# 7SEG_STATUS_1.net
KiCad netlist of a schematic drawn in EAGLE
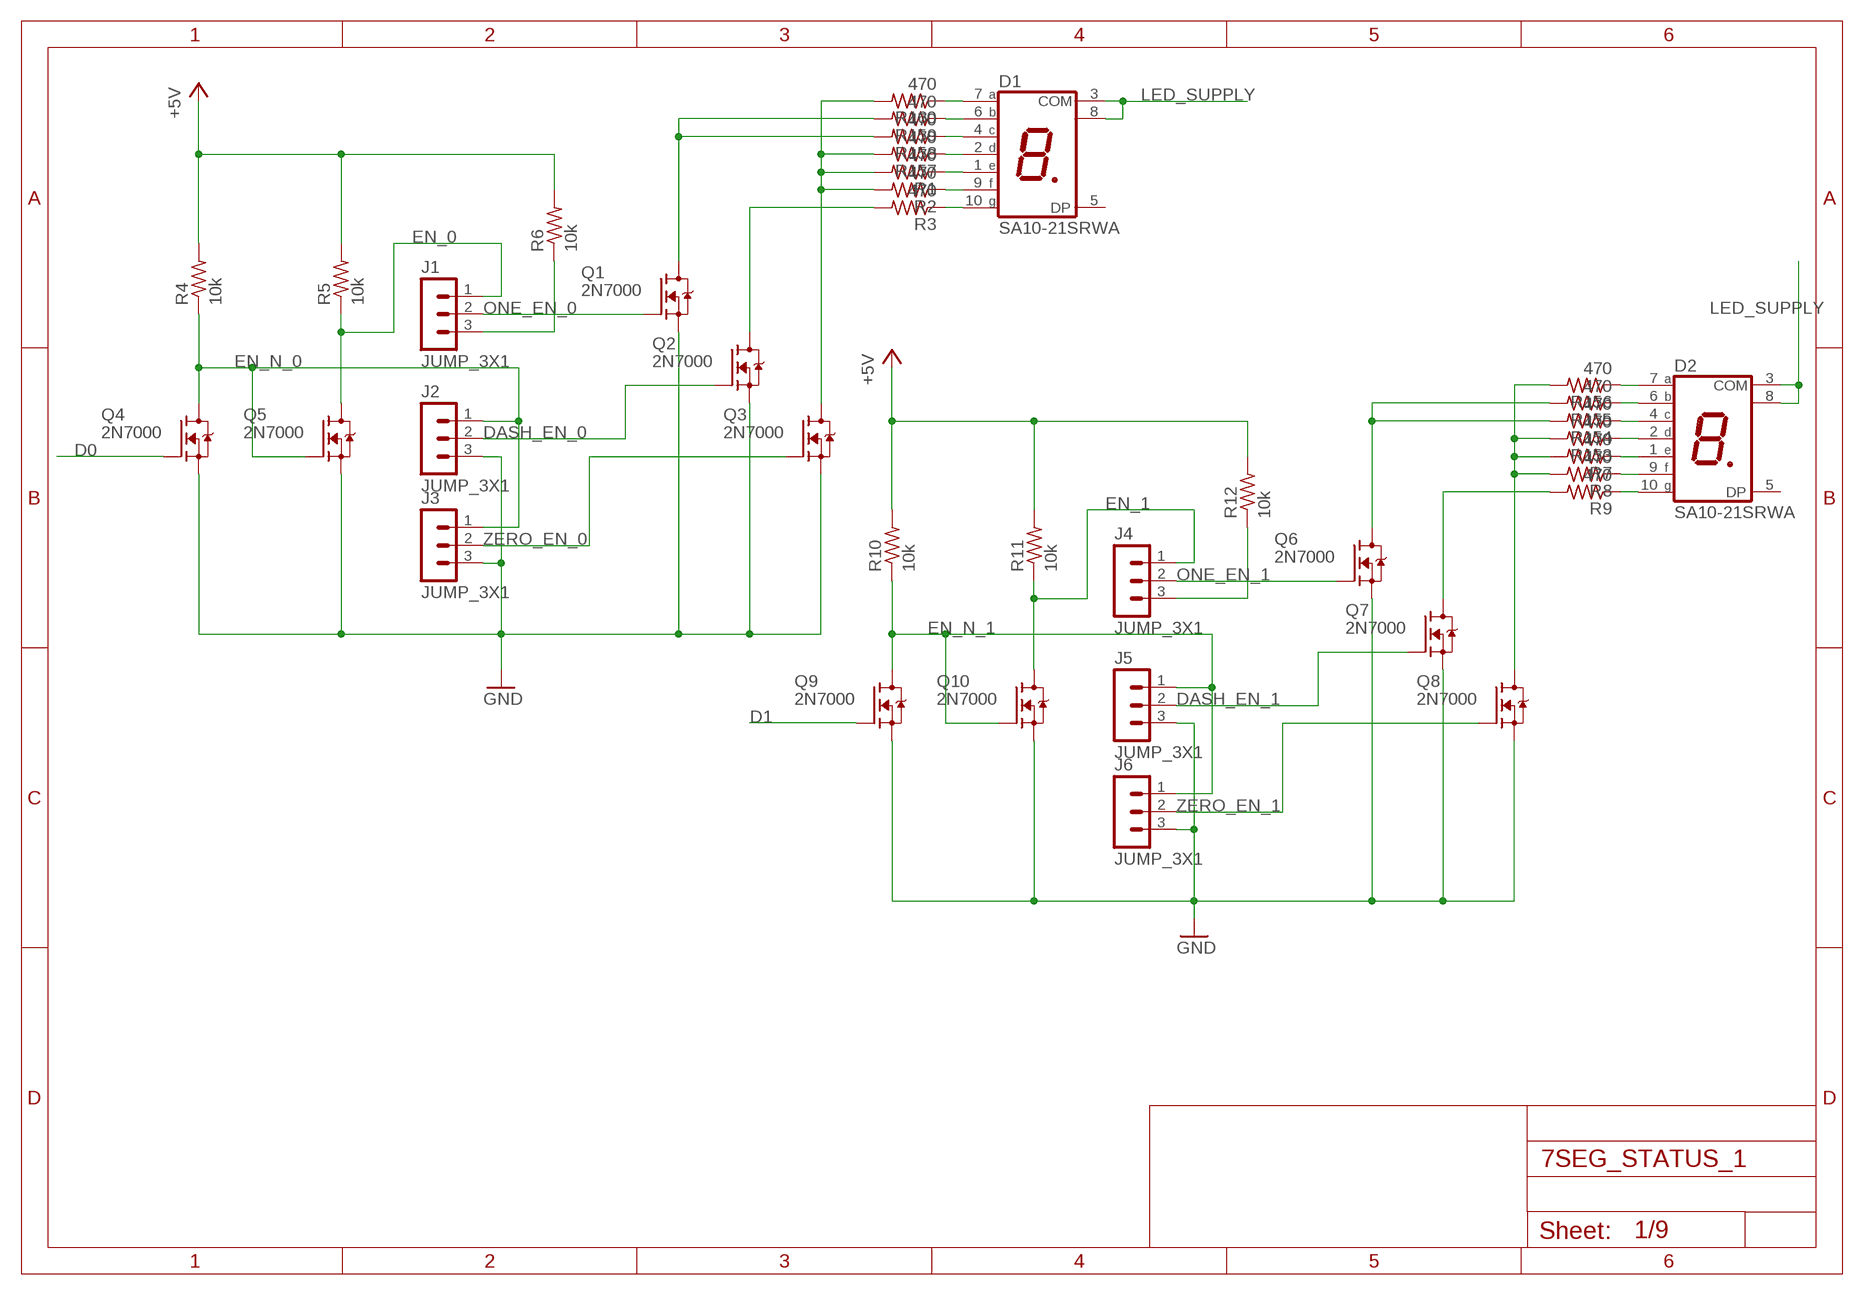
[diagram p0: schematic, sheet 1]
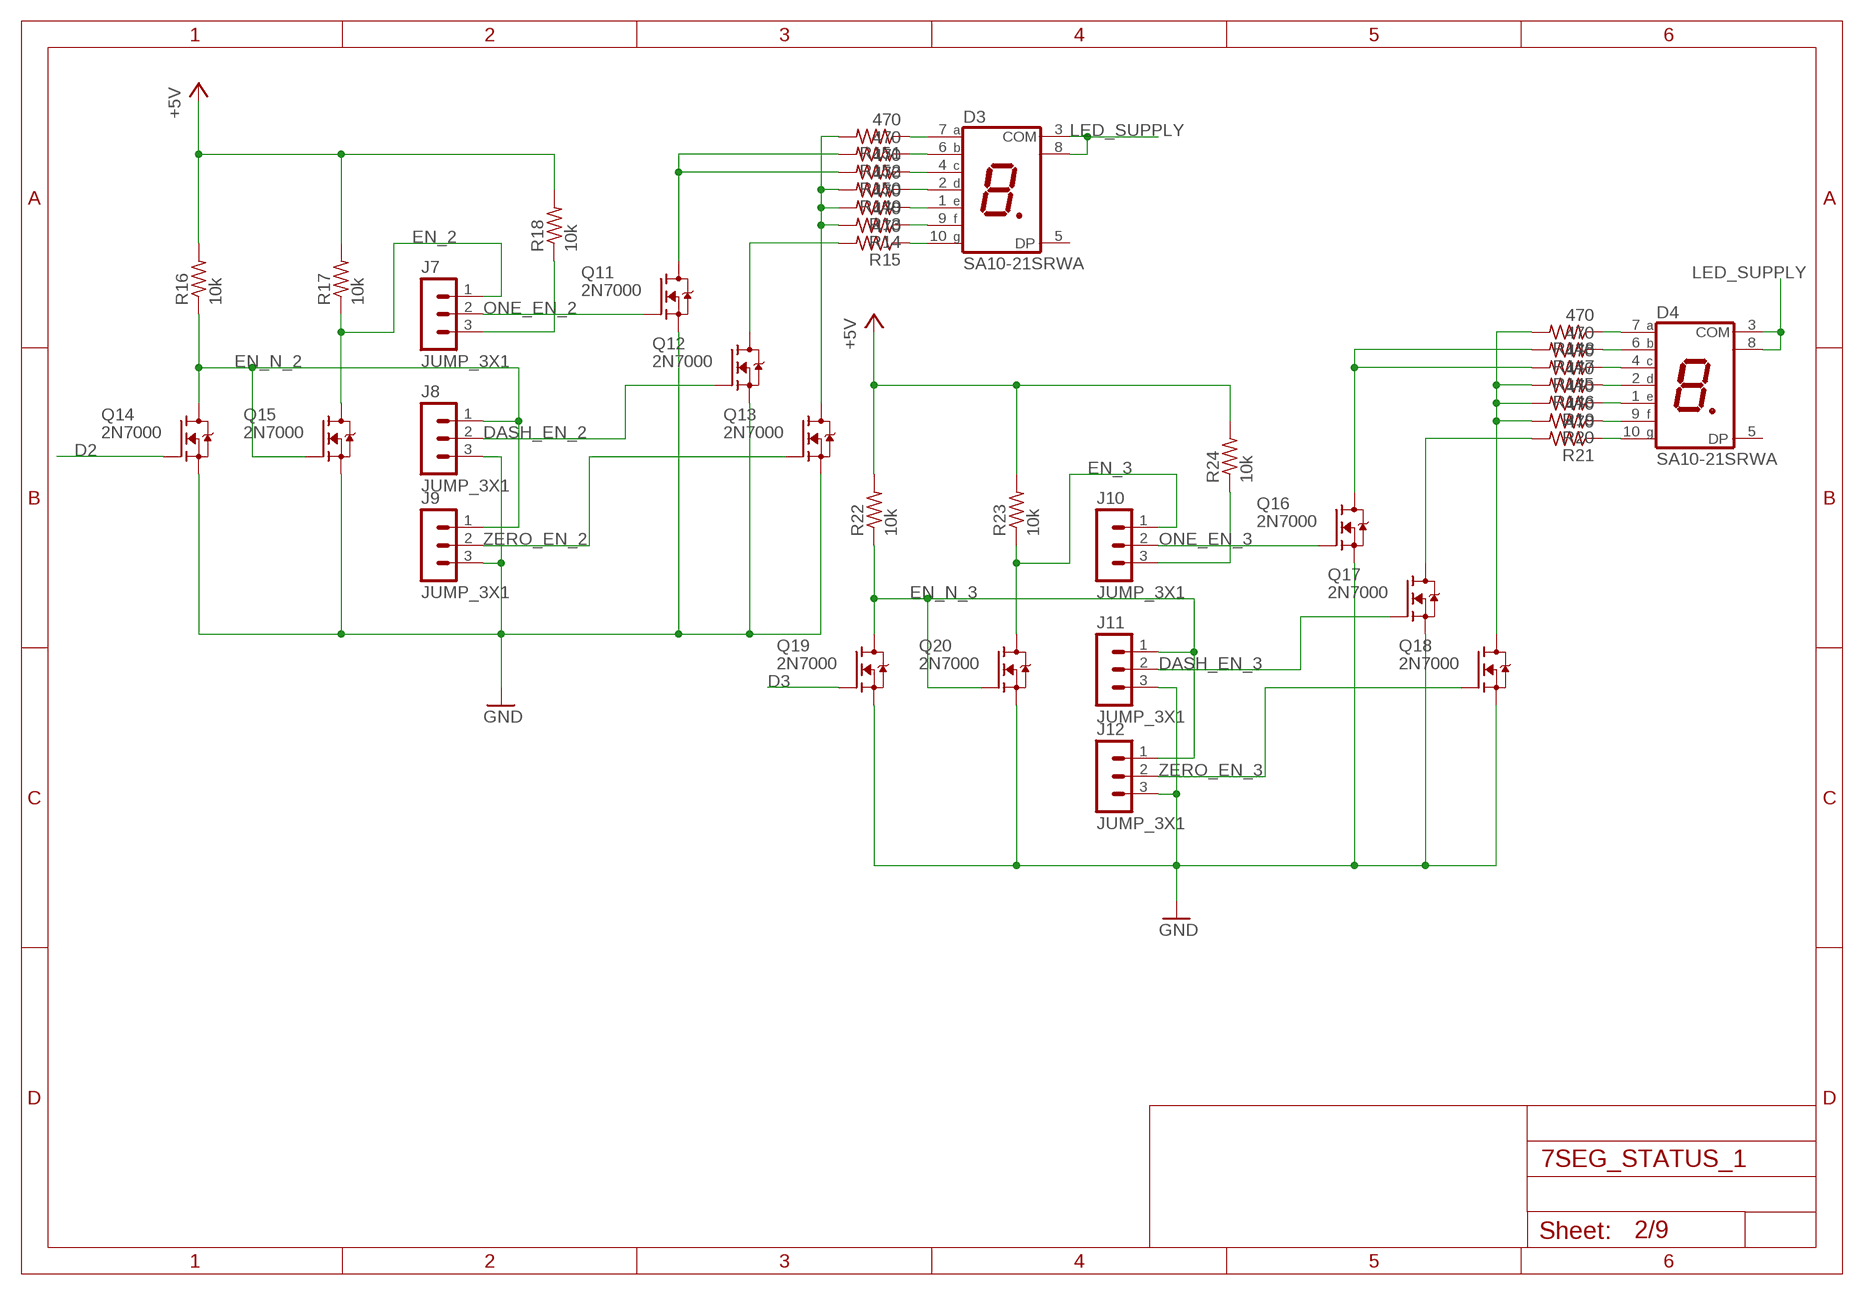
[diagram p1: schematic, sheet 2]
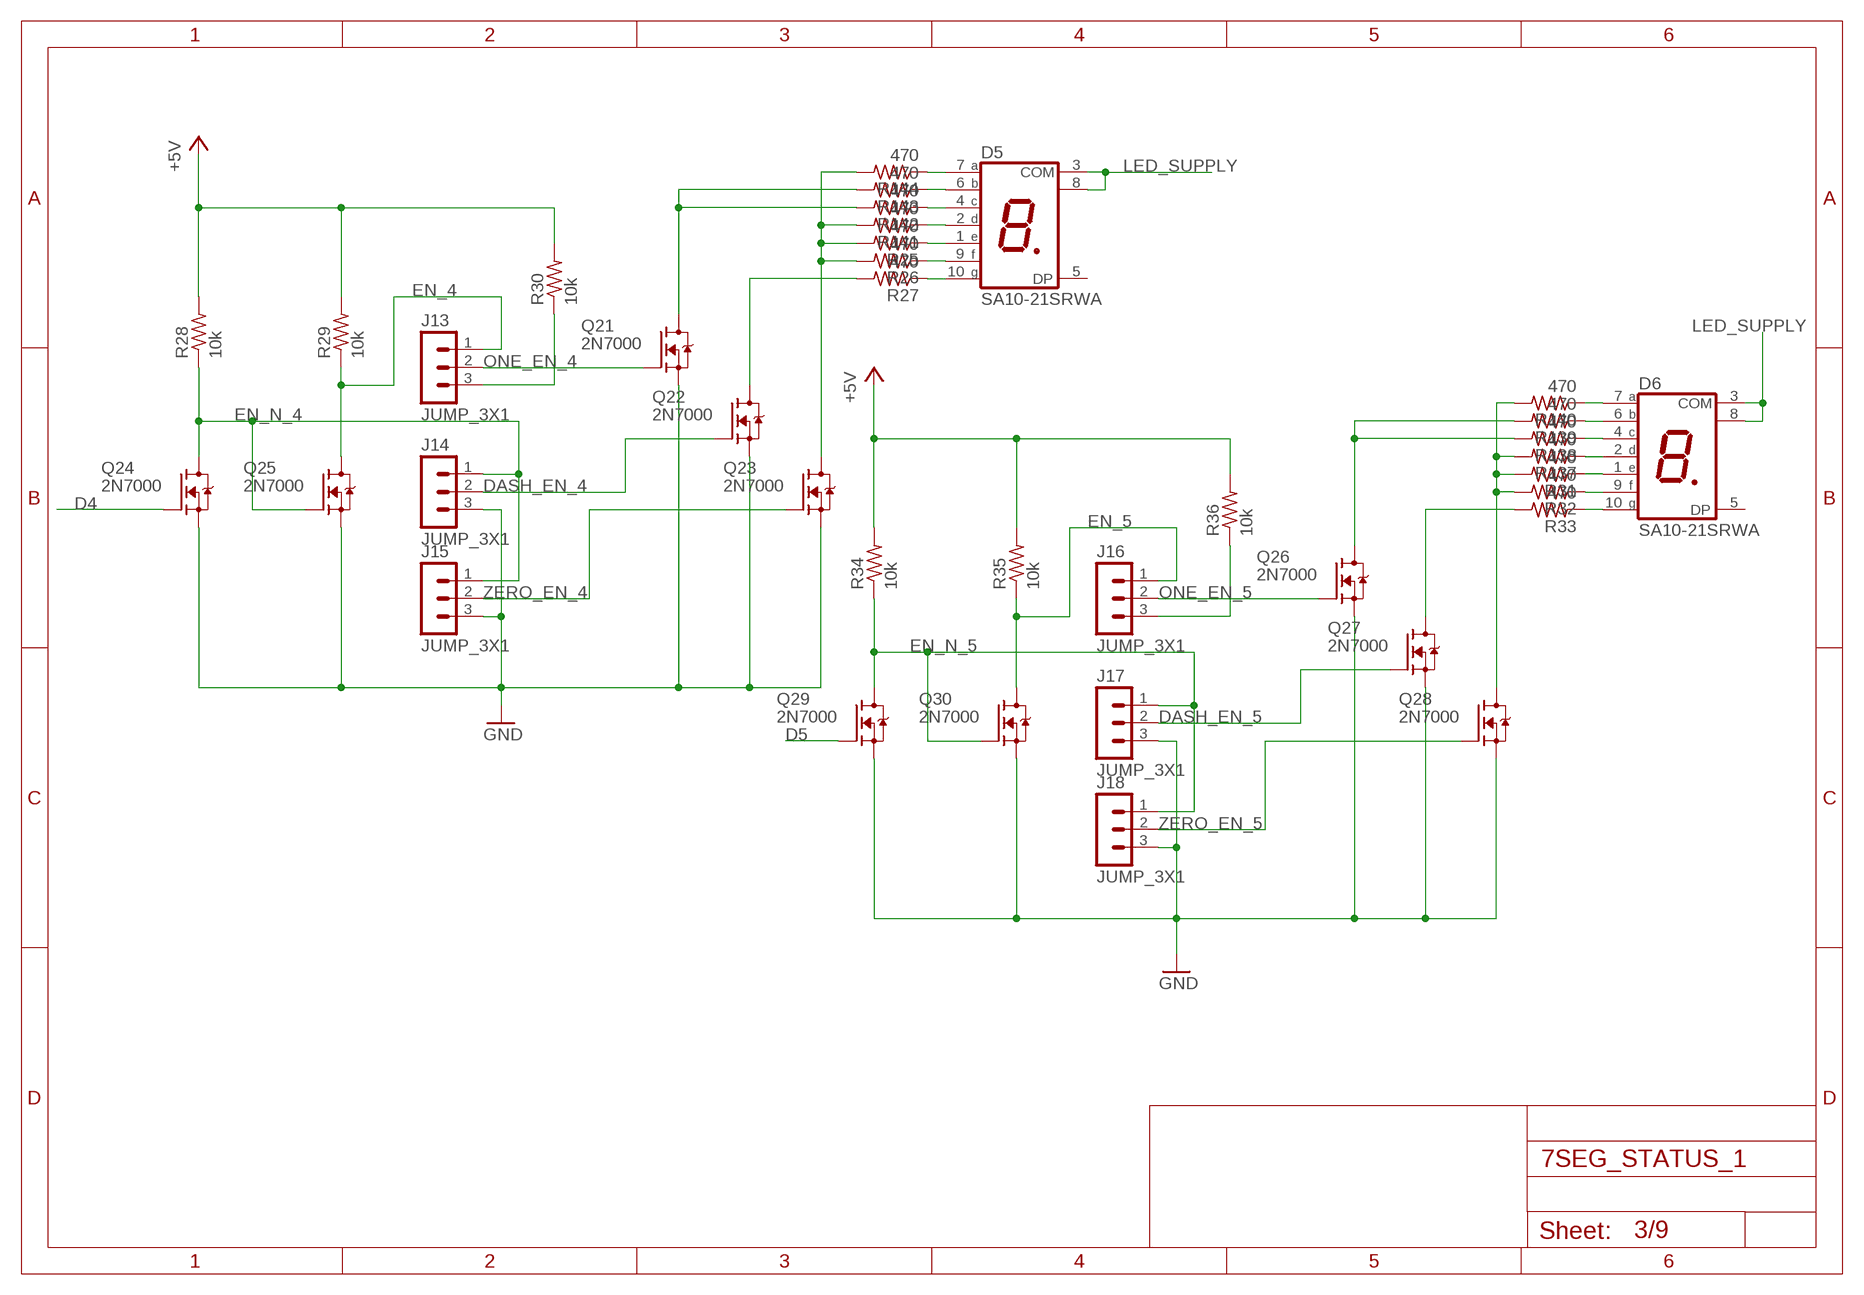
[diagram p2: schematic, sheet 3]
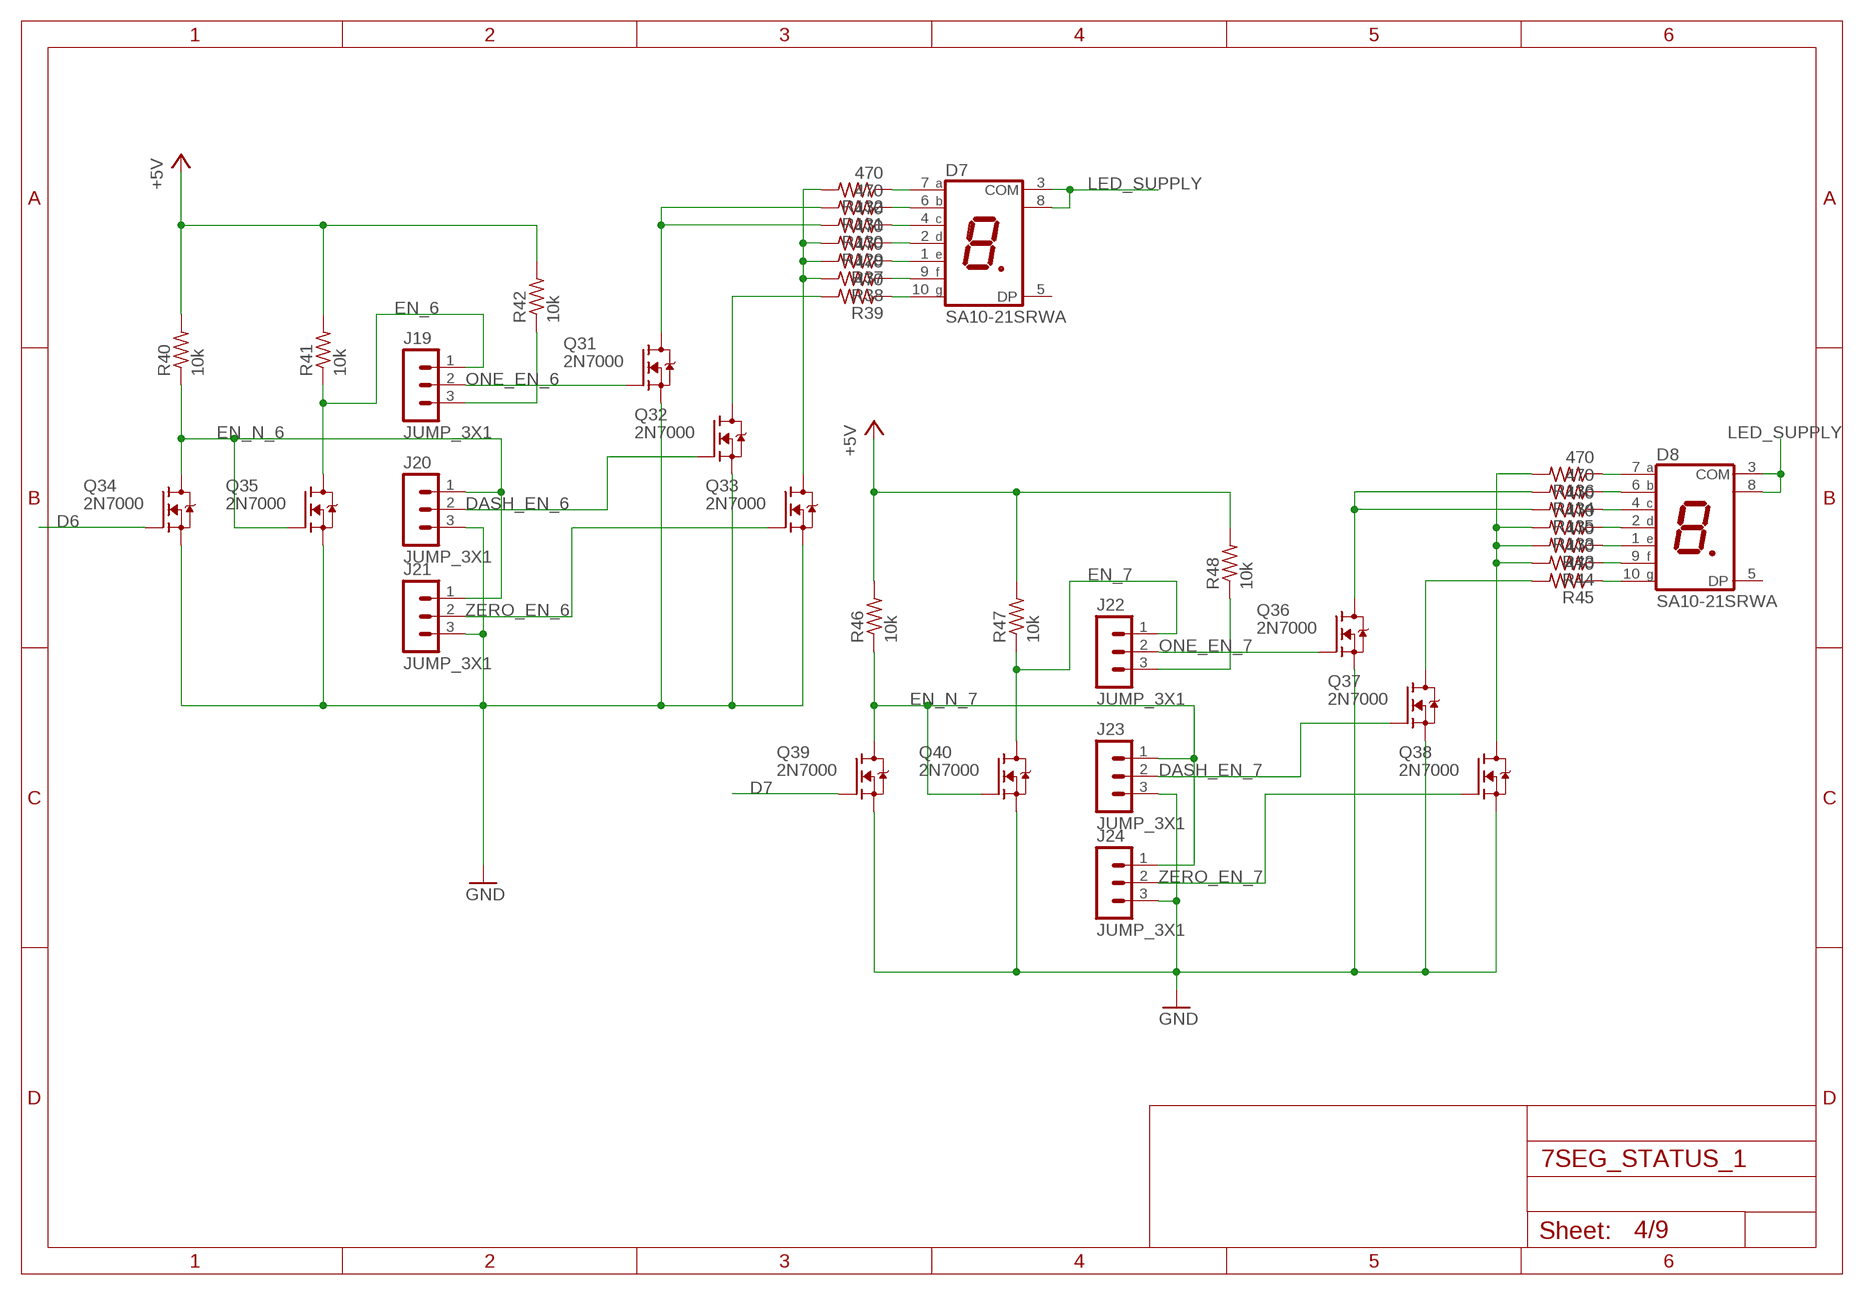
[diagram p3: schematic, sheet 4]
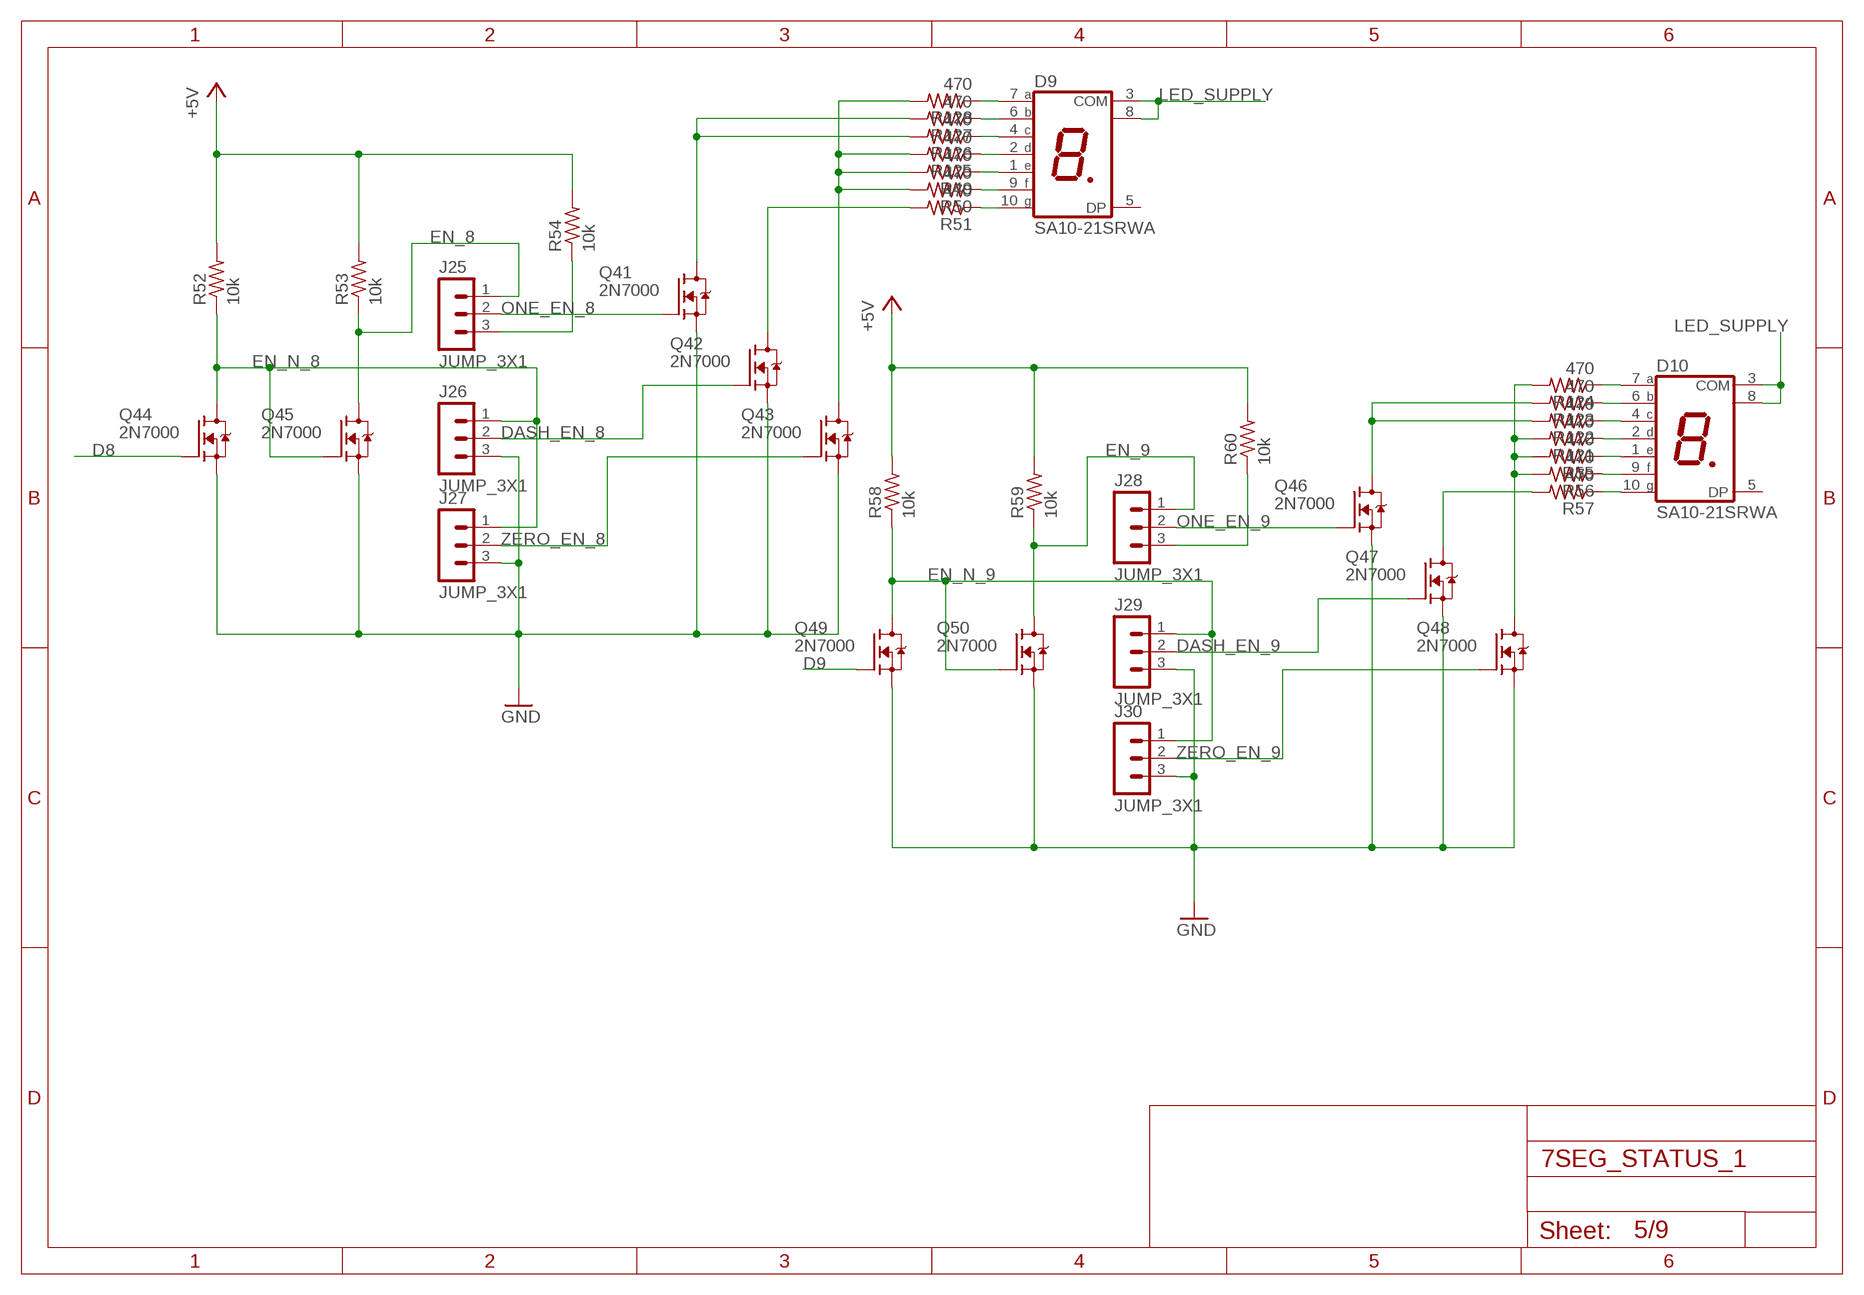
[diagram p4: schematic, sheet 5]
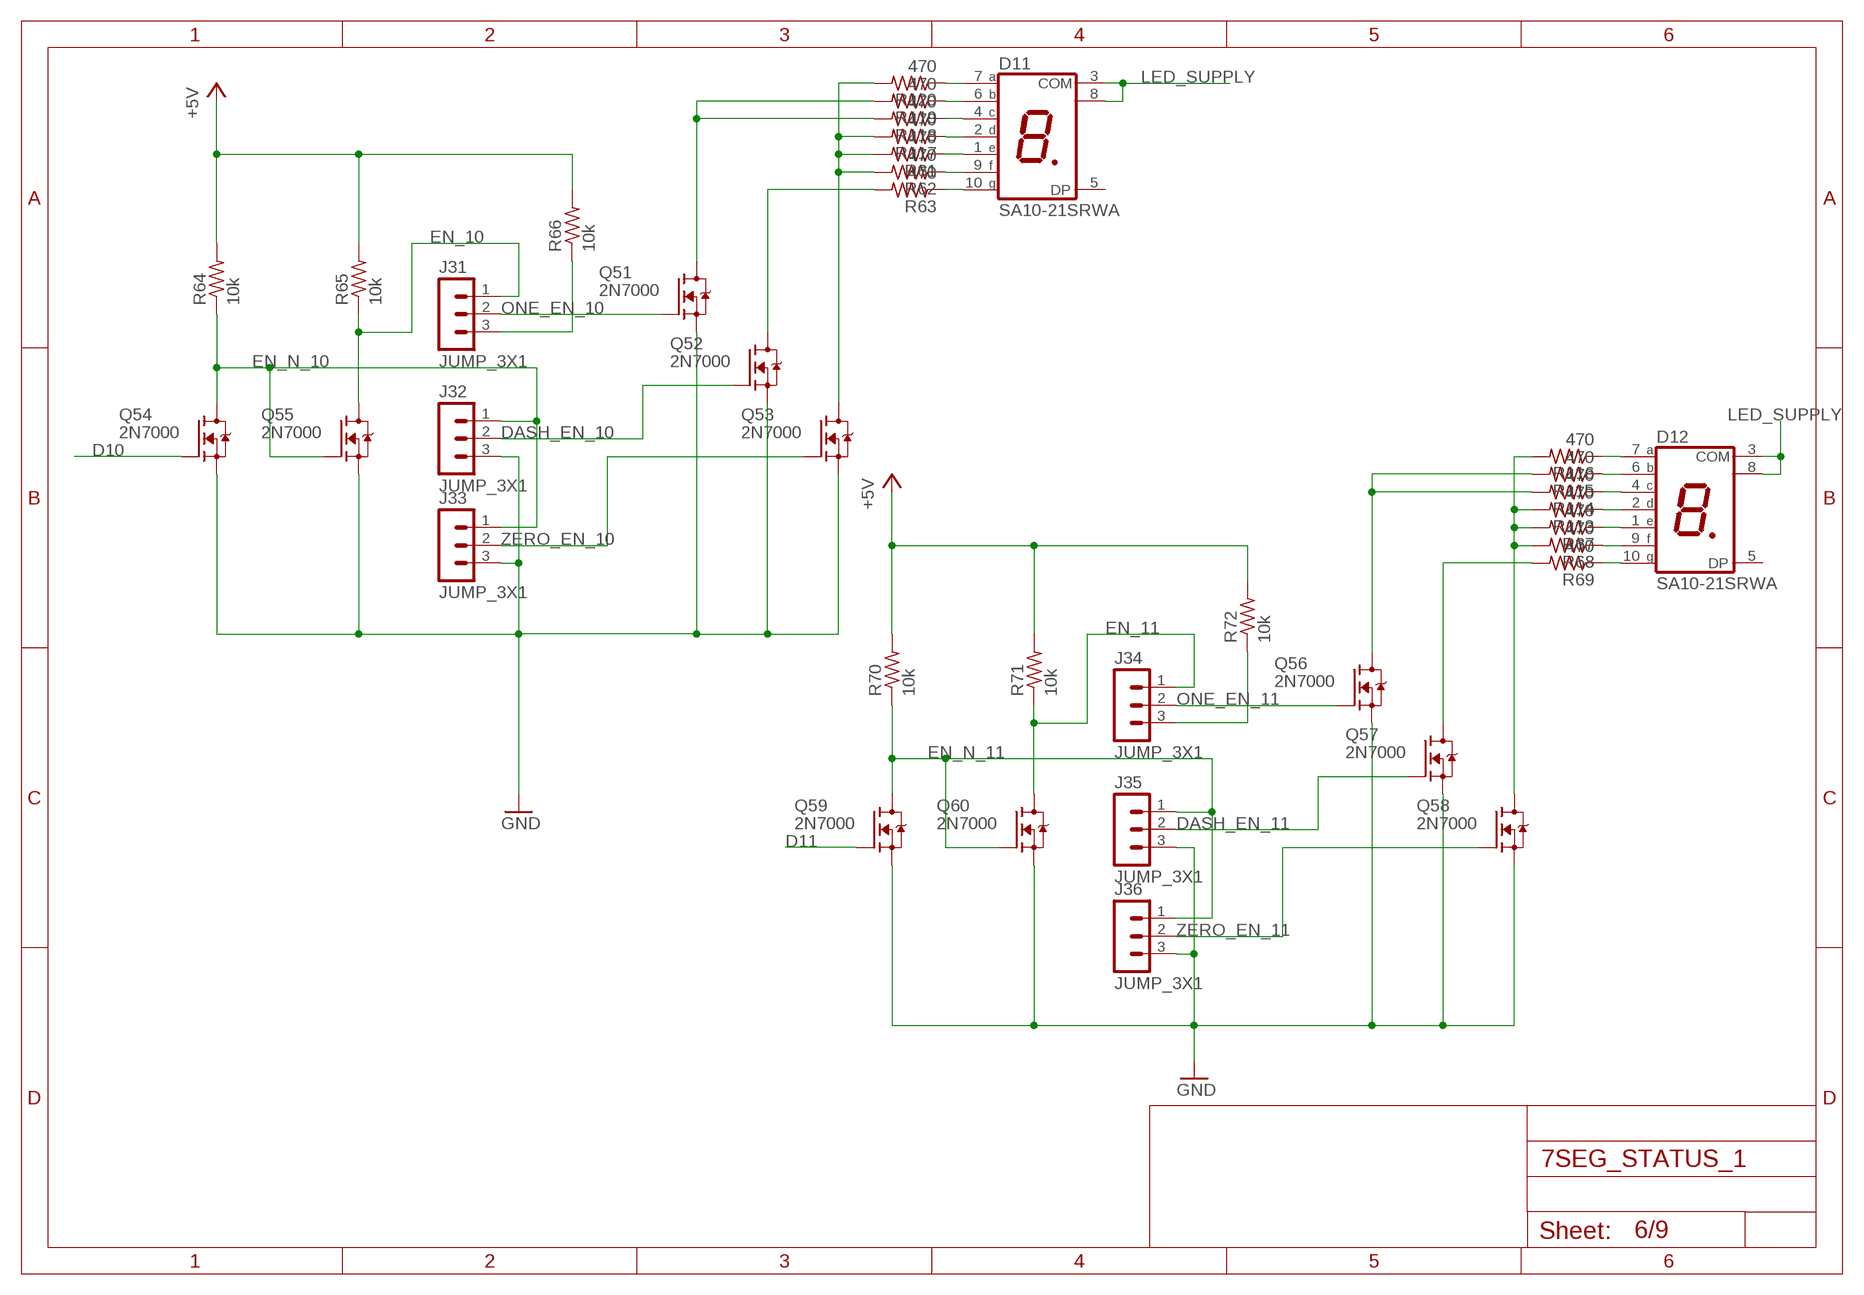
[diagram p5: schematic, sheet 6]
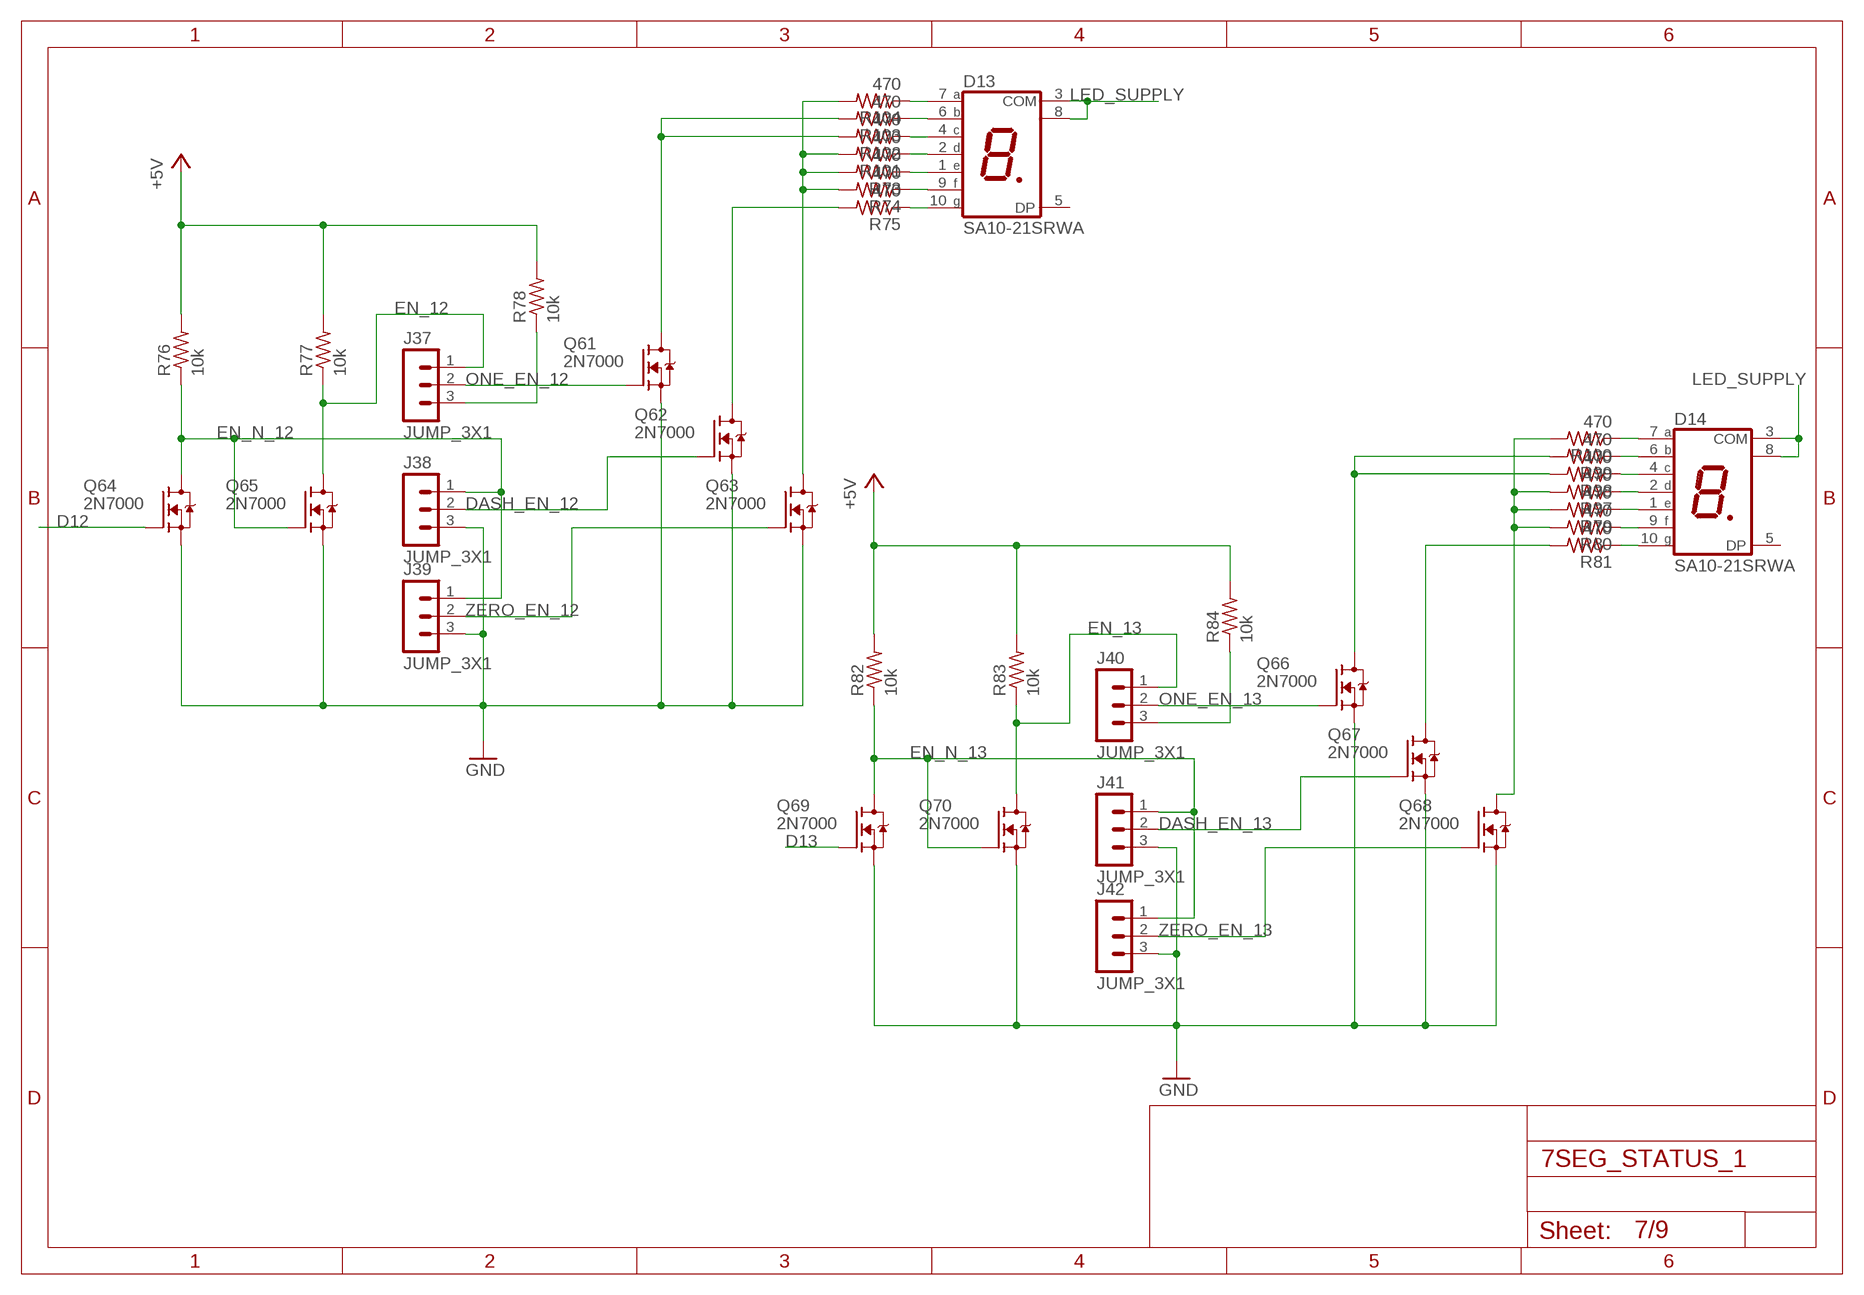
[diagram p6: schematic, sheet 7]
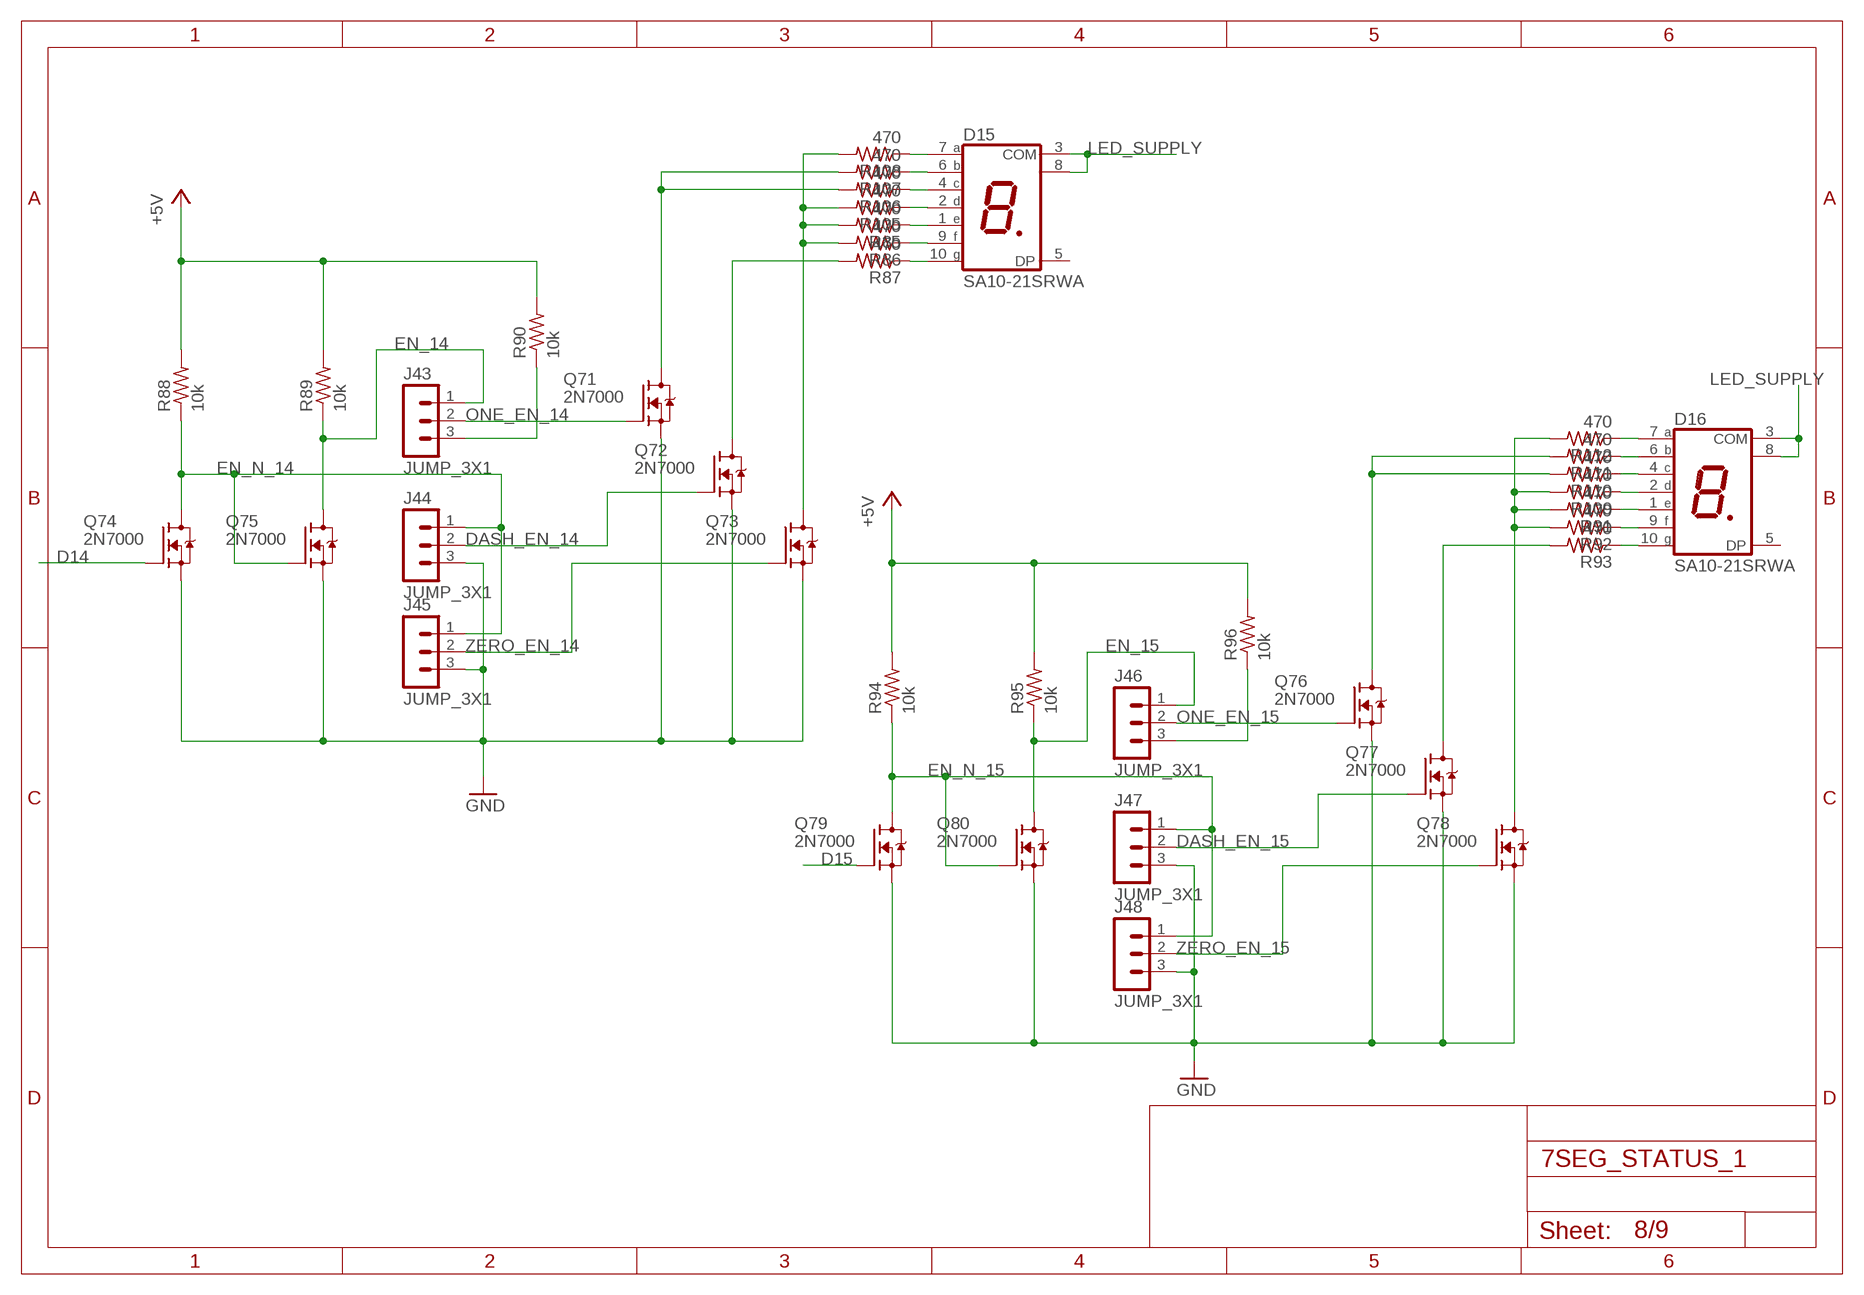
[diagram p7: schematic, sheet 8]
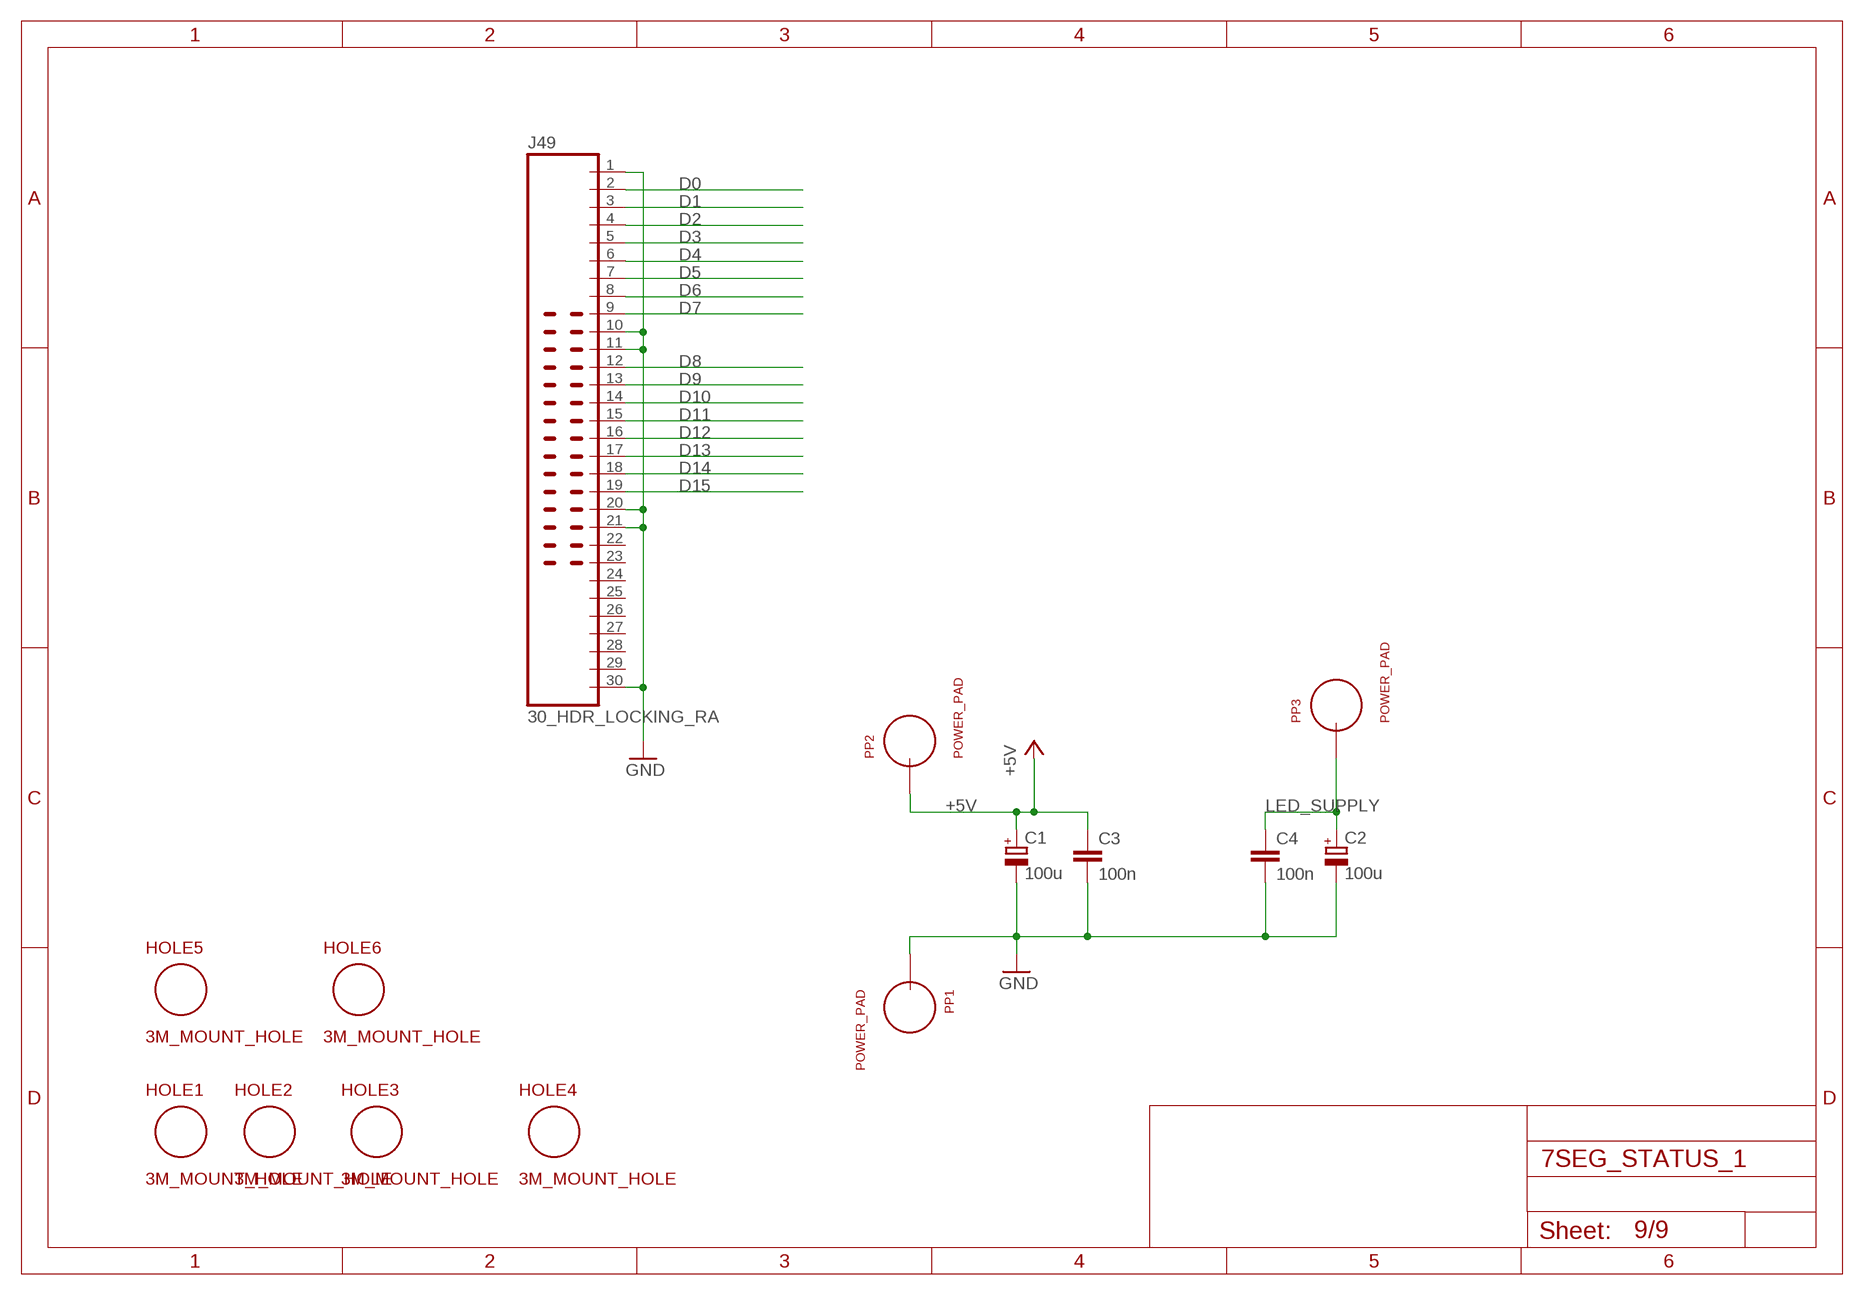
[diagram p8: schematic, sheet 9]

(export (version "E")
  (design (tool "Eeschema 10.0.6"))
  (components
    (comp (ref "D3")
      (value "SA10-21SRWA")
      (footprint "eagle-import:SA10")
      (libsource (lib "eagle-import") (part "SA10-21SRWA"))
    )
    (comp (ref "D4")
      (value "SA10-21SRWA")
      (footprint "eagle-import:SA10")
      (libsource (lib "eagle-import") (part "SA10-21SRWA"))
    )
    (comp (ref "J7")
      (value "JUMP_3X1")
      (footprint "eagle-import:JUMP_3X1")
      (libsource (lib "eagle-import") (part "JUMP_3X1"))
    )
    (comp (ref "J8")
      (value "JUMP_3X1")
      (footprint "eagle-import:JUMP_3X1")
      (libsource (lib "eagle-import") (part "JUMP_3X1"))
    )
    (comp (ref "J9")
      (value "JUMP_3X1")
      (footprint "eagle-import:JUMP_3X1")
      (libsource (lib "eagle-import") (part "JUMP_3X1"))
    )
    (comp (ref "J10")
      (value "JUMP_3X1")
      (footprint "eagle-import:JUMP_3X1")
      (libsource (lib "eagle-import") (part "JUMP_3X1"))
    )
    (comp (ref "J11")
      (value "JUMP_3X1")
      (footprint "eagle-import:JUMP_3X1")
      (libsource (lib "eagle-import") (part "JUMP_3X1"))
    )
    (comp (ref "J12")
      (value "JUMP_3X1")
      (footprint "eagle-import:JUMP_3X1")
      (libsource (lib "eagle-import") (part "JUMP_3X1"))
    )
    (comp (ref "Q11")
      (value "2N7000")
      (footprint "eagle-import:TO92-DGS")
      (libsource (lib "eagle-import") (part "2N7000"))
    )
    (comp (ref "Q12")
      (value "2N7000")
      (footprint "eagle-import:TO92-DGS")
      (libsource (lib "eagle-import") (part "2N7000"))
    )
    (comp (ref "Q13")
      (value "2N7000")
      (footprint "eagle-import:TO92-DGS")
      (libsource (lib "eagle-import") (part "2N7000"))
    )
    (comp (ref "Q14")
      (value "2N7000")
      (footprint "eagle-import:TO92-DGS")
      (libsource (lib "eagle-import") (part "2N7000"))
    )
    (comp (ref "Q15")
      (value "2N7000")
      (footprint "eagle-import:TO92-DGS")
      (libsource (lib "eagle-import") (part "2N7000"))
    )
    (comp (ref "Q16")
      (value "2N7000")
      (footprint "eagle-import:TO92-DGS")
      (libsource (lib "eagle-import") (part "2N7000"))
    )
    (comp (ref "Q17")
      (value "2N7000")
      (footprint "eagle-import:TO92-DGS")
      (libsource (lib "eagle-import") (part "2N7000"))
    )
    (comp (ref "Q18")
      (value "2N7000")
      (footprint "eagle-import:TO92-DGS")
      (libsource (lib "eagle-import") (part "2N7000"))
    )
    (comp (ref "Q19")
      (value "2N7000")
      (footprint "eagle-import:TO92-DGS")
      (libsource (lib "eagle-import") (part "2N7000"))
    )
    (comp (ref "Q20")
      (value "2N7000")
      (footprint "eagle-import:TO92-DGS")
      (libsource (lib "eagle-import") (part "2N7000"))
    )
    (comp (ref "R13")
      (value "470")
      (footprint "eagle-import:R_P2INCH")
      (libsource (lib "eagle-import") (part "R_P2INCH"))
    )
    (comp (ref "R14")
      (value "470")
      (footprint "eagle-import:R_P2INCH")
      (libsource (lib "eagle-import") (part "R_P2INCH"))
    )
    (comp (ref "R15")
      (value "470")
      (footprint "eagle-import:R_P2INCH")
      (libsource (lib "eagle-import") (part "R_P2INCH"))
    )
    (comp (ref "R16")
      (value "10k")
      (footprint "eagle-import:R_P2INCH")
      (libsource (lib "eagle-import") (part "R_P2INCH"))
    )
    (comp (ref "R17")
      (value "10k")
      (footprint "eagle-import:R_P2INCH")
      (libsource (lib "eagle-import") (part "R_P2INCH"))
    )
    (comp (ref "R18")
      (value "10k")
      (footprint "eagle-import:R_P2INCH")
      (libsource (lib "eagle-import") (part "R_P2INCH"))
    )
    (comp (ref "R19")
      (value "470")
      (footprint "eagle-import:R_P2INCH")
      (libsource (lib "eagle-import") (part "R_P2INCH"))
    )
    (comp (ref "R20")
      (value "470")
      (footprint "eagle-import:R_P2INCH")
      (libsource (lib "eagle-import") (part "R_P2INCH"))
    )
    (comp (ref "R21")
      (value "470")
      (footprint "eagle-import:R_P2INCH")
      (libsource (lib "eagle-import") (part "R_P2INCH"))
    )
    (comp (ref "R22")
      (value "10k")
      (footprint "eagle-import:R_P2INCH")
      (libsource (lib "eagle-import") (part "R_P2INCH"))
    )
    (comp (ref "R23")
      (value "10k")
      (footprint "eagle-import:R_P2INCH")
      (libsource (lib "eagle-import") (part "R_P2INCH"))
    )
    (comp (ref "R24")
      (value "10k")
      (footprint "eagle-import:R_P2INCH")
      (libsource (lib "eagle-import") (part "R_P2INCH"))
    )
    (comp (ref "R145")
      (value "470")
      (footprint "eagle-import:R_P2INCH")
      (libsource (lib "eagle-import") (part "R_P2INCH"))
    )
    (comp (ref "R146")
      (value "470")
      (footprint "eagle-import:R_P2INCH")
      (libsource (lib "eagle-import") (part "R_P2INCH"))
    )
    (comp (ref "R147")
      (value "470")
      (footprint "eagle-import:R_P2INCH")
      (libsource (lib "eagle-import") (part "R_P2INCH"))
    )
    (comp (ref "R148")
      (value "470")
      (footprint "eagle-import:R_P2INCH")
      (libsource (lib "eagle-import") (part "R_P2INCH"))
    )
    (comp (ref "R149")
      (value "470")
      (footprint "eagle-import:R_P2INCH")
      (libsource (lib "eagle-import") (part "R_P2INCH"))
    )
    (comp (ref "R150")
      (value "470")
      (footprint "eagle-import:R_P2INCH")
      (libsource (lib "eagle-import") (part "R_P2INCH"))
    )
    (comp (ref "R151")
      (value "470")
      (footprint "eagle-import:R_P2INCH")
      (libsource (lib "eagle-import") (part "R_P2INCH"))
    )
    (comp (ref "R152")
      (value "470")
      (footprint "eagle-import:R_P2INCH")
      (libsource (lib "eagle-import") (part "R_P2INCH"))
    )
    (comp (ref "D13")
      (value "SA10-21SRWA")
      (footprint "eagle-import:SA10")
      (libsource (lib "eagle-import") (part "SA10-21SRWA"))
    )
    (comp (ref "D14")
      (value "SA10-21SRWA")
      (footprint "eagle-import:SA10")
      (libsource (lib "eagle-import") (part "SA10-21SRWA"))
    )
    (comp (ref "J37")
      (value "JUMP_3X1")
      (footprint "eagle-import:JUMP_3X1")
      (libsource (lib "eagle-import") (part "JUMP_3X1"))
    )
    (comp (ref "J38")
      (value "JUMP_3X1")
      (footprint "eagle-import:JUMP_3X1")
      (libsource (lib "eagle-import") (part "JUMP_3X1"))
    )
    (comp (ref "J39")
      (value "JUMP_3X1")
      (footprint "eagle-import:JUMP_3X1")
      (libsource (lib "eagle-import") (part "JUMP_3X1"))
    )
    (comp (ref "J40")
      (value "JUMP_3X1")
      (footprint "eagle-import:JUMP_3X1")
      (libsource (lib "eagle-import") (part "JUMP_3X1"))
    )
    (comp (ref "J41")
      (value "JUMP_3X1")
      (footprint "eagle-import:JUMP_3X1")
      (libsource (lib "eagle-import") (part "JUMP_3X1"))
    )
    (comp (ref "J42")
      (value "JUMP_3X1")
      (footprint "eagle-import:JUMP_3X1")
      (libsource (lib "eagle-import") (part "JUMP_3X1"))
    )
    (comp (ref "Q61")
      (value "2N7000")
      (footprint "eagle-import:TO92-DGS")
      (libsource (lib "eagle-import") (part "2N7000"))
    )
    (comp (ref "Q62")
      (value "2N7000")
      (footprint "eagle-import:TO92-DGS")
      (libsource (lib "eagle-import") (part "2N7000"))
    )
    (comp (ref "Q63")
      (value "2N7000")
      (footprint "eagle-import:TO92-DGS")
      (libsource (lib "eagle-import") (part "2N7000"))
    )
    (comp (ref "Q64")
      (value "2N7000")
      (footprint "eagle-import:TO92-DGS")
      (libsource (lib "eagle-import") (part "2N7000"))
    )
    (comp (ref "Q65")
      (value "2N7000")
      (footprint "eagle-import:TO92-DGS")
      (libsource (lib "eagle-import") (part "2N7000"))
    )
    (comp (ref "Q66")
      (value "2N7000")
      (footprint "eagle-import:TO92-DGS")
      (libsource (lib "eagle-import") (part "2N7000"))
    )
    (comp (ref "Q67")
      (value "2N7000")
      (footprint "eagle-import:TO92-DGS")
      (libsource (lib "eagle-import") (part "2N7000"))
    )
    (comp (ref "Q68")
      (value "2N7000")
      (footprint "eagle-import:TO92-DGS")
      (libsource (lib "eagle-import") (part "2N7000"))
    )
    (comp (ref "Q69")
      (value "2N7000")
      (footprint "eagle-import:TO92-DGS")
      (libsource (lib "eagle-import") (part "2N7000"))
    )
    (comp (ref "Q70")
      (value "2N7000")
      (footprint "eagle-import:TO92-DGS")
      (libsource (lib "eagle-import") (part "2N7000"))
    )
    (comp (ref "R73")
      (value "470")
      (footprint "eagle-import:R_P2INCH")
      (libsource (lib "eagle-import") (part "R_P2INCH"))
    )
    (comp (ref "R74")
      (value "470")
      (footprint "eagle-import:R_P2INCH")
      (libsource (lib "eagle-import") (part "R_P2INCH"))
    )
    (comp (ref "R75")
      (value "470")
      (footprint "eagle-import:R_P2INCH")
      (libsource (lib "eagle-import") (part "R_P2INCH"))
    )
    (comp (ref "R76")
      (value "10k")
      (footprint "eagle-import:R_P2INCH")
      (libsource (lib "eagle-import") (part "R_P2INCH"))
    )
    (comp (ref "R77")
      (value "10k")
      (footprint "eagle-import:R_P2INCH")
      (libsource (lib "eagle-import") (part "R_P2INCH"))
    )
    (comp (ref "R78")
      (value "10k")
      (footprint "eagle-import:R_P2INCH")
      (libsource (lib "eagle-import") (part "R_P2INCH"))
    )
    (comp (ref "R79")
      (value "470")
      (footprint "eagle-import:R_P2INCH")
      (libsource (lib "eagle-import") (part "R_P2INCH"))
    )
    (comp (ref "R80")
      (value "470")
      (footprint "eagle-import:R_P2INCH")
      (libsource (lib "eagle-import") (part "R_P2INCH"))
    )
    (comp (ref "R81")
      (value "470")
      (footprint "eagle-import:R_P2INCH")
      (libsource (lib "eagle-import") (part "R_P2INCH"))
    )
    (comp (ref "R82")
      (value "10k")
      (footprint "eagle-import:R_P2INCH")
      (libsource (lib "eagle-import") (part "R_P2INCH"))
    )
    (comp (ref "R83")
      (value "10k")
      (footprint "eagle-import:R_P2INCH")
      (libsource (lib "eagle-import") (part "R_P2INCH"))
    )
    (comp (ref "R84")
      (value "10k")
      (footprint "eagle-import:R_P2INCH")
      (libsource (lib "eagle-import") (part "R_P2INCH"))
    )
    (comp (ref "R97")
      (value "470")
      (footprint "eagle-import:R_P2INCH")
      (libsource (lib "eagle-import") (part "R_P2INCH"))
    )
    (comp (ref "R98")
      (value "470")
      (footprint "eagle-import:R_P2INCH")
      (libsource (lib "eagle-import") (part "R_P2INCH"))
    )
    (comp (ref "R99")
      (value "470")
      (footprint "eagle-import:R_P2INCH")
      (libsource (lib "eagle-import") (part "R_P2INCH"))
    )
    (comp (ref "R100")
      (value "470")
      (footprint "eagle-import:R_P2INCH")
      (libsource (lib "eagle-import") (part "R_P2INCH"))
    )
    (comp (ref "R101")
      (value "470")
      (footprint "eagle-import:R_P2INCH")
      (libsource (lib "eagle-import") (part "R_P2INCH"))
    )
    (comp (ref "R102")
      (value "470")
      (footprint "eagle-import:R_P2INCH")
      (libsource (lib "eagle-import") (part "R_P2INCH"))
    )
    (comp (ref "R103")
      (value "470")
      (footprint "eagle-import:R_P2INCH")
      (libsource (lib "eagle-import") (part "R_P2INCH"))
    )
    (comp (ref "R104")
      (value "470")
      (footprint "eagle-import:R_P2INCH")
      (libsource (lib "eagle-import") (part "R_P2INCH"))
    )
    (comp (ref "C1")
      (value "100u")
      (footprint "eagle-import:POLARISED_CAP_2P5_6P3MM")
      (libsource (lib "eagle-import") (part "POLARISED_CAP_2P5_6P3MM"))
    )
    (comp (ref "C2")
      (value "100u")
      (footprint "eagle-import:POLARISED_CAP_2P5_6P3MM")
      (libsource (lib "eagle-import") (part "POLARISED_CAP_2P5_6P3MM"))
    )
    (comp (ref "C3")
      (value "100n")
      (footprint "eagle-import:CAP_P2INCH")
      (libsource (lib "eagle-import") (part "C_P2INCH"))
    )
    (comp (ref "C4")
      (value "100n")
      (footprint "eagle-import:CAP_P2INCH")
      (libsource (lib "eagle-import") (part "C_P2INCH"))
    )
    (comp (ref "HOLE1")
      (value "3M_MOUNT_HOLE")
      (footprint "eagle-import:3M_HOLE")
      (libsource (lib "eagle-import") (part "3M_MOUNT_HOLE"))
    )
    (comp (ref "HOLE2")
      (value "3M_MOUNT_HOLE")
      (footprint "eagle-import:3M_HOLE")
      (libsource (lib "eagle-import") (part "3M_MOUNT_HOLE"))
    )
    (comp (ref "HOLE3")
      (value "3M_MOUNT_HOLE")
      (footprint "eagle-import:3M_HOLE")
      (libsource (lib "eagle-import") (part "3M_MOUNT_HOLE"))
    )
    (comp (ref "HOLE4")
      (value "3M_MOUNT_HOLE")
      (footprint "eagle-import:3M_HOLE")
      (libsource (lib "eagle-import") (part "3M_MOUNT_HOLE"))
    )
    (comp (ref "HOLE5")
      (value "3M_MOUNT_HOLE")
      (footprint "eagle-import:3M_HOLE")
      (libsource (lib "eagle-import") (part "3M_MOUNT_HOLE"))
    )
    (comp (ref "HOLE6")
      (value "3M_MOUNT_HOLE")
      (footprint "eagle-import:3M_HOLE")
      (libsource (lib "eagle-import") (part "3M_MOUNT_HOLE"))
    )
    (comp (ref "J49")
      (value "30_HDR_LOCKING_RA")
      (footprint "eagle-import:30_HDR_LOCKING_RA")
      (libsource (lib "eagle-import") (part "30_HDR_LOCKING_RA"))
    )
    (comp (ref "PP1")
      (value "POWER_PAD")
      (footprint "eagle-import:POWER_PAD")
      (libsource (lib "eagle-import") (part "POWER_PAD"))
    )
    (comp (ref "PP2")
      (value "POWER_PAD")
      (footprint "eagle-import:POWER_PAD")
      (libsource (lib "eagle-import") (part "POWER_PAD"))
    )
    (comp (ref "PP3")
      (value "POWER_PAD")
      (footprint "eagle-import:POWER_PAD")
      (libsource (lib "eagle-import") (part "POWER_PAD"))
    )
    (comp (ref "D1")
      (value "SA10-21SRWA")
      (footprint "eagle-import:SA10")
      (libsource (lib "eagle-import") (part "SA10-21SRWA"))
    )
    (comp (ref "D2")
      (value "SA10-21SRWA")
      (footprint "eagle-import:SA10")
      (libsource (lib "eagle-import") (part "SA10-21SRWA"))
    )
    (comp (ref "J1")
      (value "JUMP_3X1")
      (footprint "eagle-import:JUMP_3X1")
      (libsource (lib "eagle-import") (part "JUMP_3X1"))
    )
    (comp (ref "J2")
      (value "JUMP_3X1")
      (footprint "eagle-import:JUMP_3X1")
      (libsource (lib "eagle-import") (part "JUMP_3X1"))
    )
    (comp (ref "J3")
      (value "JUMP_3X1")
      (footprint "eagle-import:JUMP_3X1")
      (libsource (lib "eagle-import") (part "JUMP_3X1"))
    )
    (comp (ref "J4")
      (value "JUMP_3X1")
      (footprint "eagle-import:JUMP_3X1")
      (libsource (lib "eagle-import") (part "JUMP_3X1"))
    )
    (comp (ref "J5")
      (value "JUMP_3X1")
      (footprint "eagle-import:JUMP_3X1")
      (libsource (lib "eagle-import") (part "JUMP_3X1"))
    )
    (comp (ref "J6")
      (value "JUMP_3X1")
      (footprint "eagle-import:JUMP_3X1")
      (libsource (lib "eagle-import") (part "JUMP_3X1"))
    )
    (comp (ref "Q1")
      (value "2N7000")
      (footprint "eagle-import:TO92-DGS")
      (libsource (lib "eagle-import") (part "2N7000"))
    )
    (comp (ref "Q2")
      (value "2N7000")
      (footprint "eagle-import:TO92-DGS")
      (libsource (lib "eagle-import") (part "2N7000"))
    )
    (comp (ref "Q3")
      (value "2N7000")
      (footprint "eagle-import:TO92-DGS")
      (libsource (lib "eagle-import") (part "2N7000"))
    )
    (comp (ref "Q4")
      (value "2N7000")
      (footprint "eagle-import:TO92-DGS")
      (libsource (lib "eagle-import") (part "2N7000"))
    )
    (comp (ref "Q5")
      (value "2N7000")
      (footprint "eagle-import:TO92-DGS")
      (libsource (lib "eagle-import") (part "2N7000"))
    )
    (comp (ref "Q6")
      (value "2N7000")
      (footprint "eagle-import:TO92-DGS")
      (libsource (lib "eagle-import") (part "2N7000"))
    )
    (comp (ref "Q7")
      (value "2N7000")
      (footprint "eagle-import:TO92-DGS")
      (libsource (lib "eagle-import") (part "2N7000"))
    )
    (comp (ref "Q8")
      (value "2N7000")
      (footprint "eagle-import:TO92-DGS")
      (libsource (lib "eagle-import") (part "2N7000"))
    )
    (comp (ref "Q9")
      (value "2N7000")
      (footprint "eagle-import:TO92-DGS")
      (libsource (lib "eagle-import") (part "2N7000"))
    )
    (comp (ref "Q10")
      (value "2N7000")
      (footprint "eagle-import:TO92-DGS")
      (libsource (lib "eagle-import") (part "2N7000"))
    )
    (comp (ref "R1")
      (value "470")
      (footprint "eagle-import:R_P2INCH")
      (libsource (lib "eagle-import") (part "R_P2INCH"))
    )
    (comp (ref "R2")
      (value "470")
      (footprint "eagle-import:R_P2INCH")
      (libsource (lib "eagle-import") (part "R_P2INCH"))
    )
    (comp (ref "R3")
      (value "470")
      (footprint "eagle-import:R_P2INCH")
      (libsource (lib "eagle-import") (part "R_P2INCH"))
    )
    (comp (ref "R4")
      (value "10k")
      (footprint "eagle-import:R_P2INCH")
      (libsource (lib "eagle-import") (part "R_P2INCH"))
    )
    (comp (ref "R5")
      (value "10k")
      (footprint "eagle-import:R_P2INCH")
      (libsource (lib "eagle-import") (part "R_P2INCH"))
    )
    (comp (ref "R6")
      (value "10k")
      (footprint "eagle-import:R_P2INCH")
      (libsource (lib "eagle-import") (part "R_P2INCH"))
    )
    (comp (ref "R7")
      (value "470")
      (footprint "eagle-import:R_P2INCH")
      (libsource (lib "eagle-import") (part "R_P2INCH"))
    )
    (comp (ref "R8")
      (value "470")
      (footprint "eagle-import:R_P2INCH")
      (libsource (lib "eagle-import") (part "R_P2INCH"))
    )
    (comp (ref "R9")
      (value "470")
      (footprint "eagle-import:R_P2INCH")
      (libsource (lib "eagle-import") (part "R_P2INCH"))
    )
    (comp (ref "R10")
      (value "10k")
      (footprint "eagle-import:R_P2INCH")
      (libsource (lib "eagle-import") (part "R_P2INCH"))
    )
    (comp (ref "R11")
      (value "10k")
      (footprint "eagle-import:R_P2INCH")
      (libsource (lib "eagle-import") (part "R_P2INCH"))
    )
    (comp (ref "R12")
      (value "10k")
      (footprint "eagle-import:R_P2INCH")
      (libsource (lib "eagle-import") (part "R_P2INCH"))
    )
    (comp (ref "R153")
      (value "470")
      (footprint "eagle-import:R_P2INCH")
      (libsource (lib "eagle-import") (part "R_P2INCH"))
    )
    (comp (ref "R154")
      (value "470")
      (footprint "eagle-import:R_P2INCH")
      (libsource (lib "eagle-import") (part "R_P2INCH"))
    )
    (comp (ref "R155")
      (value "470")
      (footprint "eagle-import:R_P2INCH")
      (libsource (lib "eagle-import") (part "R_P2INCH"))
    )
    (comp (ref "R156")
      (value "470")
      (footprint "eagle-import:R_P2INCH")
      (libsource (lib "eagle-import") (part "R_P2INCH"))
    )
    (comp (ref "R157")
      (value "470")
      (footprint "eagle-import:R_P2INCH")
      (libsource (lib "eagle-import") (part "R_P2INCH"))
    )
    (comp (ref "R158")
      (value "470")
      (footprint "eagle-import:R_P2INCH")
      (libsource (lib "eagle-import") (part "R_P2INCH"))
    )
    (comp (ref "R159")
      (value "470")
      (footprint "eagle-import:R_P2INCH")
      (libsource (lib "eagle-import") (part "R_P2INCH"))
    )
    (comp (ref "R160")
      (value "470")
      (footprint "eagle-import:R_P2INCH")
      (libsource (lib "eagle-import") (part "R_P2INCH"))
    )
    (comp (ref "D11")
      (value "SA10-21SRWA")
      (footprint "eagle-import:SA10")
      (libsource (lib "eagle-import") (part "SA10-21SRWA"))
    )
    (comp (ref "D12")
      (value "SA10-21SRWA")
      (footprint "eagle-import:SA10")
      (libsource (lib "eagle-import") (part "SA10-21SRWA"))
    )
    (comp (ref "J31")
      (value "JUMP_3X1")
      (footprint "eagle-import:JUMP_3X1")
      (libsource (lib "eagle-import") (part "JUMP_3X1"))
    )
    (comp (ref "J32")
      (value "JUMP_3X1")
      (footprint "eagle-import:JUMP_3X1")
      (libsource (lib "eagle-import") (part "JUMP_3X1"))
    )
    (comp (ref "J33")
      (value "JUMP_3X1")
      (footprint "eagle-import:JUMP_3X1")
      (libsource (lib "eagle-import") (part "JUMP_3X1"))
    )
    (comp (ref "J34")
      (value "JUMP_3X1")
      (footprint "eagle-import:JUMP_3X1")
      (libsource (lib "eagle-import") (part "JUMP_3X1"))
    )
    (comp (ref "J35")
      (value "JUMP_3X1")
      (footprint "eagle-import:JUMP_3X1")
      (libsource (lib "eagle-import") (part "JUMP_3X1"))
    )
    (comp (ref "J36")
      (value "JUMP_3X1")
      (footprint "eagle-import:JUMP_3X1")
      (libsource (lib "eagle-import") (part "JUMP_3X1"))
    )
    (comp (ref "Q51")
      (value "2N7000")
      (footprint "eagle-import:TO92-DGS")
      (libsource (lib "eagle-import") (part "2N7000"))
    )
    (comp (ref "Q52")
      (value "2N7000")
      (footprint "eagle-import:TO92-DGS")
      (libsource (lib "eagle-import") (part "2N7000"))
    )
    (comp (ref "Q53")
      (value "2N7000")
      (footprint "eagle-import:TO92-DGS")
      (libsource (lib "eagle-import") (part "2N7000"))
    )
    (comp (ref "Q54")
      (value "2N7000")
      (footprint "eagle-import:TO92-DGS")
      (libsource (lib "eagle-import") (part "2N7000"))
    )
    (comp (ref "Q55")
      (value "2N7000")
      (footprint "eagle-import:TO92-DGS")
      (libsource (lib "eagle-import") (part "2N7000"))
    )
    (comp (ref "Q56")
      (value "2N7000")
      (footprint "eagle-import:TO92-DGS")
      (libsource (lib "eagle-import") (part "2N7000"))
    )
    (comp (ref "Q57")
      (value "2N7000")
      (footprint "eagle-import:TO92-DGS")
      (libsource (lib "eagle-import") (part "2N7000"))
    )
    (comp (ref "Q58")
      (value "2N7000")
      (footprint "eagle-import:TO92-DGS")
      (libsource (lib "eagle-import") (part "2N7000"))
    )
    (comp (ref "Q59")
      (value "2N7000")
      (footprint "eagle-import:TO92-DGS")
      (libsource (lib "eagle-import") (part "2N7000"))
    )
    (comp (ref "Q60")
      (value "2N7000")
      (footprint "eagle-import:TO92-DGS")
      (libsource (lib "eagle-import") (part "2N7000"))
    )
    (comp (ref "R61")
      (value "470")
      (footprint "eagle-import:R_P2INCH")
      (libsource (lib "eagle-import") (part "R_P2INCH"))
    )
    (comp (ref "R62")
      (value "470")
      (footprint "eagle-import:R_P2INCH")
      (libsource (lib "eagle-import") (part "R_P2INCH"))
    )
    (comp (ref "R63")
      (value "470")
      (footprint "eagle-import:R_P2INCH")
      (libsource (lib "eagle-import") (part "R_P2INCH"))
    )
    (comp (ref "R64")
      (value "10k")
      (footprint "eagle-import:R_P2INCH")
      (libsource (lib "eagle-import") (part "R_P2INCH"))
    )
    (comp (ref "R65")
      (value "10k")
      (footprint "eagle-import:R_P2INCH")
      (libsource (lib "eagle-import") (part "R_P2INCH"))
    )
    (comp (ref "R66")
      (value "10k")
      (footprint "eagle-import:R_P2INCH")
      (libsource (lib "eagle-import") (part "R_P2INCH"))
    )
    (comp (ref "R67")
      (value "470")
      (footprint "eagle-import:R_P2INCH")
      (libsource (lib "eagle-import") (part "R_P2INCH"))
    )
    (comp (ref "R68")
      (value "470")
      (footprint "eagle-import:R_P2INCH")
      (libsource (lib "eagle-import") (part "R_P2INCH"))
    )
    (comp (ref "R69")
      (value "470")
      (footprint "eagle-import:R_P2INCH")
      (libsource (lib "eagle-import") (part "R_P2INCH"))
    )
    (comp (ref "R70")
      (value "10k")
      (footprint "eagle-import:R_P2INCH")
      (libsource (lib "eagle-import") (part "R_P2INCH"))
    )
    (comp (ref "R71")
      (value "10k")
      (footprint "eagle-import:R_P2INCH")
      (libsource (lib "eagle-import") (part "R_P2INCH"))
    )
    (comp (ref "R72")
      (value "10k")
      (footprint "eagle-import:R_P2INCH")
      (libsource (lib "eagle-import") (part "R_P2INCH"))
    )
    (comp (ref "R113")
      (value "470")
      (footprint "eagle-import:R_P2INCH")
      (libsource (lib "eagle-import") (part "R_P2INCH"))
    )
    (comp (ref "R114")
      (value "470")
      (footprint "eagle-import:R_P2INCH")
      (libsource (lib "eagle-import") (part "R_P2INCH"))
    )
    (comp (ref "R115")
      (value "470")
      (footprint "eagle-import:R_P2INCH")
      (libsource (lib "eagle-import") (part "R_P2INCH"))
    )
    (comp (ref "R116")
      (value "470")
      (footprint "eagle-import:R_P2INCH")
      (libsource (lib "eagle-import") (part "R_P2INCH"))
    )
    (comp (ref "R117")
      (value "470")
      (footprint "eagle-import:R_P2INCH")
      (libsource (lib "eagle-import") (part "R_P2INCH"))
    )
    (comp (ref "R118")
      (value "470")
      (footprint "eagle-import:R_P2INCH")
      (libsource (lib "eagle-import") (part "R_P2INCH"))
    )
    (comp (ref "R119")
      (value "470")
      (footprint "eagle-import:R_P2INCH")
      (libsource (lib "eagle-import") (part "R_P2INCH"))
    )
    (comp (ref "R120")
      (value "470")
      (footprint "eagle-import:R_P2INCH")
      (libsource (lib "eagle-import") (part "R_P2INCH"))
    )
    (comp (ref "D15")
      (value "SA10-21SRWA")
      (footprint "eagle-import:SA10")
      (libsource (lib "eagle-import") (part "SA10-21SRWA"))
    )
    (comp (ref "D16")
      (value "SA10-21SRWA")
      (footprint "eagle-import:SA10")
      (libsource (lib "eagle-import") (part "SA10-21SRWA"))
    )
    (comp (ref "J43")
      (value "JUMP_3X1")
      (footprint "eagle-import:JUMP_3X1")
      (libsource (lib "eagle-import") (part "JUMP_3X1"))
    )
    (comp (ref "J44")
      (value "JUMP_3X1")
      (footprint "eagle-import:JUMP_3X1")
      (libsource (lib "eagle-import") (part "JUMP_3X1"))
    )
    (comp (ref "J45")
      (value "JUMP_3X1")
      (footprint "eagle-import:JUMP_3X1")
      (libsource (lib "eagle-import") (part "JUMP_3X1"))
    )
    (comp (ref "J46")
      (value "JUMP_3X1")
      (footprint "eagle-import:JUMP_3X1")
      (libsource (lib "eagle-import") (part "JUMP_3X1"))
    )
    (comp (ref "J47")
      (value "JUMP_3X1")
      (footprint "eagle-import:JUMP_3X1")
      (libsource (lib "eagle-import") (part "JUMP_3X1"))
    )
    (comp (ref "J48")
      (value "JUMP_3X1")
      (footprint "eagle-import:JUMP_3X1")
      (libsource (lib "eagle-import") (part "JUMP_3X1"))
    )
    (comp (ref "Q71")
      (value "2N7000")
      (footprint "eagle-import:TO92-DGS")
      (libsource (lib "eagle-import") (part "2N7000"))
    )
    (comp (ref "Q72")
      (value "2N7000")
      (footprint "eagle-import:TO92-DGS")
      (libsource (lib "eagle-import") (part "2N7000"))
    )
    (comp (ref "Q73")
      (value "2N7000")
      (footprint "eagle-import:TO92-DGS")
      (libsource (lib "eagle-import") (part "2N7000"))
    )
    (comp (ref "Q74")
      (value "2N7000")
      (footprint "eagle-import:TO92-DGS")
      (libsource (lib "eagle-import") (part "2N7000"))
    )
    (comp (ref "Q75")
      (value "2N7000")
      (footprint "eagle-import:TO92-DGS")
      (libsource (lib "eagle-import") (part "2N7000"))
    )
    (comp (ref "Q76")
      (value "2N7000")
      (footprint "eagle-import:TO92-DGS")
      (libsource (lib "eagle-import") (part "2N7000"))
    )
    (comp (ref "Q77")
      (value "2N7000")
      (footprint "eagle-import:TO92-DGS")
      (libsource (lib "eagle-import") (part "2N7000"))
    )
    (comp (ref "Q78")
      (value "2N7000")
      (footprint "eagle-import:TO92-DGS")
      (libsource (lib "eagle-import") (part "2N7000"))
    )
    (comp (ref "Q79")
      (value "2N7000")
      (footprint "eagle-import:TO92-DGS")
      (libsource (lib "eagle-import") (part "2N7000"))
    )
    (comp (ref "Q80")
      (value "2N7000")
      (footprint "eagle-import:TO92-DGS")
      (libsource (lib "eagle-import") (part "2N7000"))
    )
    (comp (ref "R85")
      (value "470")
      (footprint "eagle-import:R_P2INCH")
      (libsource (lib "eagle-import") (part "R_P2INCH"))
    )
    (comp (ref "R86")
      (value "470")
      (footprint "eagle-import:R_P2INCH")
      (libsource (lib "eagle-import") (part "R_P2INCH"))
    )
    (comp (ref "R87")
      (value "470")
      (footprint "eagle-import:R_P2INCH")
      (libsource (lib "eagle-import") (part "R_P2INCH"))
    )
    (comp (ref "R88")
      (value "10k")
      (footprint "eagle-import:R_P2INCH")
      (libsource (lib "eagle-import") (part "R_P2INCH"))
    )
    (comp (ref "R89")
      (value "10k")
      (footprint "eagle-import:R_P2INCH")
      (libsource (lib "eagle-import") (part "R_P2INCH"))
    )
    (comp (ref "R90")
      (value "10k")
      (footprint "eagle-import:R_P2INCH")
      (libsource (lib "eagle-import") (part "R_P2INCH"))
    )
    (comp (ref "R91")
      (value "470")
      (footprint "eagle-import:R_P2INCH")
      (libsource (lib "eagle-import") (part "R_P2INCH"))
    )
    (comp (ref "R92")
      (value "470")
      (footprint "eagle-import:R_P2INCH")
      (libsource (lib "eagle-import") (part "R_P2INCH"))
    )
    (comp (ref "R93")
      (value "470")
      (footprint "eagle-import:R_P2INCH")
      (libsource (lib "eagle-import") (part "R_P2INCH"))
    )
    (comp (ref "R94")
      (value "10k")
      (footprint "eagle-import:R_P2INCH")
      (libsource (lib "eagle-import") (part "R_P2INCH"))
    )
    (comp (ref "R95")
      (value "10k")
      (footprint "eagle-import:R_P2INCH")
      (libsource (lib "eagle-import") (part "R_P2INCH"))
    )
    (comp (ref "R96")
      (value "10k")
      (footprint "eagle-import:R_P2INCH")
      (libsource (lib "eagle-import") (part "R_P2INCH"))
    )
    (comp (ref "R105")
      (value "470")
      (footprint "eagle-import:R_P2INCH")
      (libsource (lib "eagle-import") (part "R_P2INCH"))
    )
    (comp (ref "R106")
      (value "470")
      (footprint "eagle-import:R_P2INCH")
      (libsource (lib "eagle-import") (part "R_P2INCH"))
    )
    (comp (ref "R107")
      (value "470")
      (footprint "eagle-import:R_P2INCH")
      (libsource (lib "eagle-import") (part "R_P2INCH"))
    )
    (comp (ref "R108")
      (value "470")
      (footprint "eagle-import:R_P2INCH")
      (libsource (lib "eagle-import") (part "R_P2INCH"))
    )
    (comp (ref "R109")
      (value "470")
      (footprint "eagle-import:R_P2INCH")
      (libsource (lib "eagle-import") (part "R_P2INCH"))
    )
    (comp (ref "R110")
      (value "470")
      (footprint "eagle-import:R_P2INCH")
      (libsource (lib "eagle-import") (part "R_P2INCH"))
    )
    (comp (ref "R111")
      (value "470")
      (footprint "eagle-import:R_P2INCH")
      (libsource (lib "eagle-import") (part "R_P2INCH"))
    )
    (comp (ref "R112")
      (value "470")
      (footprint "eagle-import:R_P2INCH")
      (libsource (lib "eagle-import") (part "R_P2INCH"))
    )
    (comp (ref "D7")
      (value "SA10-21SRWA")
      (footprint "eagle-import:SA10")
      (libsource (lib "eagle-import") (part "SA10-21SRWA"))
    )
    (comp (ref "D8")
      (value "SA10-21SRWA")
      (footprint "eagle-import:SA10")
      (libsource (lib "eagle-import") (part "SA10-21SRWA"))
    )
    (comp (ref "J19")
      (value "JUMP_3X1")
      (footprint "eagle-import:JUMP_3X1")
      (libsource (lib "eagle-import") (part "JUMP_3X1"))
    )
    (comp (ref "J20")
      (value "JUMP_3X1")
      (footprint "eagle-import:JUMP_3X1")
      (libsource (lib "eagle-import") (part "JUMP_3X1"))
    )
    (comp (ref "J21")
      (value "JUMP_3X1")
      (footprint "eagle-import:JUMP_3X1")
      (libsource (lib "eagle-import") (part "JUMP_3X1"))
    )
    (comp (ref "J22")
      (value "JUMP_3X1")
      (footprint "eagle-import:JUMP_3X1")
      (libsource (lib "eagle-import") (part "JUMP_3X1"))
    )
    (comp (ref "J23")
      (value "JUMP_3X1")
      (footprint "eagle-import:JUMP_3X1")
      (libsource (lib "eagle-import") (part "JUMP_3X1"))
    )
    (comp (ref "J24")
      (value "JUMP_3X1")
      (footprint "eagle-import:JUMP_3X1")
      (libsource (lib "eagle-import") (part "JUMP_3X1"))
    )
    (comp (ref "Q31")
      (value "2N7000")
      (footprint "eagle-import:TO92-DGS")
      (libsource (lib "eagle-import") (part "2N7000"))
    )
    (comp (ref "Q32")
      (value "2N7000")
      (footprint "eagle-import:TO92-DGS")
      (libsource (lib "eagle-import") (part "2N7000"))
    )
    (comp (ref "Q33")
      (value "2N7000")
      (footprint "eagle-import:TO92-DGS")
      (libsource (lib "eagle-import") (part "2N7000"))
    )
    (comp (ref "Q34")
      (value "2N7000")
      (footprint "eagle-import:TO92-DGS")
      (libsource (lib "eagle-import") (part "2N7000"))
    )
    (comp (ref "Q35")
      (value "2N7000")
      (footprint "eagle-import:TO92-DGS")
      (libsource (lib "eagle-import") (part "2N7000"))
    )
    (comp (ref "Q36")
      (value "2N7000")
      (footprint "eagle-import:TO92-DGS")
      (libsource (lib "eagle-import") (part "2N7000"))
    )
    (comp (ref "Q37")
      (value "2N7000")
      (footprint "eagle-import:TO92-DGS")
      (libsource (lib "eagle-import") (part "2N7000"))
    )
    (comp (ref "Q38")
      (value "2N7000")
      (footprint "eagle-import:TO92-DGS")
      (libsource (lib "eagle-import") (part "2N7000"))
    )
    (comp (ref "Q39")
      (value "2N7000")
      (footprint "eagle-import:TO92-DGS")
      (libsource (lib "eagle-import") (part "2N7000"))
    )
    (comp (ref "Q40")
      (value "2N7000")
      (footprint "eagle-import:TO92-DGS")
      (libsource (lib "eagle-import") (part "2N7000"))
    )
    (comp (ref "R37")
      (value "470")
      (footprint "eagle-import:R_P2INCH")
      (libsource (lib "eagle-import") (part "R_P2INCH"))
    )
    (comp (ref "R38")
      (value "470")
      (footprint "eagle-import:R_P2INCH")
      (libsource (lib "eagle-import") (part "R_P2INCH"))
    )
    (comp (ref "R39")
      (value "470")
      (footprint "eagle-import:R_P2INCH")
      (libsource (lib "eagle-import") (part "R_P2INCH"))
    )
    (comp (ref "R40")
      (value "10k")
      (footprint "eagle-import:R_P2INCH")
      (libsource (lib "eagle-import") (part "R_P2INCH"))
    )
    (comp (ref "R41")
      (value "10k")
      (footprint "eagle-import:R_P2INCH")
      (libsource (lib "eagle-import") (part "R_P2INCH"))
    )
    (comp (ref "R42")
      (value "10k")
      (footprint "eagle-import:R_P2INCH")
      (libsource (lib "eagle-import") (part "R_P2INCH"))
    )
    (comp (ref "R43")
      (value "470")
      (footprint "eagle-import:R_P2INCH")
      (libsource (lib "eagle-import") (part "R_P2INCH"))
    )
    (comp (ref "R44")
      (value "470")
      (footprint "eagle-import:R_P2INCH")
      (libsource (lib "eagle-import") (part "R_P2INCH"))
    )
    (comp (ref "R45")
      (value "470")
      (footprint "eagle-import:R_P2INCH")
      (libsource (lib "eagle-import") (part "R_P2INCH"))
    )
    (comp (ref "R46")
      (value "10k")
      (footprint "eagle-import:R_P2INCH")
      (libsource (lib "eagle-import") (part "R_P2INCH"))
    )
    (comp (ref "R47")
      (value "10k")
      (footprint "eagle-import:R_P2INCH")
      (libsource (lib "eagle-import") (part "R_P2INCH"))
    )
    (comp (ref "R48")
      (value "10k")
      (footprint "eagle-import:R_P2INCH")
      (libsource (lib "eagle-import") (part "R_P2INCH"))
    )
    (comp (ref "R129")
      (value "470")
      (footprint "eagle-import:R_P2INCH")
      (libsource (lib "eagle-import") (part "R_P2INCH"))
    )
    (comp (ref "R130")
      (value "470")
      (footprint "eagle-import:R_P2INCH")
      (libsource (lib "eagle-import") (part "R_P2INCH"))
    )
    (comp (ref "R131")
      (value "470")
      (footprint "eagle-import:R_P2INCH")
      (libsource (lib "eagle-import") (part "R_P2INCH"))
    )
    (comp (ref "R132")
      (value "470")
      (footprint "eagle-import:R_P2INCH")
      (libsource (lib "eagle-import") (part "R_P2INCH"))
    )
    (comp (ref "R133")
      (value "470")
      (footprint "eagle-import:R_P2INCH")
      (libsource (lib "eagle-import") (part "R_P2INCH"))
    )
    (comp (ref "R134")
      (value "470")
      (footprint "eagle-import:R_P2INCH")
      (libsource (lib "eagle-import") (part "R_P2INCH"))
    )
    (comp (ref "R135")
      (value "470")
      (footprint "eagle-import:R_P2INCH")
      (libsource (lib "eagle-import") (part "R_P2INCH"))
    )
    (comp (ref "R136")
      (value "470")
      (footprint "eagle-import:R_P2INCH")
      (libsource (lib "eagle-import") (part "R_P2INCH"))
    )
    (comp (ref "D9")
      (value "SA10-21SRWA")
      (footprint "eagle-import:SA10")
      (libsource (lib "eagle-import") (part "SA10-21SRWA"))
    )
    (comp (ref "D10")
      (value "SA10-21SRWA")
      (footprint "eagle-import:SA10")
      (libsource (lib "eagle-import") (part "SA10-21SRWA"))
    )
    (comp (ref "J25")
      (value "JUMP_3X1")
      (footprint "eagle-import:JUMP_3X1")
      (libsource (lib "eagle-import") (part "JUMP_3X1"))
    )
    (comp (ref "J26")
      (value "JUMP_3X1")
      (footprint "eagle-import:JUMP_3X1")
      (libsource (lib "eagle-import") (part "JUMP_3X1"))
    )
    (comp (ref "J27")
      (value "JUMP_3X1")
      (footprint "eagle-import:JUMP_3X1")
      (libsource (lib "eagle-import") (part "JUMP_3X1"))
    )
    (comp (ref "J28")
      (value "JUMP_3X1")
      (footprint "eagle-import:JUMP_3X1")
      (libsource (lib "eagle-import") (part "JUMP_3X1"))
    )
    (comp (ref "J29")
      (value "JUMP_3X1")
      (footprint "eagle-import:JUMP_3X1")
      (libsource (lib "eagle-import") (part "JUMP_3X1"))
    )
    (comp (ref "J30")
      (value "JUMP_3X1")
      (footprint "eagle-import:JUMP_3X1")
      (libsource (lib "eagle-import") (part "JUMP_3X1"))
    )
    (comp (ref "Q41")
      (value "2N7000")
      (footprint "eagle-import:TO92-DGS")
      (libsource (lib "eagle-import") (part "2N7000"))
    )
    (comp (ref "Q42")
      (value "2N7000")
      (footprint "eagle-import:TO92-DGS")
      (libsource (lib "eagle-import") (part "2N7000"))
    )
    (comp (ref "Q43")
      (value "2N7000")
      (footprint "eagle-import:TO92-DGS")
      (libsource (lib "eagle-import") (part "2N7000"))
    )
    (comp (ref "Q44")
      (value "2N7000")
      (footprint "eagle-import:TO92-DGS")
      (libsource (lib "eagle-import") (part "2N7000"))
    )
    (comp (ref "Q45")
      (value "2N7000")
      (footprint "eagle-import:TO92-DGS")
      (libsource (lib "eagle-import") (part "2N7000"))
    )
    (comp (ref "Q46")
      (value "2N7000")
      (footprint "eagle-import:TO92-DGS")
      (libsource (lib "eagle-import") (part "2N7000"))
    )
    (comp (ref "Q47")
      (value "2N7000")
      (footprint "eagle-import:TO92-DGS")
      (libsource (lib "eagle-import") (part "2N7000"))
    )
    (comp (ref "Q48")
      (value "2N7000")
      (footprint "eagle-import:TO92-DGS")
      (libsource (lib "eagle-import") (part "2N7000"))
    )
    (comp (ref "Q49")
      (value "2N7000")
      (footprint "eagle-import:TO92-DGS")
      (libsource (lib "eagle-import") (part "2N7000"))
    )
    (comp (ref "Q50")
      (value "2N7000")
      (footprint "eagle-import:TO92-DGS")
      (libsource (lib "eagle-import") (part "2N7000"))
    )
    (comp (ref "R49")
      (value "470")
      (footprint "eagle-import:R_P2INCH")
      (libsource (lib "eagle-import") (part "R_P2INCH"))
    )
    (comp (ref "R50")
      (value "470")
      (footprint "eagle-import:R_P2INCH")
      (libsource (lib "eagle-import") (part "R_P2INCH"))
    )
    (comp (ref "R51")
      (value "470")
      (footprint "eagle-import:R_P2INCH")
      (libsource (lib "eagle-import") (part "R_P2INCH"))
    )
    (comp (ref "R52")
      (value "10k")
      (footprint "eagle-import:R_P2INCH")
      (libsource (lib "eagle-import") (part "R_P2INCH"))
    )
    (comp (ref "R53")
      (value "10k")
      (footprint "eagle-import:R_P2INCH")
      (libsource (lib "eagle-import") (part "R_P2INCH"))
    )
    (comp (ref "R54")
      (value "10k")
      (footprint "eagle-import:R_P2INCH")
      (libsource (lib "eagle-import") (part "R_P2INCH"))
    )
    (comp (ref "R55")
      (value "470")
      (footprint "eagle-import:R_P2INCH")
      (libsource (lib "eagle-import") (part "R_P2INCH"))
    )
    (comp (ref "R56")
      (value "470")
      (footprint "eagle-import:R_P2INCH")
      (libsource (lib "eagle-import") (part "R_P2INCH"))
    )
    (comp (ref "R57")
      (value "470")
      (footprint "eagle-import:R_P2INCH")
      (libsource (lib "eagle-import") (part "R_P2INCH"))
    )
    (comp (ref "R58")
      (value "10k")
      (footprint "eagle-import:R_P2INCH")
      (libsource (lib "eagle-import") (part "R_P2INCH"))
    )
    (comp (ref "R59")
      (value "10k")
      (footprint "eagle-import:R_P2INCH")
      (libsource (lib "eagle-import") (part "R_P2INCH"))
    )
    (comp (ref "R60")
      (value "10k")
      (footprint "eagle-import:R_P2INCH")
      (libsource (lib "eagle-import") (part "R_P2INCH"))
    )
    (comp (ref "R121")
      (value "470")
      (footprint "eagle-import:R_P2INCH")
      (libsource (lib "eagle-import") (part "R_P2INCH"))
    )
    (comp (ref "R122")
      (value "470")
      (footprint "eagle-import:R_P2INCH")
      (libsource (lib "eagle-import") (part "R_P2INCH"))
    )
    (comp (ref "R123")
      (value "470")
      (footprint "eagle-import:R_P2INCH")
      (libsource (lib "eagle-import") (part "R_P2INCH"))
    )
    (comp (ref "R124")
      (value "470")
      (footprint "eagle-import:R_P2INCH")
      (libsource (lib "eagle-import") (part "R_P2INCH"))
    )
    (comp (ref "R125")
      (value "470")
      (footprint "eagle-import:R_P2INCH")
      (libsource (lib "eagle-import") (part "R_P2INCH"))
    )
    (comp (ref "R126")
      (value "470")
      (footprint "eagle-import:R_P2INCH")
      (libsource (lib "eagle-import") (part "R_P2INCH"))
    )
    (comp (ref "R127")
      (value "470")
      (footprint "eagle-import:R_P2INCH")
      (libsource (lib "eagle-import") (part "R_P2INCH"))
    )
    (comp (ref "R128")
      (value "470")
      (footprint "eagle-import:R_P2INCH")
      (libsource (lib "eagle-import") (part "R_P2INCH"))
    )
    (comp (ref "D5")
      (value "SA10-21SRWA")
      (footprint "eagle-import:SA10")
      (libsource (lib "eagle-import") (part "SA10-21SRWA"))
    )
    (comp (ref "D6")
      (value "SA10-21SRWA")
      (footprint "eagle-import:SA10")
      (libsource (lib "eagle-import") (part "SA10-21SRWA"))
    )
    (comp (ref "J13")
      (value "JUMP_3X1")
      (footprint "eagle-import:JUMP_3X1")
      (libsource (lib "eagle-import") (part "JUMP_3X1"))
    )
    (comp (ref "J14")
      (value "JUMP_3X1")
      (footprint "eagle-import:JUMP_3X1")
      (libsource (lib "eagle-import") (part "JUMP_3X1"))
    )
    (comp (ref "J15")
      (value "JUMP_3X1")
      (footprint "eagle-import:JUMP_3X1")
      (libsource (lib "eagle-import") (part "JUMP_3X1"))
    )
    (comp (ref "J16")
      (value "JUMP_3X1")
      (footprint "eagle-import:JUMP_3X1")
      (libsource (lib "eagle-import") (part "JUMP_3X1"))
    )
    (comp (ref "J17")
      (value "JUMP_3X1")
      (footprint "eagle-import:JUMP_3X1")
      (libsource (lib "eagle-import") (part "JUMP_3X1"))
    )
    (comp (ref "J18")
      (value "JUMP_3X1")
      (footprint "eagle-import:JUMP_3X1")
      (libsource (lib "eagle-import") (part "JUMP_3X1"))
    )
    (comp (ref "Q21")
      (value "2N7000")
      (footprint "eagle-import:TO92-DGS")
      (libsource (lib "eagle-import") (part "2N7000"))
    )
    (comp (ref "Q22")
      (value "2N7000")
      (footprint "eagle-import:TO92-DGS")
      (libsource (lib "eagle-import") (part "2N7000"))
    )
    (comp (ref "Q23")
      (value "2N7000")
      (footprint "eagle-import:TO92-DGS")
      (libsource (lib "eagle-import") (part "2N7000"))
    )
    (comp (ref "Q24")
      (value "2N7000")
      (footprint "eagle-import:TO92-DGS")
      (libsource (lib "eagle-import") (part "2N7000"))
    )
    (comp (ref "Q25")
      (value "2N7000")
      (footprint "eagle-import:TO92-DGS")
      (libsource (lib "eagle-import") (part "2N7000"))
    )
    (comp (ref "Q26")
      (value "2N7000")
      (footprint "eagle-import:TO92-DGS")
      (libsource (lib "eagle-import") (part "2N7000"))
    )
    (comp (ref "Q27")
      (value "2N7000")
      (footprint "eagle-import:TO92-DGS")
      (libsource (lib "eagle-import") (part "2N7000"))
    )
    (comp (ref "Q28")
      (value "2N7000")
      (footprint "eagle-import:TO92-DGS")
      (libsource (lib "eagle-import") (part "2N7000"))
    )
    (comp (ref "Q29")
      (value "2N7000")
      (footprint "eagle-import:TO92-DGS")
      (libsource (lib "eagle-import") (part "2N7000"))
    )
    (comp (ref "Q30")
      (value "2N7000")
      (footprint "eagle-import:TO92-DGS")
      (libsource (lib "eagle-import") (part "2N7000"))
    )
    (comp (ref "R25")
      (value "470")
      (footprint "eagle-import:R_P2INCH")
      (libsource (lib "eagle-import") (part "R_P2INCH"))
    )
    (comp (ref "R26")
      (value "470")
      (footprint "eagle-import:R_P2INCH")
      (libsource (lib "eagle-import") (part "R_P2INCH"))
    )
    (comp (ref "R27")
      (value "470")
      (footprint "eagle-import:R_P2INCH")
      (libsource (lib "eagle-import") (part "R_P2INCH"))
    )
    (comp (ref "R28")
      (value "10k")
      (footprint "eagle-import:R_P2INCH")
      (libsource (lib "eagle-import") (part "R_P2INCH"))
    )
    (comp (ref "R29")
      (value "10k")
      (footprint "eagle-import:R_P2INCH")
      (libsource (lib "eagle-import") (part "R_P2INCH"))
    )
    (comp (ref "R30")
      (value "10k")
      (footprint "eagle-import:R_P2INCH")
      (libsource (lib "eagle-import") (part "R_P2INCH"))
    )
    (comp (ref "R31")
      (value "470")
      (footprint "eagle-import:R_P2INCH")
      (libsource (lib "eagle-import") (part "R_P2INCH"))
    )
    (comp (ref "R32")
      (value "470")
      (footprint "eagle-import:R_P2INCH")
      (libsource (lib "eagle-import") (part "R_P2INCH"))
    )
    (comp (ref "R33")
      (value "470")
      (footprint "eagle-import:R_P2INCH")
      (libsource (lib "eagle-import") (part "R_P2INCH"))
    )
    (comp (ref "R34")
      (value "10k")
      (footprint "eagle-import:R_P2INCH")
      (libsource (lib "eagle-import") (part "R_P2INCH"))
    )
    (comp (ref "R35")
      (value "10k")
      (footprint "eagle-import:R_P2INCH")
      (libsource (lib "eagle-import") (part "R_P2INCH"))
    )
    (comp (ref "R36")
      (value "10k")
      (footprint "eagle-import:R_P2INCH")
      (libsource (lib "eagle-import") (part "R_P2INCH"))
    )
    (comp (ref "R137")
      (value "470")
      (footprint "eagle-import:R_P2INCH")
      (libsource (lib "eagle-import") (part "R_P2INCH"))
    )
    (comp (ref "R138")
      (value "470")
      (footprint "eagle-import:R_P2INCH")
      (libsource (lib "eagle-import") (part "R_P2INCH"))
    )
    (comp (ref "R139")
      (value "470")
      (footprint "eagle-import:R_P2INCH")
      (libsource (lib "eagle-import") (part "R_P2INCH"))
    )
    (comp (ref "R140")
      (value "470")
      (footprint "eagle-import:R_P2INCH")
      (libsource (lib "eagle-import") (part "R_P2INCH"))
    )
    (comp (ref "R141")
      (value "470")
      (footprint "eagle-import:R_P2INCH")
      (libsource (lib "eagle-import") (part "R_P2INCH"))
    )
    (comp (ref "R142")
      (value "470")
      (footprint "eagle-import:R_P2INCH")
      (libsource (lib "eagle-import") (part "R_P2INCH"))
    )
    (comp (ref "R143")
      (value "470")
      (footprint "eagle-import:R_P2INCH")
      (libsource (lib "eagle-import") (part "R_P2INCH"))
    )
    (comp (ref "R144")
      (value "470")
      (footprint "eagle-import:R_P2INCH")
      (libsource (lib "eagle-import") (part "R_P2INCH"))
    )
  )
  (nets
    (net (code "1") (name "+5V") (class "Default")
      (node (ref "C1") (pin "A") (pinfunction "A_A") (pintype "passive"))
      (node (ref "C3") (pin "1") (pinfunction "1_1") (pintype "passive"))
      (node (ref "PP2") (pin "1") (pinfunction "P$1_1") (pintype "bidirectional"))
      (node (ref "R10") (pin "2") (pinfunction "2_2") (pintype "passive"))
      (node (ref "R11") (pin "2") (pinfunction "2_2") (pintype "passive"))
      (node (ref "R12") (pin "2") (pinfunction "2_2") (pintype "passive"))
      (node (ref "R16") (pin "2") (pinfunction "2_2") (pintype "passive"))
      (node (ref "R17") (pin "2") (pinfunction "2_2") (pintype "passive"))
      (node (ref "R18") (pin "2") (pinfunction "2_2") (pintype "passive"))
      (node (ref "R22") (pin "2") (pinfunction "2_2") (pintype "passive"))
      (node (ref "R23") (pin "2") (pinfunction "2_2") (pintype "passive"))
      (node (ref "R24") (pin "2") (pinfunction "2_2") (pintype "passive"))
      (node (ref "R28") (pin "2") (pinfunction "2_2") (pintype "passive"))
      (node (ref "R29") (pin "2") (pinfunction "2_2") (pintype "passive"))
      (node (ref "R30") (pin "2") (pinfunction "2_2") (pintype "passive"))
      (node (ref "R34") (pin "2") (pinfunction "2_2") (pintype "passive"))
      (node (ref "R35") (pin "2") (pinfunction "2_2") (pintype "passive"))
      (node (ref "R36") (pin "2") (pinfunction "2_2") (pintype "passive"))
      (node (ref "R4") (pin "2") (pinfunction "2_2") (pintype "passive"))
      (node (ref "R40") (pin "2") (pinfunction "2_2") (pintype "passive"))
      (node (ref "R41") (pin "2") (pinfunction "2_2") (pintype "passive"))
      (node (ref "R42") (pin "2") (pinfunction "2_2") (pintype "passive"))
      (node (ref "R46") (pin "2") (pinfunction "2_2") (pintype "passive"))
      (node (ref "R47") (pin "2") (pinfunction "2_2") (pintype "passive"))
      (node (ref "R48") (pin "2") (pinfunction "2_2") (pintype "passive"))
      (node (ref "R5") (pin "2") (pinfunction "2_2") (pintype "passive"))
      (node (ref "R52") (pin "2") (pinfunction "2_2") (pintype "passive"))
      (node (ref "R53") (pin "2") (pinfunction "2_2") (pintype "passive"))
      (node (ref "R54") (pin "2") (pinfunction "2_2") (pintype "passive"))
      (node (ref "R58") (pin "2") (pinfunction "2_2") (pintype "passive"))
      (node (ref "R59") (pin "2") (pinfunction "2_2") (pintype "passive"))
      (node (ref "R6") (pin "2") (pinfunction "2_2") (pintype "passive"))
      (node (ref "R60") (pin "2") (pinfunction "2_2") (pintype "passive"))
      (node (ref "R64") (pin "2") (pinfunction "2_2") (pintype "passive"))
      (node (ref "R65") (pin "2") (pinfunction "2_2") (pintype "passive"))
      (node (ref "R66") (pin "2") (pinfunction "2_2") (pintype "passive"))
      (node (ref "R70") (pin "2") (pinfunction "2_2") (pintype "passive"))
      (node (ref "R71") (pin "2") (pinfunction "2_2") (pintype "passive"))
      (node (ref "R72") (pin "2") (pinfunction "2_2") (pintype "passive"))
      (node (ref "R76") (pin "2") (pinfunction "2_2") (pintype "passive"))
      (node (ref "R77") (pin "2") (pinfunction "2_2") (pintype "passive"))
      (node (ref "R78") (pin "2") (pinfunction "2_2") (pintype "passive"))
      (node (ref "R82") (pin "2") (pinfunction "2_2") (pintype "passive"))
      (node (ref "R83") (pin "2") (pinfunction "2_2") (pintype "passive"))
      (node (ref "R84") (pin "2") (pinfunction "2_2") (pintype "passive"))
      (node (ref "R88") (pin "2") (pinfunction "2_2") (pintype "passive"))
      (node (ref "R89") (pin "2") (pinfunction "2_2") (pintype "passive"))
      (node (ref "R90") (pin "2") (pinfunction "2_2") (pintype "passive"))
      (node (ref "R94") (pin "2") (pinfunction "2_2") (pintype "passive"))
      (node (ref "R95") (pin "2") (pinfunction "2_2") (pintype "passive"))
      (node (ref "R96") (pin "2") (pinfunction "2_2") (pintype "passive"))
    )
    (net (code "2") (name "D0") (class "Default")
      (node (ref "J49") (pin "2") (pinfunction "2_2") (pintype "bidirectional"))
      (node (ref "Q4") (pin "G") (pinfunction "G_G") (pintype "passive"))
    )
    (net (code "3") (name "D1") (class "Default")
      (node (ref "J49") (pin "3") (pinfunction "3_3") (pintype "bidirectional"))
      (node (ref "Q9") (pin "G") (pinfunction "G_G") (pintype "passive"))
    )
    (net (code "4") (name "D2") (class "Default")
      (node (ref "J49") (pin "4") (pinfunction "4_4") (pintype "bidirectional"))
      (node (ref "Q14") (pin "G") (pinfunction "G_G") (pintype "passive"))
    )
    (net (code "5") (name "D3") (class "Default")
      (node (ref "J49") (pin "5") (pinfunction "5_5") (pintype "bidirectional"))
      (node (ref "Q19") (pin "G") (pinfunction "G_G") (pintype "passive"))
    )
    (net (code "6") (name "D4") (class "Default")
      (node (ref "J49") (pin "6") (pinfunction "6_6") (pintype "bidirectional"))
      (node (ref "Q24") (pin "G") (pinfunction "G_G") (pintype "passive"))
    )
    (net (code "7") (name "D5") (class "Default")
      (node (ref "J49") (pin "7") (pinfunction "7_7") (pintype "bidirectional"))
      (node (ref "Q29") (pin "G") (pinfunction "G_G") (pintype "passive"))
    )
    (net (code "8") (name "D6") (class "Default")
      (node (ref "J49") (pin "8") (pinfunction "8_8") (pintype "bidirectional"))
      (node (ref "Q34") (pin "G") (pinfunction "G_G") (pintype "passive"))
    )
    (net (code "9") (name "D7") (class "Default")
      (node (ref "J49") (pin "9") (pinfunction "9_9") (pintype "bidirectional"))
      (node (ref "Q39") (pin "G") (pinfunction "G_G") (pintype "passive"))
    )
    (net (code "10") (name "D8") (class "Default")
      (node (ref "J49") (pin "12") (pinfunction "12_12") (pintype "bidirectional"))
      (node (ref "Q44") (pin "G") (pinfunction "G_G") (pintype "passive"))
    )
    (net (code "11") (name "D9") (class "Default")
      (node (ref "J49") (pin "13") (pinfunction "13_13") (pintype "bidirectional"))
      (node (ref "Q49") (pin "G") (pinfunction "G_G") (pintype "passive"))
    )
    (net (code "12") (name "D10") (class "Default")
      (node (ref "J49") (pin "14") (pinfunction "14_14") (pintype "bidirectional"))
      (node (ref "Q54") (pin "G") (pinfunction "G_G") (pintype "passive"))
    )
    (net (code "13") (name "D11") (class "Default")
      (node (ref "J49") (pin "15") (pinfunction "15_15") (pintype "bidirectional"))
      (node (ref "Q59") (pin "G") (pinfunction "G_G") (pintype "passive"))
    )
    (net (code "14") (name "D12") (class "Default")
      (node (ref "J49") (pin "16") (pinfunction "16_16") (pintype "bidirectional"))
      (node (ref "Q64") (pin "G") (pinfunction "G_G") (pintype "passive"))
    )
    (net (code "15") (name "D13") (class "Default")
      (node (ref "J49") (pin "17") (pinfunction "17_17") (pintype "bidirectional"))
      (node (ref "Q69") (pin "G") (pinfunction "G_G") (pintype "passive"))
    )
    (net (code "16") (name "D14") (class "Default")
      (node (ref "J49") (pin "18") (pinfunction "18_18") (pintype "bidirectional"))
      (node (ref "Q74") (pin "G") (pinfunction "G_G") (pintype "passive"))
    )
    (net (code "17") (name "D15") (class "Default")
      (node (ref "J49") (pin "19") (pinfunction "19_19") (pintype "bidirectional"))
      (node (ref "Q79") (pin "G") (pinfunction "G_G") (pintype "passive"))
    )
    (net (code "18") (name "DASH_EN_0") (class "Default")
      (node (ref "J2") (pin "2") (pinfunction "2_2") (pintype "passive"))
      (node (ref "Q2") (pin "G") (pinfunction "G_G") (pintype "passive"))
    )
    (net (code "19") (name "DASH_EN_1") (class "Default")
      (node (ref "J5") (pin "2") (pinfunction "2_2") (pintype "passive"))
      (node (ref "Q7") (pin "G") (pinfunction "G_G") (pintype "passive"))
    )
    (net (code "20") (name "DASH_EN_2") (class "Default")
      (node (ref "J8") (pin "2") (pinfunction "2_2") (pintype "passive"))
      (node (ref "Q12") (pin "G") (pinfunction "G_G") (pintype "passive"))
    )
    (net (code "21") (name "DASH_EN_3") (class "Default")
      (node (ref "J11") (pin "2") (pinfunction "2_2") (pintype "passive"))
      (node (ref "Q17") (pin "G") (pinfunction "G_G") (pintype "passive"))
    )
    (net (code "22") (name "DASH_EN_4") (class "Default")
      (node (ref "J14") (pin "2") (pinfunction "2_2") (pintype "passive"))
      (node (ref "Q22") (pin "G") (pinfunction "G_G") (pintype "passive"))
    )
    (net (code "23") (name "DASH_EN_5") (class "Default")
      (node (ref "J17") (pin "2") (pinfunction "2_2") (pintype "passive"))
      (node (ref "Q27") (pin "G") (pinfunction "G_G") (pintype "passive"))
    )
    (net (code "24") (name "DASH_EN_6") (class "Default")
      (node (ref "J20") (pin "2") (pinfunction "2_2") (pintype "passive"))
      (node (ref "Q32") (pin "G") (pinfunction "G_G") (pintype "passive"))
    )
    (net (code "25") (name "DASH_EN_7") (class "Default")
      (node (ref "J23") (pin "2") (pinfunction "2_2") (pintype "passive"))
      (node (ref "Q37") (pin "G") (pinfunction "G_G") (pintype "passive"))
    )
    (net (code "26") (name "DASH_EN_8") (class "Default")
      (node (ref "J26") (pin "2") (pinfunction "2_2") (pintype "passive"))
      (node (ref "Q42") (pin "G") (pinfunction "G_G") (pintype "passive"))
    )
    (net (code "27") (name "DASH_EN_9") (class "Default")
      (node (ref "J29") (pin "2") (pinfunction "2_2") (pintype "passive"))
      (node (ref "Q47") (pin "G") (pinfunction "G_G") (pintype "passive"))
    )
    (net (code "28") (name "DASH_EN_10") (class "Default")
      (node (ref "J32") (pin "2") (pinfunction "2_2") (pintype "passive"))
      (node (ref "Q52") (pin "G") (pinfunction "G_G") (pintype "passive"))
    )
    (net (code "29") (name "DASH_EN_11") (class "Default")
      (node (ref "J35") (pin "2") (pinfunction "2_2") (pintype "passive"))
      (node (ref "Q57") (pin "G") (pinfunction "G_G") (pintype "passive"))
    )
    (net (code "30") (name "DASH_EN_12") (class "Default")
      (node (ref "J38") (pin "2") (pinfunction "2_2") (pintype "passive"))
      (node (ref "Q62") (pin "G") (pinfunction "G_G") (pintype "passive"))
    )
    (net (code "31") (name "DASH_EN_13") (class "Default")
      (node (ref "J41") (pin "2") (pinfunction "2_2") (pintype "passive"))
      (node (ref "Q67") (pin "G") (pinfunction "G_G") (pintype "passive"))
    )
    (net (code "32") (name "DASH_EN_14") (class "Default")
      (node (ref "J44") (pin "2") (pinfunction "2_2") (pintype "passive"))
      (node (ref "Q72") (pin "G") (pinfunction "G_G") (pintype "passive"))
    )
    (net (code "33") (name "DASH_EN_15") (class "Default")
      (node (ref "J47") (pin "2") (pinfunction "2_2") (pintype "passive"))
      (node (ref "Q77") (pin "G") (pinfunction "G_G") (pintype "passive"))
    )
    (net (code "34") (name "EN_0") (class "Default")
      (node (ref "J1") (pin "1") (pinfunction "1_1") (pintype "passive"))
      (node (ref "Q5") (pin "D") (pinfunction "D_D") (pintype "passive"))
      (node (ref "R5") (pin "1") (pinfunction "1_1") (pintype "passive"))
    )
    (net (code "35") (name "EN_1") (class "Default")
      (node (ref "J4") (pin "1") (pinfunction "1_1") (pintype "passive"))
      (node (ref "Q10") (pin "D") (pinfunction "D_D") (pintype "passive"))
      (node (ref "R11") (pin "1") (pinfunction "1_1") (pintype "passive"))
    )
    (net (code "36") (name "EN_2") (class "Default")
      (node (ref "J7") (pin "1") (pinfunction "1_1") (pintype "passive"))
      (node (ref "Q15") (pin "D") (pinfunction "D_D") (pintype "passive"))
      (node (ref "R17") (pin "1") (pinfunction "1_1") (pintype "passive"))
    )
    (net (code "37") (name "EN_3") (class "Default")
      (node (ref "J10") (pin "1") (pinfunction "1_1") (pintype "passive"))
      (node (ref "Q20") (pin "D") (pinfunction "D_D") (pintype "passive"))
      (node (ref "R23") (pin "1") (pinfunction "1_1") (pintype "passive"))
    )
    (net (code "38") (name "EN_4") (class "Default")
      (node (ref "J13") (pin "1") (pinfunction "1_1") (pintype "passive"))
      (node (ref "Q25") (pin "D") (pinfunction "D_D") (pintype "passive"))
      (node (ref "R29") (pin "1") (pinfunction "1_1") (pintype "passive"))
    )
    (net (code "39") (name "EN_5") (class "Default")
      (node (ref "J16") (pin "1") (pinfunction "1_1") (pintype "passive"))
      (node (ref "Q30") (pin "D") (pinfunction "D_D") (pintype "passive"))
      (node (ref "R35") (pin "1") (pinfunction "1_1") (pintype "passive"))
    )
    (net (code "40") (name "EN_6") (class "Default")
      (node (ref "J19") (pin "1") (pinfunction "1_1") (pintype "passive"))
      (node (ref "Q35") (pin "D") (pinfunction "D_D") (pintype "passive"))
      (node (ref "R41") (pin "1") (pinfunction "1_1") (pintype "passive"))
    )
    (net (code "41") (name "EN_7") (class "Default")
      (node (ref "J22") (pin "1") (pinfunction "1_1") (pintype "passive"))
      (node (ref "Q40") (pin "D") (pinfunction "D_D") (pintype "passive"))
      (node (ref "R47") (pin "1") (pinfunction "1_1") (pintype "passive"))
    )
    (net (code "42") (name "EN_8") (class "Default")
      (node (ref "J25") (pin "1") (pinfunction "1_1") (pintype "passive"))
      (node (ref "Q45") (pin "D") (pinfunction "D_D") (pintype "passive"))
      (node (ref "R53") (pin "1") (pinfunction "1_1") (pintype "passive"))
    )
    (net (code "43") (name "EN_9") (class "Default")
      (node (ref "J28") (pin "1") (pinfunction "1_1") (pintype "passive"))
      (node (ref "Q50") (pin "D") (pinfunction "D_D") (pintype "passive"))
      (node (ref "R59") (pin "1") (pinfunction "1_1") (pintype "passive"))
    )
    (net (code "44") (name "EN_10") (class "Default")
      (node (ref "J31") (pin "1") (pinfunction "1_1") (pintype "passive"))
      (node (ref "Q55") (pin "D") (pinfunction "D_D") (pintype "passive"))
      (node (ref "R65") (pin "1") (pinfunction "1_1") (pintype "passive"))
    )
    (net (code "45") (name "EN_11") (class "Default")
      (node (ref "J34") (pin "1") (pinfunction "1_1") (pintype "passive"))
      (node (ref "Q60") (pin "D") (pinfunction "D_D") (pintype "passive"))
      (node (ref "R71") (pin "1") (pinfunction "1_1") (pintype "passive"))
    )
    (net (code "46") (name "EN_12") (class "Default")
      (node (ref "J37") (pin "1") (pinfunction "1_1") (pintype "passive"))
      (node (ref "Q65") (pin "D") (pinfunction "D_D") (pintype "passive"))
      (node (ref "R77") (pin "1") (pinfunction "1_1") (pintype "passive"))
    )
    (net (code "47") (name "EN_13") (class "Default")
      (node (ref "J40") (pin "1") (pinfunction "1_1") (pintype "passive"))
      (node (ref "Q70") (pin "D") (pinfunction "D_D") (pintype "passive"))
      (node (ref "R83") (pin "1") (pinfunction "1_1") (pintype "passive"))
    )
    (net (code "48") (name "EN_14") (class "Default")
      (node (ref "J43") (pin "1") (pinfunction "1_1") (pintype "passive"))
      (node (ref "Q75") (pin "D") (pinfunction "D_D") (pintype "passive"))
      (node (ref "R89") (pin "1") (pinfunction "1_1") (pintype "passive"))
    )
    (net (code "49") (name "EN_15") (class "Default")
      (node (ref "J46") (pin "1") (pinfunction "1_1") (pintype "passive"))
      (node (ref "Q80") (pin "D") (pinfunction "D_D") (pintype "passive"))
      (node (ref "R95") (pin "1") (pinfunction "1_1") (pintype "passive"))
    )
    (net (code "50") (name "EN_N_0") (class "Default")
      (node (ref "J2") (pin "1") (pinfunction "1_1") (pintype "passive"))
      (node (ref "J3") (pin "1") (pinfunction "1_1") (pintype "passive"))
      (node (ref "Q4") (pin "D") (pinfunction "D_D") (pintype "passive"))
      (node (ref "Q5") (pin "G") (pinfunction "G_G") (pintype "passive"))
      (node (ref "R4") (pin "1") (pinfunction "1_1") (pintype "passive"))
    )
    (net (code "51") (name "EN_N_1") (class "Default")
      (node (ref "J5") (pin "1") (pinfunction "1_1") (pintype "passive"))
      (node (ref "J6") (pin "1") (pinfunction "1_1") (pintype "passive"))
      (node (ref "Q10") (pin "G") (pinfunction "G_G") (pintype "passive"))
      (node (ref "Q9") (pin "D") (pinfunction "D_D") (pintype "passive"))
      (node (ref "R10") (pin "1") (pinfunction "1_1") (pintype "passive"))
    )
    (net (code "52") (name "EN_N_2") (class "Default")
      (node (ref "J8") (pin "1") (pinfunction "1_1") (pintype "passive"))
      (node (ref "J9") (pin "1") (pinfunction "1_1") (pintype "passive"))
      (node (ref "Q14") (pin "D") (pinfunction "D_D") (pintype "passive"))
      (node (ref "Q15") (pin "G") (pinfunction "G_G") (pintype "passive"))
      (node (ref "R16") (pin "1") (pinfunction "1_1") (pintype "passive"))
    )
    (net (code "53") (name "EN_N_3") (class "Default")
      (node (ref "J11") (pin "1") (pinfunction "1_1") (pintype "passive"))
      (node (ref "J12") (pin "1") (pinfunction "1_1") (pintype "passive"))
      (node (ref "Q19") (pin "D") (pinfunction "D_D") (pintype "passive"))
      (node (ref "Q20") (pin "G") (pinfunction "G_G") (pintype "passive"))
      (node (ref "R22") (pin "1") (pinfunction "1_1") (pintype "passive"))
    )
    (net (code "54") (name "EN_N_4") (class "Default")
      (node (ref "J14") (pin "1") (pinfunction "1_1") (pintype "passive"))
      (node (ref "J15") (pin "1") (pinfunction "1_1") (pintype "passive"))
      (node (ref "Q24") (pin "D") (pinfunction "D_D") (pintype "passive"))
      (node (ref "Q25") (pin "G") (pinfunction "G_G") (pintype "passive"))
      (node (ref "R28") (pin "1") (pinfunction "1_1") (pintype "passive"))
    )
    (net (code "55") (name "EN_N_5") (class "Default")
      (node (ref "J17") (pin "1") (pinfunction "1_1") (pintype "passive"))
      (node (ref "J18") (pin "1") (pinfunction "1_1") (pintype "passive"))
      (node (ref "Q29") (pin "D") (pinfunction "D_D") (pintype "passive"))
      (node (ref "Q30") (pin "G") (pinfunction "G_G") (pintype "passive"))
      (node (ref "R34") (pin "1") (pinfunction "1_1") (pintype "passive"))
    )
    (net (code "56") (name "EN_N_6") (class "Default")
      (node (ref "J20") (pin "1") (pinfunction "1_1") (pintype "passive"))
      (node (ref "J21") (pin "1") (pinfunction "1_1") (pintype "passive"))
      (node (ref "Q34") (pin "D") (pinfunction "D_D") (pintype "passive"))
      (node (ref "Q35") (pin "G") (pinfunction "G_G") (pintype "passive"))
      (node (ref "R40") (pin "1") (pinfunction "1_1") (pintype "passive"))
    )
    (net (code "57") (name "EN_N_7") (class "Default")
      (node (ref "J23") (pin "1") (pinfunction "1_1") (pintype "passive"))
      (node (ref "J24") (pin "1") (pinfunction "1_1") (pintype "passive"))
      (node (ref "Q39") (pin "D") (pinfunction "D_D") (pintype "passive"))
      (node (ref "Q40") (pin "G") (pinfunction "G_G") (pintype "passive"))
      (node (ref "R46") (pin "1") (pinfunction "1_1") (pintype "passive"))
    )
    (net (code "58") (name "EN_N_8") (class "Default")
      (node (ref "J26") (pin "1") (pinfunction "1_1") (pintype "passive"))
      (node (ref "J27") (pin "1") (pinfunction "1_1") (pintype "passive"))
      (node (ref "Q44") (pin "D") (pinfunction "D_D") (pintype "passive"))
      (node (ref "Q45") (pin "G") (pinfunction "G_G") (pintype "passive"))
      (node (ref "R52") (pin "1") (pinfunction "1_1") (pintype "passive"))
    )
    (net (code "59") (name "EN_N_9") (class "Default")
      (node (ref "J29") (pin "1") (pinfunction "1_1") (pintype "passive"))
      (node (ref "J30") (pin "1") (pinfunction "1_1") (pintype "passive"))
      (node (ref "Q49") (pin "D") (pinfunction "D_D") (pintype "passive"))
      (node (ref "Q50") (pin "G") (pinfunction "G_G") (pintype "passive"))
      (node (ref "R58") (pin "1") (pinfunction "1_1") (pintype "passive"))
    )
    (net (code "60") (name "EN_N_10") (class "Default")
      (node (ref "J32") (pin "1") (pinfunction "1_1") (pintype "passive"))
      (node (ref "J33") (pin "1") (pinfunction "1_1") (pintype "passive"))
      (node (ref "Q54") (pin "D") (pinfunction "D_D") (pintype "passive"))
      (node (ref "Q55") (pin "G") (pinfunction "G_G") (pintype "passive"))
      (node (ref "R64") (pin "1") (pinfunction "1_1") (pintype "passive"))
    )
    (net (code "61") (name "EN_N_11") (class "Default")
      (node (ref "J35") (pin "1") (pinfunction "1_1") (pintype "passive"))
      (node (ref "J36") (pin "1") (pinfunction "1_1") (pintype "passive"))
      (node (ref "Q59") (pin "D") (pinfunction "D_D") (pintype "passive"))
      (node (ref "Q60") (pin "G") (pinfunction "G_G") (pintype "passive"))
      (node (ref "R70") (pin "1") (pinfunction "1_1") (pintype "passive"))
    )
    (net (code "62") (name "EN_N_12") (class "Default")
      (node (ref "J38") (pin "1") (pinfunction "1_1") (pintype "passive"))
      (node (ref "J39") (pin "1") (pinfunction "1_1") (pintype "passive"))
      (node (ref "Q64") (pin "D") (pinfunction "D_D") (pintype "passive"))
      (node (ref "Q65") (pin "G") (pinfunction "G_G") (pintype "passive"))
      (node (ref "R76") (pin "1") (pinfunction "1_1") (pintype "passive"))
    )
    (net (code "63") (name "EN_N_13") (class "Default")
      (node (ref "J41") (pin "1") (pinfunction "1_1") (pintype "passive"))
      (node (ref "J42") (pin "1") (pinfunction "1_1") (pintype "passive"))
      (node (ref "Q69") (pin "D") (pinfunction "D_D") (pintype "passive"))
      (node (ref "Q70") (pin "G") (pinfunction "G_G") (pintype "passive"))
      (node (ref "R82") (pin "1") (pinfunction "1_1") (pintype "passive"))
    )
    (net (code "64") (name "EN_N_14") (class "Default")
      (node (ref "J44") (pin "1") (pinfunction "1_1") (pintype "passive"))
      (node (ref "J45") (pin "1") (pinfunction "1_1") (pintype "passive"))
      (node (ref "Q74") (pin "D") (pinfunction "D_D") (pintype "passive"))
      (node (ref "Q75") (pin "G") (pinfunction "G_G") (pintype "passive"))
      (node (ref "R88") (pin "1") (pinfunction "1_1") (pintype "passive"))
    )
    (net (code "65") (name "EN_N_15") (class "Default")
      (node (ref "J47") (pin "1") (pinfunction "1_1") (pintype "passive"))
      (node (ref "J48") (pin "1") (pinfunction "1_1") (pintype "passive"))
      (node (ref "Q79") (pin "D") (pinfunction "D_D") (pintype "passive"))
      (node (ref "Q80") (pin "G") (pinfunction "G_G") (pintype "passive"))
      (node (ref "R94") (pin "1") (pinfunction "1_1") (pintype "passive"))
    )
    (net (code "66") (name "GND") (class "Default")
      (node (ref "C1") (pin "K") (pinfunction "K_K") (pintype "passive"))
      (node (ref "C2") (pin "K") (pinfunction "K_K") (pintype "passive"))
      (node (ref "C3") (pin "2") (pinfunction "2_2") (pintype "passive"))
      (node (ref "C4") (pin "2") (pinfunction "2_2") (pintype "passive"))
      (node (ref "J11") (pin "3") (pinfunction "3_3") (pintype "passive"))
      (node (ref "J12") (pin "3") (pinfunction "3_3") (pintype "passive"))
      (node (ref "J14") (pin "3") (pinfunction "3_3") (pintype "passive"))
      (node (ref "J15") (pin "3") (pinfunction "3_3") (pintype "passive"))
      (node (ref "J17") (pin "3") (pinfunction "3_3") (pintype "passive"))
      (node (ref "J18") (pin "3") (pinfunction "3_3") (pintype "passive"))
      (node (ref "J2") (pin "3") (pinfunction "3_3") (pintype "passive"))
      (node (ref "J20") (pin "3") (pinfunction "3_3") (pintype "passive"))
      (node (ref "J21") (pin "3") (pinfunction "3_3") (pintype "passive"))
      (node (ref "J23") (pin "3") (pinfunction "3_3") (pintype "passive"))
      (node (ref "J24") (pin "3") (pinfunction "3_3") (pintype "passive"))
      (node (ref "J26") (pin "3") (pinfunction "3_3") (pintype "passive"))
      (node (ref "J27") (pin "3") (pinfunction "3_3") (pintype "passive"))
      (node (ref "J29") (pin "3") (pinfunction "3_3") (pintype "passive"))
      (node (ref "J3") (pin "3") (pinfunction "3_3") (pintype "passive"))
      (node (ref "J30") (pin "3") (pinfunction "3_3") (pintype "passive"))
      (node (ref "J32") (pin "3") (pinfunction "3_3") (pintype "passive"))
      (node (ref "J33") (pin "3") (pinfunction "3_3") (pintype "passive"))
      (node (ref "J35") (pin "3") (pinfunction "3_3") (pintype "passive"))
      (node (ref "J36") (pin "3") (pinfunction "3_3") (pintype "passive"))
      (node (ref "J38") (pin "3") (pinfunction "3_3") (pintype "passive"))
      (node (ref "J39") (pin "3") (pinfunction "3_3") (pintype "passive"))
      (node (ref "J41") (pin "3") (pinfunction "3_3") (pintype "passive"))
      (node (ref "J42") (pin "3") (pinfunction "3_3") (pintype "passive"))
      (node (ref "J44") (pin "3") (pinfunction "3_3") (pintype "passive"))
      (node (ref "J45") (pin "3") (pinfunction "3_3") (pintype "passive"))
      (node (ref "J47") (pin "3") (pinfunction "3_3") (pintype "passive"))
      (node (ref "J48") (pin "3") (pinfunction "3_3") (pintype "passive"))
      (node (ref "J49") (pin "1") (pinfunction "1_1") (pintype "bidirectional"))
      (node (ref "J49") (pin "10") (pinfunction "10_10") (pintype "bidirectional"))
      (node (ref "J49") (pin "11") (pinfunction "11_11") (pintype "bidirectional"))
      (node (ref "J49") (pin "20") (pinfunction "20_20") (pintype "bidirectional"))
      (node (ref "J49") (pin "21") (pinfunction "21_21") (pintype "bidirectional"))
      (node (ref "J49") (pin "30") (pinfunction "30_30") (pintype "bidirectional"))
      (node (ref "J5") (pin "3") (pinfunction "3_3") (pintype "passive"))
      (node (ref "J6") (pin "3") (pinfunction "3_3") (pintype "passive"))
      (node (ref "J8") (pin "3") (pinfunction "3_3") (pintype "passive"))
      (node (ref "J9") (pin "3") (pinfunction "3_3") (pintype "passive"))
      (node (ref "PP1") (pin "1") (pinfunction "P$1_1") (pintype "bidirectional"))
      (node (ref "Q1") (pin "S") (pinfunction "S_S") (pintype "passive"))
      (node (ref "Q10") (pin "S") (pinfunction "S_S") (pintype "passive"))
      (node (ref "Q11") (pin "S") (pinfunction "S_S") (pintype "passive"))
      (node (ref "Q12") (pin "S") (pinfunction "S_S") (pintype "passive"))
      (node (ref "Q13") (pin "S") (pinfunction "S_S") (pintype "passive"))
      (node (ref "Q14") (pin "S") (pinfunction "S_S") (pintype "passive"))
      (node (ref "Q15") (pin "S") (pinfunction "S_S") (pintype "passive"))
      (node (ref "Q16") (pin "S") (pinfunction "S_S") (pintype "passive"))
      (node (ref "Q17") (pin "S") (pinfunction "S_S") (pintype "passive"))
      (node (ref "Q18") (pin "S") (pinfunction "S_S") (pintype "passive"))
      (node (ref "Q19") (pin "S") (pinfunction "S_S") (pintype "passive"))
      (node (ref "Q2") (pin "S") (pinfunction "S_S") (pintype "passive"))
      (node (ref "Q20") (pin "S") (pinfunction "S_S") (pintype "passive"))
      (node (ref "Q21") (pin "S") (pinfunction "S_S") (pintype "passive"))
      (node (ref "Q22") (pin "S") (pinfunction "S_S") (pintype "passive"))
      (node (ref "Q23") (pin "S") (pinfunction "S_S") (pintype "passive"))
      (node (ref "Q24") (pin "S") (pinfunction "S_S") (pintype "passive"))
      (node (ref "Q25") (pin "S") (pinfunction "S_S") (pintype "passive"))
      (node (ref "Q26") (pin "S") (pinfunction "S_S") (pintype "passive"))
      (node (ref "Q27") (pin "S") (pinfunction "S_S") (pintype "passive"))
      (node (ref "Q28") (pin "S") (pinfunction "S_S") (pintype "passive"))
      (node (ref "Q29") (pin "S") (pinfunction "S_S") (pintype "passive"))
      (node (ref "Q3") (pin "S") (pinfunction "S_S") (pintype "passive"))
      (node (ref "Q30") (pin "S") (pinfunction "S_S") (pintype "passive"))
      (node (ref "Q31") (pin "S") (pinfunction "S_S") (pintype "passive"))
      (node (ref "Q32") (pin "S") (pinfunction "S_S") (pintype "passive"))
      (node (ref "Q33") (pin "S") (pinfunction "S_S") (pintype "passive"))
      (node (ref "Q34") (pin "S") (pinfunction "S_S") (pintype "passive"))
      (node (ref "Q35") (pin "S") (pinfunction "S_S") (pintype "passive"))
      (node (ref "Q36") (pin "S") (pinfunction "S_S") (pintype "passive"))
      (node (ref "Q37") (pin "S") (pinfunction "S_S") (pintype "passive"))
      (node (ref "Q38") (pin "S") (pinfunction "S_S") (pintype "passive"))
      (node (ref "Q39") (pin "S") (pinfunction "S_S") (pintype "passive"))
      (node (ref "Q4") (pin "S") (pinfunction "S_S") (pintype "passive"))
      (node (ref "Q40") (pin "S") (pinfunction "S_S") (pintype "passive"))
      (node (ref "Q41") (pin "S") (pinfunction "S_S") (pintype "passive"))
      (node (ref "Q42") (pin "S") (pinfunction "S_S") (pintype "passive"))
      (node (ref "Q43") (pin "S") (pinfunction "S_S") (pintype "passive"))
      (node (ref "Q44") (pin "S") (pinfunction "S_S") (pintype "passive"))
      (node (ref "Q45") (pin "S") (pinfunction "S_S") (pintype "passive"))
      (node (ref "Q46") (pin "S") (pinfunction "S_S") (pintype "passive"))
      (node (ref "Q47") (pin "S") (pinfunction "S_S") (pintype "passive"))
      (node (ref "Q48") (pin "S") (pinfunction "S_S") (pintype "passive"))
      (node (ref "Q49") (pin "S") (pinfunction "S_S") (pintype "passive"))
      (node (ref "Q5") (pin "S") (pinfunction "S_S") (pintype "passive"))
      (node (ref "Q50") (pin "S") (pinfunction "S_S") (pintype "passive"))
      (node (ref "Q51") (pin "S") (pinfunction "S_S") (pintype "passive"))
      (node (ref "Q52") (pin "S") (pinfunction "S_S") (pintype "passive"))
      (node (ref "Q53") (pin "S") (pinfunction "S_S") (pintype "passive"))
      (node (ref "Q54") (pin "S") (pinfunction "S_S") (pintype "passive"))
      (node (ref "Q55") (pin "S") (pinfunction "S_S") (pintype "passive"))
      (node (ref "Q56") (pin "S") (pinfunction "S_S") (pintype "passive"))
      (node (ref "Q57") (pin "S") (pinfunction "S_S") (pintype "passive"))
      (node (ref "Q58") (pin "S") (pinfunction "S_S") (pintype "passive"))
      (node (ref "Q59") (pin "S") (pinfunction "S_S") (pintype "passive"))
      (node (ref "Q6") (pin "S") (pinfunction "S_S") (pintype "passive"))
      (node (ref "Q60") (pin "S") (pinfunction "S_S") (pintype "passive"))
      (node (ref "Q61") (pin "S") (pinfunction "S_S") (pintype "passive"))
      (node (ref "Q62") (pin "S") (pinfunction "S_S") (pintype "passive"))
      (node (ref "Q63") (pin "S") (pinfunction "S_S") (pintype "passive"))
      (node (ref "Q64") (pin "S") (pinfunction "S_S") (pintype "passive"))
      (node (ref "Q65") (pin "S") (pinfunction "S_S") (pintype "passive"))
      (node (ref "Q66") (pin "S") (pinfunction "S_S") (pintype "passive"))
      (node (ref "Q67") (pin "S") (pinfunction "S_S") (pintype "passive"))
      (node (ref "Q68") (pin "S") (pinfunction "S_S") (pintype "passive"))
      (node (ref "Q69") (pin "S") (pinfunction "S_S") (pintype "passive"))
      (node (ref "Q7") (pin "S") (pinfunction "S_S") (pintype "passive"))
      (node (ref "Q70") (pin "S") (pinfunction "S_S") (pintype "passive"))
      (node (ref "Q71") (pin "S") (pinfunction "S_S") (pintype "passive"))
      (node (ref "Q72") (pin "S") (pinfunction "S_S") (pintype "passive"))
      (node (ref "Q73") (pin "S") (pinfunction "S_S") (pintype "passive"))
      (node (ref "Q74") (pin "S") (pinfunction "S_S") (pintype "passive"))
      (node (ref "Q75") (pin "S") (pinfunction "S_S") (pintype "passive"))
      (node (ref "Q76") (pin "S") (pinfunction "S_S") (pintype "passive"))
      (node (ref "Q77") (pin "S") (pinfunction "S_S") (pintype "passive"))
      (node (ref "Q78") (pin "S") (pinfunction "S_S") (pintype "passive"))
      (node (ref "Q79") (pin "S") (pinfunction "S_S") (pintype "passive"))
      (node (ref "Q8") (pin "S") (pinfunction "S_S") (pintype "passive"))
      (node (ref "Q80") (pin "S") (pinfunction "S_S") (pintype "passive"))
      (node (ref "Q9") (pin "S") (pinfunction "S_S") (pintype "passive"))
    )
    (net (code "67") (name "LED_SUPPLY") (class "Default")
      (node (ref "C2") (pin "A") (pinfunction "A_A") (pintype "passive"))
      (node (ref "C4") (pin "1") (pinfunction "1_1") (pintype "passive"))
      (node (ref "D1") (pin "3") (pinfunction "COM_3") (pintype "passive"))
      (node (ref "D1") (pin "8") (pinfunction "COM_8") (pintype "passive"))
      (node (ref "D10") (pin "3") (pinfunction "COM_3") (pintype "passive"))
      (node (ref "D10") (pin "8") (pinfunction "COM_8") (pintype "passive"))
      (node (ref "D11") (pin "3") (pinfunction "COM_3") (pintype "passive"))
      (node (ref "D11") (pin "8") (pinfunction "COM_8") (pintype "passive"))
      (node (ref "D12") (pin "3") (pinfunction "COM_3") (pintype "passive"))
      (node (ref "D12") (pin "8") (pinfunction "COM_8") (pintype "passive"))
      (node (ref "D13") (pin "3") (pinfunction "COM_3") (pintype "passive"))
      (node (ref "D13") (pin "8") (pinfunction "COM_8") (pintype "passive"))
      (node (ref "D14") (pin "3") (pinfunction "COM_3") (pintype "passive"))
      (node (ref "D14") (pin "8") (pinfunction "COM_8") (pintype "passive"))
      (node (ref "D15") (pin "3") (pinfunction "COM_3") (pintype "passive"))
      (node (ref "D15") (pin "8") (pinfunction "COM_8") (pintype "passive"))
      (node (ref "D16") (pin "3") (pinfunction "COM_3") (pintype "passive"))
      (node (ref "D16") (pin "8") (pinfunction "COM_8") (pintype "passive"))
      (node (ref "D2") (pin "3") (pinfunction "COM_3") (pintype "passive"))
      (node (ref "D2") (pin "8") (pinfunction "COM_8") (pintype "passive"))
      (node (ref "D3") (pin "3") (pinfunction "COM_3") (pintype "passive"))
      (node (ref "D3") (pin "8") (pinfunction "COM_8") (pintype "passive"))
      (node (ref "D4") (pin "3") (pinfunction "COM_3") (pintype "passive"))
      (node (ref "D4") (pin "8") (pinfunction "COM_8") (pintype "passive"))
      (node (ref "D5") (pin "3") (pinfunction "COM_3") (pintype "passive"))
      (node (ref "D5") (pin "8") (pinfunction "COM_8") (pintype "passive"))
      (node (ref "D6") (pin "3") (pinfunction "COM_3") (pintype "passive"))
      (node (ref "D6") (pin "8") (pinfunction "COM_8") (pintype "passive"))
      (node (ref "D7") (pin "3") (pinfunction "COM_3") (pintype "passive"))
      (node (ref "D7") (pin "8") (pinfunction "COM_8") (pintype "passive"))
      (node (ref "D8") (pin "3") (pinfunction "COM_3") (pintype "passive"))
      (node (ref "D8") (pin "8") (pinfunction "COM_8") (pintype "passive"))
      (node (ref "D9") (pin "3") (pinfunction "COM_3") (pintype "passive"))
      (node (ref "D9") (pin "8") (pinfunction "COM_8") (pintype "passive"))
      (node (ref "PP3") (pin "1") (pinfunction "P$1_1") (pintype "bidirectional"))
    )
    (net (code "68") (name "Net-(D1-A)") (class "Default")
      (node (ref "D1") (pin "7") (pinfunction "A_7") (pintype "passive"))
      (node (ref "R160") (pin "1") (pinfunction "1_1") (pintype "passive"))
    )
    (net (code "69") (name "Net-(D1-B)") (class "Default")
      (node (ref "D1") (pin "6") (pinfunction "B_6") (pintype "passive"))
      (node (ref "R159") (pin "1") (pinfunction "1_1") (pintype "passive"))
    )
    (net (code "70") (name "Net-(D1-C)") (class "Default")
      (node (ref "D1") (pin "4") (pinfunction "C_4") (pintype "passive"))
      (node (ref "R158") (pin "1") (pinfunction "1_1") (pintype "passive"))
    )
    (net (code "71") (name "Net-(D1-D)") (class "Default")
      (node (ref "D1") (pin "2") (pinfunction "D_2") (pintype "passive"))
      (node (ref "R157") (pin "1") (pinfunction "1_1") (pintype "passive"))
    )
    (net (code "72") (name "Net-(D1-E)") (class "Default")
      (node (ref "D1") (pin "1") (pinfunction "E_1") (pintype "passive"))
      (node (ref "R1") (pin "1") (pinfunction "1_1") (pintype "passive"))
    )
    (net (code "73") (name "Net-(D1-F)") (class "Default")
      (node (ref "D1") (pin "9") (pinfunction "F_9") (pintype "passive"))
      (node (ref "R2") (pin "1") (pinfunction "1_1") (pintype "passive"))
    )
    (net (code "74") (name "Net-(D1-G)") (class "Default")
      (node (ref "D1") (pin "10") (pinfunction "G_10") (pintype "passive"))
      (node (ref "R3") (pin "1") (pinfunction "1_1") (pintype "passive"))
    )
    (net (code "75") (name "Net-(D2-A)") (class "Default")
      (node (ref "D2") (pin "7") (pinfunction "A_7") (pintype "passive"))
      (node (ref "R156") (pin "1") (pinfunction "1_1") (pintype "passive"))
    )
    (net (code "76") (name "Net-(D2-B)") (class "Default")
      (node (ref "D2") (pin "6") (pinfunction "B_6") (pintype "passive"))
      (node (ref "R155") (pin "1") (pinfunction "1_1") (pintype "passive"))
    )
    (net (code "77") (name "Net-(D2-C)") (class "Default")
      (node (ref "D2") (pin "4") (pinfunction "C_4") (pintype "passive"))
      (node (ref "R154") (pin "1") (pinfunction "1_1") (pintype "passive"))
    )
    (net (code "78") (name "Net-(D2-D)") (class "Default")
      (node (ref "D2") (pin "2") (pinfunction "D_2") (pintype "passive"))
      (node (ref "R153") (pin "1") (pinfunction "1_1") (pintype "passive"))
    )
    (net (code "79") (name "Net-(D2-E)") (class "Default")
      (node (ref "D2") (pin "1") (pinfunction "E_1") (pintype "passive"))
      (node (ref "R7") (pin "1") (pinfunction "1_1") (pintype "passive"))
    )
    (net (code "80") (name "Net-(D2-F)") (class "Default")
      (node (ref "D2") (pin "9") (pinfunction "F_9") (pintype "passive"))
      (node (ref "R8") (pin "1") (pinfunction "1_1") (pintype "passive"))
    )
    (net (code "81") (name "Net-(D2-G)") (class "Default")
      (node (ref "D2") (pin "10") (pinfunction "G_10") (pintype "passive"))
      (node (ref "R9") (pin "1") (pinfunction "1_1") (pintype "passive"))
    )
    (net (code "82") (name "Net-(D3-A)") (class "Default")
      (node (ref "D3") (pin "7") (pinfunction "A_7") (pintype "passive"))
      (node (ref "R151") (pin "1") (pinfunction "1_1") (pintype "passive"))
    )
    (net (code "83") (name "Net-(D3-B)") (class "Default")
      (node (ref "D3") (pin "6") (pinfunction "B_6") (pintype "passive"))
      (node (ref "R152") (pin "1") (pinfunction "1_1") (pintype "passive"))
    )
    (net (code "84") (name "Net-(D3-C)") (class "Default")
      (node (ref "D3") (pin "4") (pinfunction "C_4") (pintype "passive"))
      (node (ref "R150") (pin "1") (pinfunction "1_1") (pintype "passive"))
    )
    (net (code "85") (name "Net-(D3-D)") (class "Default")
      (node (ref "D3") (pin "2") (pinfunction "D_2") (pintype "passive"))
      (node (ref "R149") (pin "1") (pinfunction "1_1") (pintype "passive"))
    )
    (net (code "86") (name "Net-(D3-E)") (class "Default")
      (node (ref "D3") (pin "1") (pinfunction "E_1") (pintype "passive"))
      (node (ref "R13") (pin "1") (pinfunction "1_1") (pintype "passive"))
    )
    (net (code "87") (name "Net-(D3-F)") (class "Default")
      (node (ref "D3") (pin "9") (pinfunction "F_9") (pintype "passive"))
      (node (ref "R14") (pin "1") (pinfunction "1_1") (pintype "passive"))
    )
    (net (code "88") (name "Net-(D3-G)") (class "Default")
      (node (ref "D3") (pin "10") (pinfunction "G_10") (pintype "passive"))
      (node (ref "R15") (pin "1") (pinfunction "1_1") (pintype "passive"))
    )
    (net (code "89") (name "Net-(D4-A)") (class "Default")
      (node (ref "D4") (pin "7") (pinfunction "A_7") (pintype "passive"))
      (node (ref "R148") (pin "1") (pinfunction "1_1") (pintype "passive"))
    )
    (net (code "90") (name "Net-(D4-B)") (class "Default")
      (node (ref "D4") (pin "6") (pinfunction "B_6") (pintype "passive"))
      (node (ref "R147") (pin "1") (pinfunction "1_1") (pintype "passive"))
    )
    (net (code "91") (name "Net-(D4-C)") (class "Default")
      (node (ref "D4") (pin "4") (pinfunction "C_4") (pintype "passive"))
      (node (ref "R145") (pin "1") (pinfunction "1_1") (pintype "passive"))
    )
    (net (code "92") (name "Net-(D4-D)") (class "Default")
      (node (ref "D4") (pin "2") (pinfunction "D_2") (pintype "passive"))
      (node (ref "R146") (pin "1") (pinfunction "1_1") (pintype "passive"))
    )
    (net (code "93") (name "Net-(D4-E)") (class "Default")
      (node (ref "D4") (pin "1") (pinfunction "E_1") (pintype "passive"))
      (node (ref "R19") (pin "1") (pinfunction "1_1") (pintype "passive"))
    )
    (net (code "94") (name "Net-(D4-F)") (class "Default")
      (node (ref "D4") (pin "9") (pinfunction "F_9") (pintype "passive"))
      (node (ref "R20") (pin "1") (pinfunction "1_1") (pintype "passive"))
    )
    (net (code "95") (name "Net-(D4-G)") (class "Default")
      (node (ref "D4") (pin "10") (pinfunction "G_10") (pintype "passive"))
      (node (ref "R21") (pin "1") (pinfunction "1_1") (pintype "passive"))
    )
    (net (code "96") (name "Net-(D5-A)") (class "Default")
      (node (ref "D5") (pin "7") (pinfunction "A_7") (pintype "passive"))
      (node (ref "R144") (pin "1") (pinfunction "1_1") (pintype "passive"))
    )
    (net (code "97") (name "Net-(D5-B)") (class "Default")
      (node (ref "D5") (pin "6") (pinfunction "B_6") (pintype "passive"))
      (node (ref "R143") (pin "1") (pinfunction "1_1") (pintype "passive"))
    )
    (net (code "98") (name "Net-(D5-C)") (class "Default")
      (node (ref "D5") (pin "4") (pinfunction "C_4") (pintype "passive"))
      (node (ref "R142") (pin "1") (pinfunction "1_1") (pintype "passive"))
    )
    (net (code "99") (name "Net-(D5-D)") (class "Default")
      (node (ref "D5") (pin "2") (pinfunction "D_2") (pintype "passive"))
      (node (ref "R141") (pin "1") (pinfunction "1_1") (pintype "passive"))
    )
    (net (code "100") (name "Net-(D5-E)") (class "Default")
      (node (ref "D5") (pin "1") (pinfunction "E_1") (pintype "passive"))
      (node (ref "R25") (pin "1") (pinfunction "1_1") (pintype "passive"))
    )
    (net (code "101") (name "Net-(D5-F)") (class "Default")
      (node (ref "D5") (pin "9") (pinfunction "F_9") (pintype "passive"))
      (node (ref "R26") (pin "1") (pinfunction "1_1") (pintype "passive"))
    )
    (net (code "102") (name "Net-(D5-G)") (class "Default")
      (node (ref "D5") (pin "10") (pinfunction "G_10") (pintype "passive"))
      (node (ref "R27") (pin "1") (pinfunction "1_1") (pintype "passive"))
    )
    (net (code "103") (name "Net-(D6-A)") (class "Default")
      (node (ref "D6") (pin "7") (pinfunction "A_7") (pintype "passive"))
      (node (ref "R140") (pin "1") (pinfunction "1_1") (pintype "passive"))
    )
    (net (code "104") (name "Net-(D6-B)") (class "Default")
      (node (ref "D6") (pin "6") (pinfunction "B_6") (pintype "passive"))
      (node (ref "R139") (pin "1") (pinfunction "1_1") (pintype "passive"))
    )
    (net (code "105") (name "Net-(D6-C)") (class "Default")
      (node (ref "D6") (pin "4") (pinfunction "C_4") (pintype "passive"))
      (node (ref "R138") (pin "1") (pinfunction "1_1") (pintype "passive"))
    )
    (net (code "106") (name "Net-(D6-D)") (class "Default")
      (node (ref "D6") (pin "2") (pinfunction "D_2") (pintype "passive"))
      (node (ref "R137") (pin "1") (pinfunction "1_1") (pintype "passive"))
    )
    (net (code "107") (name "Net-(D6-E)") (class "Default")
      (node (ref "D6") (pin "1") (pinfunction "E_1") (pintype "passive"))
      (node (ref "R31") (pin "1") (pinfunction "1_1") (pintype "passive"))
    )
    (net (code "108") (name "Net-(D6-F)") (class "Default")
      (node (ref "D6") (pin "9") (pinfunction "F_9") (pintype "passive"))
      (node (ref "R32") (pin "1") (pinfunction "1_1") (pintype "passive"))
    )
    (net (code "109") (name "Net-(D6-G)") (class "Default")
      (node (ref "D6") (pin "10") (pinfunction "G_10") (pintype "passive"))
      (node (ref "R33") (pin "1") (pinfunction "1_1") (pintype "passive"))
    )
    (net (code "110") (name "Net-(D7-A)") (class "Default")
      (node (ref "D7") (pin "7") (pinfunction "A_7") (pintype "passive"))
      (node (ref "R132") (pin "1") (pinfunction "1_1") (pintype "passive"))
    )
    (net (code "111") (name "Net-(D7-B)") (class "Default")
      (node (ref "D7") (pin "6") (pinfunction "B_6") (pintype "passive"))
      (node (ref "R131") (pin "1") (pinfunction "1_1") (pintype "passive"))
    )
    (net (code "112") (name "Net-(D7-C)") (class "Default")
      (node (ref "D7") (pin "4") (pinfunction "C_4") (pintype "passive"))
      (node (ref "R130") (pin "1") (pinfunction "1_1") (pintype "passive"))
    )
    (net (code "113") (name "Net-(D7-D)") (class "Default")
      (node (ref "D7") (pin "2") (pinfunction "D_2") (pintype "passive"))
      (node (ref "R129") (pin "1") (pinfunction "1_1") (pintype "passive"))
    )
    (net (code "114") (name "Net-(D7-E)") (class "Default")
      (node (ref "D7") (pin "1") (pinfunction "E_1") (pintype "passive"))
      (node (ref "R37") (pin "1") (pinfunction "1_1") (pintype "passive"))
    )
    (net (code "115") (name "Net-(D7-F)") (class "Default")
      (node (ref "D7") (pin "9") (pinfunction "F_9") (pintype "passive"))
      (node (ref "R38") (pin "1") (pinfunction "1_1") (pintype "passive"))
    )
    (net (code "116") (name "Net-(D7-G)") (class "Default")
      (node (ref "D7") (pin "10") (pinfunction "G_10") (pintype "passive"))
      (node (ref "R39") (pin "1") (pinfunction "1_1") (pintype "passive"))
    )
    (net (code "117") (name "Net-(D8-A)") (class "Default")
      (node (ref "D8") (pin "7") (pinfunction "A_7") (pintype "passive"))
      (node (ref "R136") (pin "1") (pinfunction "1_1") (pintype "passive"))
    )
    (net (code "118") (name "Net-(D8-B)") (class "Default")
      (node (ref "D8") (pin "6") (pinfunction "B_6") (pintype "passive"))
      (node (ref "R134") (pin "1") (pinfunction "1_1") (pintype "passive"))
    )
    (net (code "119") (name "Net-(D8-C)") (class "Default")
      (node (ref "D8") (pin "4") (pinfunction "C_4") (pintype "passive"))
      (node (ref "R135") (pin "1") (pinfunction "1_1") (pintype "passive"))
    )
    (net (code "120") (name "Net-(D8-D)") (class "Default")
      (node (ref "D8") (pin "2") (pinfunction "D_2") (pintype "passive"))
      (node (ref "R133") (pin "1") (pinfunction "1_1") (pintype "passive"))
    )
    (net (code "121") (name "Net-(D8-E)") (class "Default")
      (node (ref "D8") (pin "1") (pinfunction "E_1") (pintype "passive"))
      (node (ref "R43") (pin "1") (pinfunction "1_1") (pintype "passive"))
    )
    (net (code "122") (name "Net-(D8-F)") (class "Default")
      (node (ref "D8") (pin "9") (pinfunction "F_9") (pintype "passive"))
      (node (ref "R44") (pin "1") (pinfunction "1_1") (pintype "passive"))
    )
    (net (code "123") (name "Net-(D8-G)") (class "Default")
      (node (ref "D8") (pin "10") (pinfunction "G_10") (pintype "passive"))
      (node (ref "R45") (pin "1") (pinfunction "1_1") (pintype "passive"))
    )
    (net (code "124") (name "Net-(D9-A)") (class "Default")
      (node (ref "D9") (pin "7") (pinfunction "A_7") (pintype "passive"))
      (node (ref "R128") (pin "1") (pinfunction "1_1") (pintype "passive"))
    )
    (net (code "125") (name "Net-(D9-B)") (class "Default")
      (node (ref "D9") (pin "6") (pinfunction "B_6") (pintype "passive"))
      (node (ref "R127") (pin "1") (pinfunction "1_1") (pintype "passive"))
    )
    (net (code "126") (name "Net-(D9-C)") (class "Default")
      (node (ref "D9") (pin "4") (pinfunction "C_4") (pintype "passive"))
      (node (ref "R126") (pin "1") (pinfunction "1_1") (pintype "passive"))
    )
    (net (code "127") (name "Net-(D9-D)") (class "Default")
      (node (ref "D9") (pin "2") (pinfunction "D_2") (pintype "passive"))
      (node (ref "R125") (pin "1") (pinfunction "1_1") (pintype "passive"))
    )
    (net (code "128") (name "Net-(D9-E)") (class "Default")
      (node (ref "D9") (pin "1") (pinfunction "E_1") (pintype "passive"))
      (node (ref "R49") (pin "1") (pinfunction "1_1") (pintype "passive"))
    )
    (net (code "129") (name "Net-(D9-F)") (class "Default")
      (node (ref "D9") (pin "9") (pinfunction "F_9") (pintype "passive"))
      (node (ref "R50") (pin "1") (pinfunction "1_1") (pintype "passive"))
    )
    (net (code "130") (name "Net-(D9-G)") (class "Default")
      (node (ref "D9") (pin "10") (pinfunction "G_10") (pintype "passive"))
      (node (ref "R51") (pin "1") (pinfunction "1_1") (pintype "passive"))
    )
    (net (code "131") (name "Net-(D10-A)") (class "Default")
      (node (ref "D10") (pin "7") (pinfunction "A_7") (pintype "passive"))
      (node (ref "R124") (pin "1") (pinfunction "1_1") (pintype "passive"))
    )
    (net (code "132") (name "Net-(D10-B)") (class "Default")
      (node (ref "D10") (pin "6") (pinfunction "B_6") (pintype "passive"))
      (node (ref "R123") (pin "1") (pinfunction "1_1") (pintype "passive"))
    )
    (net (code "133") (name "Net-(D10-C)") (class "Default")
      (node (ref "D10") (pin "4") (pinfunction "C_4") (pintype "passive"))
      (node (ref "R122") (pin "1") (pinfunction "1_1") (pintype "passive"))
    )
    (net (code "134") (name "Net-(D10-D)") (class "Default")
      (node (ref "D10") (pin "2") (pinfunction "D_2") (pintype "passive"))
      (node (ref "R121") (pin "1") (pinfunction "1_1") (pintype "passive"))
    )
    (net (code "135") (name "Net-(D10-E)") (class "Default")
      (node (ref "D10") (pin "1") (pinfunction "E_1") (pintype "passive"))
      (node (ref "R55") (pin "1") (pinfunction "1_1") (pintype "passive"))
    )
    (net (code "136") (name "Net-(D10-F)") (class "Default")
      (node (ref "D10") (pin "9") (pinfunction "F_9") (pintype "passive"))
      (node (ref "R56") (pin "1") (pinfunction "1_1") (pintype "passive"))
    )
    (net (code "137") (name "Net-(D10-G)") (class "Default")
      (node (ref "D10") (pin "10") (pinfunction "G_10") (pintype "passive"))
      (node (ref "R57") (pin "1") (pinfunction "1_1") (pintype "passive"))
    )
    (net (code "138") (name "Net-(D11-A)") (class "Default")
      (node (ref "D11") (pin "7") (pinfunction "A_7") (pintype "passive"))
      (node (ref "R120") (pin "1") (pinfunction "1_1") (pintype "passive"))
    )
    (net (code "139") (name "Net-(D11-B)") (class "Default")
      (node (ref "D11") (pin "6") (pinfunction "B_6") (pintype "passive"))
      (node (ref "R119") (pin "1") (pinfunction "1_1") (pintype "passive"))
    )
    (net (code "140") (name "Net-(D11-C)") (class "Default")
      (node (ref "D11") (pin "4") (pinfunction "C_4") (pintype "passive"))
      (node (ref "R118") (pin "1") (pinfunction "1_1") (pintype "passive"))
    )
    (net (code "141") (name "Net-(D11-D)") (class "Default")
      (node (ref "D11") (pin "2") (pinfunction "D_2") (pintype "passive"))
      (node (ref "R117") (pin "1") (pinfunction "1_1") (pintype "passive"))
    )
    (net (code "142") (name "Net-(D11-E)") (class "Default")
      (node (ref "D11") (pin "1") (pinfunction "E_1") (pintype "passive"))
      (node (ref "R61") (pin "1") (pinfunction "1_1") (pintype "passive"))
    )
    (net (code "143") (name "Net-(D11-F)") (class "Default")
      (node (ref "D11") (pin "9") (pinfunction "F_9") (pintype "passive"))
      (node (ref "R62") (pin "1") (pinfunction "1_1") (pintype "passive"))
    )
    (net (code "144") (name "Net-(D11-G)") (class "Default")
      (node (ref "D11") (pin "10") (pinfunction "G_10") (pintype "passive"))
      (node (ref "R63") (pin "1") (pinfunction "1_1") (pintype "passive"))
    )
    (net (code "145") (name "Net-(D12-A)") (class "Default")
      (node (ref "D12") (pin "7") (pinfunction "A_7") (pintype "passive"))
      (node (ref "R116") (pin "1") (pinfunction "1_1") (pintype "passive"))
    )
    (net (code "146") (name "Net-(D12-B)") (class "Default")
      (node (ref "D12") (pin "6") (pinfunction "B_6") (pintype "passive"))
      (node (ref "R115") (pin "1") (pinfunction "1_1") (pintype "passive"))
    )
    (net (code "147") (name "Net-(D12-C)") (class "Default")
      (node (ref "D12") (pin "4") (pinfunction "C_4") (pintype "passive"))
      (node (ref "R114") (pin "1") (pinfunction "1_1") (pintype "passive"))
    )
    (net (code "148") (name "Net-(D12-D)") (class "Default")
      (node (ref "D12") (pin "2") (pinfunction "D_2") (pintype "passive"))
      (node (ref "R113") (pin "1") (pinfunction "1_1") (pintype "passive"))
    )
    (net (code "149") (name "Net-(D12-E)") (class "Default")
      (node (ref "D12") (pin "1") (pinfunction "E_1") (pintype "passive"))
      (node (ref "R67") (pin "1") (pinfunction "1_1") (pintype "passive"))
    )
    (net (code "150") (name "Net-(D12-F)") (class "Default")
      (node (ref "D12") (pin "9") (pinfunction "F_9") (pintype "passive"))
      (node (ref "R68") (pin "1") (pinfunction "1_1") (pintype "passive"))
    )
    (net (code "151") (name "Net-(D12-G)") (class "Default")
      (node (ref "D12") (pin "10") (pinfunction "G_10") (pintype "passive"))
      (node (ref "R69") (pin "1") (pinfunction "1_1") (pintype "passive"))
    )
    (net (code "152") (name "Net-(D13-A)") (class "Default")
      (node (ref "D13") (pin "7") (pinfunction "A_7") (pintype "passive"))
      (node (ref "R104") (pin "1") (pinfunction "1_1") (pintype "passive"))
    )
    (net (code "153") (name "Net-(D13-B)") (class "Default")
      (node (ref "D13") (pin "6") (pinfunction "B_6") (pintype "passive"))
      (node (ref "R103") (pin "1") (pinfunction "1_1") (pintype "passive"))
    )
    (net (code "154") (name "Net-(D13-C)") (class "Default")
      (node (ref "D13") (pin "4") (pinfunction "C_4") (pintype "passive"))
      (node (ref "R102") (pin "1") (pinfunction "1_1") (pintype "passive"))
    )
    (net (code "155") (name "Net-(D13-D)") (class "Default")
      (node (ref "D13") (pin "2") (pinfunction "D_2") (pintype "passive"))
      (node (ref "R101") (pin "1") (pinfunction "1_1") (pintype "passive"))
    )
    (net (code "156") (name "Net-(D13-E)") (class "Default")
      (node (ref "D13") (pin "1") (pinfunction "E_1") (pintype "passive"))
      (node (ref "R73") (pin "1") (pinfunction "1_1") (pintype "passive"))
    )
    (net (code "157") (name "Net-(D13-F)") (class "Default")
      (node (ref "D13") (pin "9") (pinfunction "F_9") (pintype "passive"))
      (node (ref "R74") (pin "1") (pinfunction "1_1") (pintype "passive"))
    )
    (net (code "158") (name "Net-(D13-G)") (class "Default")
      (node (ref "D13") (pin "10") (pinfunction "G_10") (pintype "passive"))
      (node (ref "R75") (pin "1") (pinfunction "1_1") (pintype "passive"))
    )
    (net (code "159") (name "Net-(D14-A)") (class "Default")
      (node (ref "D14") (pin "7") (pinfunction "A_7") (pintype "passive"))
      (node (ref "R100") (pin "1") (pinfunction "1_1") (pintype "passive"))
    )
    (net (code "160") (name "Net-(D14-B)") (class "Default")
      (node (ref "D14") (pin "6") (pinfunction "B_6") (pintype "passive"))
      (node (ref "R99") (pin "1") (pinfunction "1_1") (pintype "passive"))
    )
    (net (code "161") (name "Net-(D14-C)") (class "Default")
      (node (ref "D14") (pin "4") (pinfunction "C_4") (pintype "passive"))
      (node (ref "R98") (pin "1") (pinfunction "1_1") (pintype "passive"))
    )
    (net (code "162") (name "Net-(D14-D)") (class "Default")
      (node (ref "D14") (pin "2") (pinfunction "D_2") (pintype "passive"))
      (node (ref "R97") (pin "1") (pinfunction "1_1") (pintype "passive"))
    )
    (net (code "163") (name "Net-(D14-E)") (class "Default")
      (node (ref "D14") (pin "1") (pinfunction "E_1") (pintype "passive"))
      (node (ref "R79") (pin "1") (pinfunction "1_1") (pintype "passive"))
    )
    (net (code "164") (name "Net-(D14-F)") (class "Default")
      (node (ref "D14") (pin "9") (pinfunction "F_9") (pintype "passive"))
      (node (ref "R80") (pin "1") (pinfunction "1_1") (pintype "passive"))
    )
    (net (code "165") (name "Net-(D14-G)") (class "Default")
      (node (ref "D14") (pin "10") (pinfunction "G_10") (pintype "passive"))
      (node (ref "R81") (pin "1") (pinfunction "1_1") (pintype "passive"))
    )
    (net (code "166") (name "Net-(D15-A)") (class "Default")
      (node (ref "D15") (pin "7") (pinfunction "A_7") (pintype "passive"))
      (node (ref "R108") (pin "1") (pinfunction "1_1") (pintype "passive"))
    )
    (net (code "167") (name "Net-(D15-B)") (class "Default")
      (node (ref "D15") (pin "6") (pinfunction "B_6") (pintype "passive"))
      (node (ref "R107") (pin "1") (pinfunction "1_1") (pintype "passive"))
    )
    (net (code "168") (name "Net-(D15-C)") (class "Default")
      (node (ref "D15") (pin "4") (pinfunction "C_4") (pintype "passive"))
      (node (ref "R106") (pin "1") (pinfunction "1_1") (pintype "passive"))
    )
    (net (code "169") (name "Net-(D15-D)") (class "Default")
      (node (ref "D15") (pin "2") (pinfunction "D_2") (pintype "passive"))
      (node (ref "R105") (pin "1") (pinfunction "1_1") (pintype "passive"))
    )
    (net (code "170") (name "Net-(D15-E)") (class "Default")
      (node (ref "D15") (pin "1") (pinfunction "E_1") (pintype "passive"))
      (node (ref "R85") (pin "1") (pinfunction "1_1") (pintype "passive"))
    )
    (net (code "171") (name "Net-(D15-F)") (class "Default")
      (node (ref "D15") (pin "9") (pinfunction "F_9") (pintype "passive"))
      (node (ref "R86") (pin "1") (pinfunction "1_1") (pintype "passive"))
    )
    (net (code "172") (name "Net-(D15-G)") (class "Default")
      (node (ref "D15") (pin "10") (pinfunction "G_10") (pintype "passive"))
      (node (ref "R87") (pin "1") (pinfunction "1_1") (pintype "passive"))
    )
    (net (code "173") (name "Net-(D16-A)") (class "Default")
      (node (ref "D16") (pin "7") (pinfunction "A_7") (pintype "passive"))
      (node (ref "R112") (pin "1") (pinfunction "1_1") (pintype "passive"))
    )
    (net (code "174") (name "Net-(D16-B)") (class "Default")
      (node (ref "D16") (pin "6") (pinfunction "B_6") (pintype "passive"))
      (node (ref "R111") (pin "1") (pinfunction "1_1") (pintype "passive"))
    )
    (net (code "175") (name "Net-(D16-C)") (class "Default")
      (node (ref "D16") (pin "4") (pinfunction "C_4") (pintype "passive"))
      (node (ref "R110") (pin "1") (pinfunction "1_1") (pintype "passive"))
    )
    (net (code "176") (name "Net-(D16-D)") (class "Default")
      (node (ref "D16") (pin "2") (pinfunction "D_2") (pintype "passive"))
      (node (ref "R109") (pin "1") (pinfunction "1_1") (pintype "passive"))
    )
    (net (code "177") (name "Net-(D16-E)") (class "Default")
      (node (ref "D16") (pin "1") (pinfunction "E_1") (pintype "passive"))
      (node (ref "R91") (pin "1") (pinfunction "1_1") (pintype "passive"))
    )
    (net (code "178") (name "Net-(D16-F)") (class "Default")
      (node (ref "D16") (pin "9") (pinfunction "F_9") (pintype "passive"))
      (node (ref "R92") (pin "1") (pinfunction "1_1") (pintype "passive"))
    )
    (net (code "179") (name "Net-(D16-G)") (class "Default")
      (node (ref "D16") (pin "10") (pinfunction "G_10") (pintype "passive"))
      (node (ref "R93") (pin "1") (pinfunction "1_1") (pintype "passive"))
    )
    (net (code "180") (name "Net-(J1-Pad3)") (class "Default")
      (node (ref "J1") (pin "3") (pinfunction "3_3") (pintype "passive"))
      (node (ref "R6") (pin "1") (pinfunction "1_1") (pintype "passive"))
    )
    (net (code "181") (name "Net-(J4-Pad3)") (class "Default")
      (node (ref "J4") (pin "3") (pinfunction "3_3") (pintype "passive"))
      (node (ref "R12") (pin "1") (pinfunction "1_1") (pintype "passive"))
    )
    (net (code "182") (name "Net-(J7-Pad3)") (class "Default")
      (node (ref "J7") (pin "3") (pinfunction "3_3") (pintype "passive"))
      (node (ref "R18") (pin "1") (pinfunction "1_1") (pintype "passive"))
    )
    (net (code "183") (name "Net-(J10-Pad3)") (class "Default")
      (node (ref "J10") (pin "3") (pinfunction "3_3") (pintype "passive"))
      (node (ref "R24") (pin "1") (pinfunction "1_1") (pintype "passive"))
    )
    (net (code "184") (name "Net-(J13-Pad3)") (class "Default")
      (node (ref "J13") (pin "3") (pinfunction "3_3") (pintype "passive"))
      (node (ref "R30") (pin "1") (pinfunction "1_1") (pintype "passive"))
    )
    (net (code "185") (name "Net-(J16-Pad3)") (class "Default")
      (node (ref "J16") (pin "3") (pinfunction "3_3") (pintype "passive"))
      (node (ref "R36") (pin "1") (pinfunction "1_1") (pintype "passive"))
    )
    (net (code "186") (name "Net-(J19-Pad3)") (class "Default")
      (node (ref "J19") (pin "3") (pinfunction "3_3") (pintype "passive"))
      (node (ref "R42") (pin "1") (pinfunction "1_1") (pintype "passive"))
    )
    (net (code "187") (name "Net-(J22-Pad3)") (class "Default")
      (node (ref "J22") (pin "3") (pinfunction "3_3") (pintype "passive"))
      (node (ref "R48") (pin "1") (pinfunction "1_1") (pintype "passive"))
    )
    (net (code "188") (name "Net-(J25-Pad3)") (class "Default")
      (node (ref "J25") (pin "3") (pinfunction "3_3") (pintype "passive"))
      (node (ref "R54") (pin "1") (pinfunction "1_1") (pintype "passive"))
    )
    (net (code "189") (name "Net-(J28-Pad3)") (class "Default")
      (node (ref "J28") (pin "3") (pinfunction "3_3") (pintype "passive"))
      (node (ref "R60") (pin "1") (pinfunction "1_1") (pintype "passive"))
    )
    (net (code "190") (name "Net-(J31-Pad3)") (class "Default")
      (node (ref "J31") (pin "3") (pinfunction "3_3") (pintype "passive"))
      (node (ref "R66") (pin "1") (pinfunction "1_1") (pintype "passive"))
    )
    (net (code "191") (name "Net-(J34-Pad3)") (class "Default")
      (node (ref "J34") (pin "3") (pinfunction "3_3") (pintype "passive"))
      (node (ref "R72") (pin "1") (pinfunction "1_1") (pintype "passive"))
    )
    (net (code "192") (name "Net-(J37-Pad3)") (class "Default")
      (node (ref "J37") (pin "3") (pinfunction "3_3") (pintype "passive"))
      (node (ref "R78") (pin "1") (pinfunction "1_1") (pintype "passive"))
    )
    (net (code "193") (name "Net-(J40-Pad3)") (class "Default")
      (node (ref "J40") (pin "3") (pinfunction "3_3") (pintype "passive"))
      (node (ref "R84") (pin "1") (pinfunction "1_1") (pintype "passive"))
    )
    (net (code "194") (name "Net-(J43-Pad3)") (class "Default")
      (node (ref "J43") (pin "3") (pinfunction "3_3") (pintype "passive"))
      (node (ref "R90") (pin "1") (pinfunction "1_1") (pintype "passive"))
    )
    (net (code "195") (name "Net-(J46-Pad3)") (class "Default")
      (node (ref "J46") (pin "3") (pinfunction "3_3") (pintype "passive"))
      (node (ref "R96") (pin "1") (pinfunction "1_1") (pintype "passive"))
    )
    (net (code "196") (name "Net-(Q1-PadD)") (class "Default")
      (node (ref "Q1") (pin "D") (pinfunction "D_D") (pintype "passive"))
      (node (ref "R158") (pin "2") (pinfunction "2_2") (pintype "passive"))
      (node (ref "R159") (pin "2") (pinfunction "2_2") (pintype "passive"))
    )
    (net (code "197") (name "Net-(Q2-PadD)") (class "Default")
      (node (ref "Q2") (pin "D") (pinfunction "D_D") (pintype "passive"))
      (node (ref "R3") (pin "2") (pinfunction "2_2") (pintype "passive"))
    )
    (net (code "198") (name "Net-(Q3-PadD)") (class "Default")
      (node (ref "Q3") (pin "D") (pinfunction "D_D") (pintype "passive"))
      (node (ref "R1") (pin "2") (pinfunction "2_2") (pintype "passive"))
      (node (ref "R157") (pin "2") (pinfunction "2_2") (pintype "passive"))
      (node (ref "R160") (pin "2") (pinfunction "2_2") (pintype "passive"))
      (node (ref "R2") (pin "2") (pinfunction "2_2") (pintype "passive"))
    )
    (net (code "199") (name "Net-(Q6-PadD)") (class "Default")
      (node (ref "Q6") (pin "D") (pinfunction "D_D") (pintype "passive"))
      (node (ref "R154") (pin "2") (pinfunction "2_2") (pintype "passive"))
      (node (ref "R155") (pin "2") (pinfunction "2_2") (pintype "passive"))
    )
    (net (code "200") (name "Net-(Q7-PadD)") (class "Default")
      (node (ref "Q7") (pin "D") (pinfunction "D_D") (pintype "passive"))
      (node (ref "R9") (pin "2") (pinfunction "2_2") (pintype "passive"))
    )
    (net (code "201") (name "Net-(Q8-PadD)") (class "Default")
      (node (ref "Q8") (pin "D") (pinfunction "D_D") (pintype "passive"))
      (node (ref "R153") (pin "2") (pinfunction "2_2") (pintype "passive"))
      (node (ref "R156") (pin "2") (pinfunction "2_2") (pintype "passive"))
      (node (ref "R7") (pin "2") (pinfunction "2_2") (pintype "passive"))
      (node (ref "R8") (pin "2") (pinfunction "2_2") (pintype "passive"))
    )
    (net (code "202") (name "Net-(Q11-PadD)") (class "Default")
      (node (ref "Q11") (pin "D") (pinfunction "D_D") (pintype "passive"))
      (node (ref "R150") (pin "2") (pinfunction "2_2") (pintype "passive"))
      (node (ref "R152") (pin "2") (pinfunction "2_2") (pintype "passive"))
    )
    (net (code "203") (name "Net-(Q12-PadD)") (class "Default")
      (node (ref "Q12") (pin "D") (pinfunction "D_D") (pintype "passive"))
      (node (ref "R15") (pin "2") (pinfunction "2_2") (pintype "passive"))
    )
    (net (code "204") (name "Net-(Q13-PadD)") (class "Default")
      (node (ref "Q13") (pin "D") (pinfunction "D_D") (pintype "passive"))
      (node (ref "R13") (pin "2") (pinfunction "2_2") (pintype "passive"))
      (node (ref "R14") (pin "2") (pinfunction "2_2") (pintype "passive"))
      (node (ref "R149") (pin "2") (pinfunction "2_2") (pintype "passive"))
      (node (ref "R151") (pin "2") (pinfunction "2_2") (pintype "passive"))
    )
    (net (code "205") (name "Net-(Q16-PadD)") (class "Default")
      (node (ref "Q16") (pin "D") (pinfunction "D_D") (pintype "passive"))
      (node (ref "R145") (pin "2") (pinfunction "2_2") (pintype "passive"))
      (node (ref "R147") (pin "2") (pinfunction "2_2") (pintype "passive"))
    )
    (net (code "206") (name "Net-(Q17-PadD)") (class "Default")
      (node (ref "Q17") (pin "D") (pinfunction "D_D") (pintype "passive"))
      (node (ref "R21") (pin "2") (pinfunction "2_2") (pintype "passive"))
    )
    (net (code "207") (name "Net-(Q18-PadD)") (class "Default")
      (node (ref "Q18") (pin "D") (pinfunction "D_D") (pintype "passive"))
      (node (ref "R146") (pin "2") (pinfunction "2_2") (pintype "passive"))
      (node (ref "R148") (pin "2") (pinfunction "2_2") (pintype "passive"))
      (node (ref "R19") (pin "2") (pinfunction "2_2") (pintype "passive"))
      (node (ref "R20") (pin "2") (pinfunction "2_2") (pintype "passive"))
    )
    (net (code "208") (name "Net-(Q21-PadD)") (class "Default")
      (node (ref "Q21") (pin "D") (pinfunction "D_D") (pintype "passive"))
      (node (ref "R142") (pin "2") (pinfunction "2_2") (pintype "passive"))
      (node (ref "R143") (pin "2") (pinfunction "2_2") (pintype "passive"))
    )
    (net (code "209") (name "Net-(Q22-PadD)") (class "Default")
      (node (ref "Q22") (pin "D") (pinfunction "D_D") (pintype "passive"))
      (node (ref "R27") (pin "2") (pinfunction "2_2") (pintype "passive"))
    )
    (net (code "210") (name "Net-(Q23-PadD)") (class "Default")
      (node (ref "Q23") (pin "D") (pinfunction "D_D") (pintype "passive"))
      (node (ref "R141") (pin "2") (pinfunction "2_2") (pintype "passive"))
      (node (ref "R144") (pin "2") (pinfunction "2_2") (pintype "passive"))
      (node (ref "R25") (pin "2") (pinfunction "2_2") (pintype "passive"))
      (node (ref "R26") (pin "2") (pinfunction "2_2") (pintype "passive"))
    )
    (net (code "211") (name "Net-(Q26-PadD)") (class "Default")
      (node (ref "Q26") (pin "D") (pinfunction "D_D") (pintype "passive"))
      (node (ref "R138") (pin "2") (pinfunction "2_2") (pintype "passive"))
      (node (ref "R139") (pin "2") (pinfunction "2_2") (pintype "passive"))
    )
    (net (code "212") (name "Net-(Q27-PadD)") (class "Default")
      (node (ref "Q27") (pin "D") (pinfunction "D_D") (pintype "passive"))
      (node (ref "R33") (pin "2") (pinfunction "2_2") (pintype "passive"))
    )
    (net (code "213") (name "Net-(Q28-PadD)") (class "Default")
      (node (ref "Q28") (pin "D") (pinfunction "D_D") (pintype "passive"))
      (node (ref "R137") (pin "2") (pinfunction "2_2") (pintype "passive"))
      (node (ref "R140") (pin "2") (pinfunction "2_2") (pintype "passive"))
      (node (ref "R31") (pin "2") (pinfunction "2_2") (pintype "passive"))
      (node (ref "R32") (pin "2") (pinfunction "2_2") (pintype "passive"))
    )
    (net (code "214") (name "Net-(Q31-PadD)") (class "Default")
      (node (ref "Q31") (pin "D") (pinfunction "D_D") (pintype "passive"))
      (node (ref "R130") (pin "2") (pinfunction "2_2") (pintype "passive"))
      (node (ref "R131") (pin "2") (pinfunction "2_2") (pintype "passive"))
    )
    (net (code "215") (name "Net-(Q32-PadD)") (class "Default")
      (node (ref "Q32") (pin "D") (pinfunction "D_D") (pintype "passive"))
      (node (ref "R39") (pin "2") (pinfunction "2_2") (pintype "passive"))
    )
    (net (code "216") (name "Net-(Q33-PadD)") (class "Default")
      (node (ref "Q33") (pin "D") (pinfunction "D_D") (pintype "passive"))
      (node (ref "R129") (pin "2") (pinfunction "2_2") (pintype "passive"))
      (node (ref "R132") (pin "2") (pinfunction "2_2") (pintype "passive"))
      (node (ref "R37") (pin "2") (pinfunction "2_2") (pintype "passive"))
      (node (ref "R38") (pin "2") (pinfunction "2_2") (pintype "passive"))
    )
    (net (code "217") (name "Net-(Q36-PadD)") (class "Default")
      (node (ref "Q36") (pin "D") (pinfunction "D_D") (pintype "passive"))
      (node (ref "R134") (pin "2") (pinfunction "2_2") (pintype "passive"))
      (node (ref "R135") (pin "2") (pinfunction "2_2") (pintype "passive"))
    )
    (net (code "218") (name "Net-(Q37-PadD)") (class "Default")
      (node (ref "Q37") (pin "D") (pinfunction "D_D") (pintype "passive"))
      (node (ref "R45") (pin "2") (pinfunction "2_2") (pintype "passive"))
    )
    (net (code "219") (name "Net-(Q38-PadD)") (class "Default")
      (node (ref "Q38") (pin "D") (pinfunction "D_D") (pintype "passive"))
      (node (ref "R133") (pin "2") (pinfunction "2_2") (pintype "passive"))
      (node (ref "R136") (pin "2") (pinfunction "2_2") (pintype "passive"))
      (node (ref "R43") (pin "2") (pinfunction "2_2") (pintype "passive"))
      (node (ref "R44") (pin "2") (pinfunction "2_2") (pintype "passive"))
    )
    (net (code "220") (name "Net-(Q41-PadD)") (class "Default")
      (node (ref "Q41") (pin "D") (pinfunction "D_D") (pintype "passive"))
      (node (ref "R126") (pin "2") (pinfunction "2_2") (pintype "passive"))
      (node (ref "R127") (pin "2") (pinfunction "2_2") (pintype "passive"))
    )
    (net (code "221") (name "Net-(Q42-PadD)") (class "Default")
      (node (ref "Q42") (pin "D") (pinfunction "D_D") (pintype "passive"))
      (node (ref "R51") (pin "2") (pinfunction "2_2") (pintype "passive"))
    )
    (net (code "222") (name "Net-(Q43-PadD)") (class "Default")
      (node (ref "Q43") (pin "D") (pinfunction "D_D") (pintype "passive"))
      (node (ref "R125") (pin "2") (pinfunction "2_2") (pintype "passive"))
      (node (ref "R128") (pin "2") (pinfunction "2_2") (pintype "passive"))
      (node (ref "R49") (pin "2") (pinfunction "2_2") (pintype "passive"))
      (node (ref "R50") (pin "2") (pinfunction "2_2") (pintype "passive"))
    )
    (net (code "223") (name "Net-(Q46-PadD)") (class "Default")
      (node (ref "Q46") (pin "D") (pinfunction "D_D") (pintype "passive"))
      (node (ref "R122") (pin "2") (pinfunction "2_2") (pintype "passive"))
      (node (ref "R123") (pin "2") (pinfunction "2_2") (pintype "passive"))
    )
    (net (code "224") (name "Net-(Q47-PadD)") (class "Default")
      (node (ref "Q47") (pin "D") (pinfunction "D_D") (pintype "passive"))
      (node (ref "R57") (pin "2") (pinfunction "2_2") (pintype "passive"))
    )
    (net (code "225") (name "Net-(Q48-PadD)") (class "Default")
      (node (ref "Q48") (pin "D") (pinfunction "D_D") (pintype "passive"))
      (node (ref "R121") (pin "2") (pinfunction "2_2") (pintype "passive"))
      (node (ref "R124") (pin "2") (pinfunction "2_2") (pintype "passive"))
      (node (ref "R55") (pin "2") (pinfunction "2_2") (pintype "passive"))
      (node (ref "R56") (pin "2") (pinfunction "2_2") (pintype "passive"))
    )
    (net (code "226") (name "Net-(Q51-PadD)") (class "Default")
      (node (ref "Q51") (pin "D") (pinfunction "D_D") (pintype "passive"))
      (node (ref "R118") (pin "2") (pinfunction "2_2") (pintype "passive"))
      (node (ref "R119") (pin "2") (pinfunction "2_2") (pintype "passive"))
    )
    (net (code "227") (name "Net-(Q52-PadD)") (class "Default")
      (node (ref "Q52") (pin "D") (pinfunction "D_D") (pintype "passive"))
      (node (ref "R63") (pin "2") (pinfunction "2_2") (pintype "passive"))
    )
    (net (code "228") (name "Net-(Q53-PadD)") (class "Default")
      (node (ref "Q53") (pin "D") (pinfunction "D_D") (pintype "passive"))
      (node (ref "R117") (pin "2") (pinfunction "2_2") (pintype "passive"))
      (node (ref "R120") (pin "2") (pinfunction "2_2") (pintype "passive"))
      (node (ref "R61") (pin "2") (pinfunction "2_2") (pintype "passive"))
      (node (ref "R62") (pin "2") (pinfunction "2_2") (pintype "passive"))
    )
    (net (code "229") (name "Net-(Q56-PadD)") (class "Default")
      (node (ref "Q56") (pin "D") (pinfunction "D_D") (pintype "passive"))
      (node (ref "R114") (pin "2") (pinfunction "2_2") (pintype "passive"))
      (node (ref "R115") (pin "2") (pinfunction "2_2") (pintype "passive"))
    )
    (net (code "230") (name "Net-(Q57-PadD)") (class "Default")
      (node (ref "Q57") (pin "D") (pinfunction "D_D") (pintype "passive"))
      (node (ref "R69") (pin "2") (pinfunction "2_2") (pintype "passive"))
    )
    (net (code "231") (name "Net-(Q58-PadD)") (class "Default")
      (node (ref "Q58") (pin "D") (pinfunction "D_D") (pintype "passive"))
      (node (ref "R113") (pin "2") (pinfunction "2_2") (pintype "passive"))
      (node (ref "R116") (pin "2") (pinfunction "2_2") (pintype "passive"))
      (node (ref "R67") (pin "2") (pinfunction "2_2") (pintype "passive"))
      (node (ref "R68") (pin "2") (pinfunction "2_2") (pintype "passive"))
    )
    (net (code "232") (name "Net-(Q61-PadD)") (class "Default")
      (node (ref "Q61") (pin "D") (pinfunction "D_D") (pintype "passive"))
      (node (ref "R102") (pin "2") (pinfunction "2_2") (pintype "passive"))
      (node (ref "R103") (pin "2") (pinfunction "2_2") (pintype "passive"))
    )
    (net (code "233") (name "Net-(Q62-PadD)") (class "Default")
      (node (ref "Q62") (pin "D") (pinfunction "D_D") (pintype "passive"))
      (node (ref "R75") (pin "2") (pinfunction "2_2") (pintype "passive"))
    )
    (net (code "234") (name "Net-(Q63-PadD)") (class "Default")
      (node (ref "Q63") (pin "D") (pinfunction "D_D") (pintype "passive"))
      (node (ref "R101") (pin "2") (pinfunction "2_2") (pintype "passive"))
      (node (ref "R104") (pin "2") (pinfunction "2_2") (pintype "passive"))
      (node (ref "R73") (pin "2") (pinfunction "2_2") (pintype "passive"))
      (node (ref "R74") (pin "2") (pinfunction "2_2") (pintype "passive"))
    )
    (net (code "235") (name "Net-(Q66-PadD)") (class "Default")
      (node (ref "Q66") (pin "D") (pinfunction "D_D") (pintype "passive"))
      (node (ref "R98") (pin "2") (pinfunction "2_2") (pintype "passive"))
      (node (ref "R99") (pin "2") (pinfunction "2_2") (pintype "passive"))
    )
    (net (code "236") (name "Net-(Q67-PadD)") (class "Default")
      (node (ref "Q67") (pin "D") (pinfunction "D_D") (pintype "passive"))
      (node (ref "R81") (pin "2") (pinfunction "2_2") (pintype "passive"))
    )
    (net (code "237") (name "Net-(Q68-PadD)") (class "Default")
      (node (ref "Q68") (pin "D") (pinfunction "D_D") (pintype "passive"))
      (node (ref "R100") (pin "2") (pinfunction "2_2") (pintype "passive"))
      (node (ref "R79") (pin "2") (pinfunction "2_2") (pintype "passive"))
      (node (ref "R80") (pin "2") (pinfunction "2_2") (pintype "passive"))
      (node (ref "R97") (pin "2") (pinfunction "2_2") (pintype "passive"))
    )
    (net (code "238") (name "Net-(Q71-PadD)") (class "Default")
      (node (ref "Q71") (pin "D") (pinfunction "D_D") (pintype "passive"))
      (node (ref "R106") (pin "2") (pinfunction "2_2") (pintype "passive"))
      (node (ref "R107") (pin "2") (pinfunction "2_2") (pintype "passive"))
    )
    (net (code "239") (name "Net-(Q72-PadD)") (class "Default")
      (node (ref "Q72") (pin "D") (pinfunction "D_D") (pintype "passive"))
      (node (ref "R87") (pin "2") (pinfunction "2_2") (pintype "passive"))
    )
    (net (code "240") (name "Net-(Q73-PadD)") (class "Default")
      (node (ref "Q73") (pin "D") (pinfunction "D_D") (pintype "passive"))
      (node (ref "R105") (pin "2") (pinfunction "2_2") (pintype "passive"))
      (node (ref "R108") (pin "2") (pinfunction "2_2") (pintype "passive"))
      (node (ref "R85") (pin "2") (pinfunction "2_2") (pintype "passive"))
      (node (ref "R86") (pin "2") (pinfunction "2_2") (pintype "passive"))
    )
    (net (code "241") (name "Net-(Q76-PadD)") (class "Default")
      (node (ref "Q76") (pin "D") (pinfunction "D_D") (pintype "passive"))
      (node (ref "R110") (pin "2") (pinfunction "2_2") (pintype "passive"))
      (node (ref "R111") (pin "2") (pinfunction "2_2") (pintype "passive"))
    )
    (net (code "242") (name "Net-(Q77-PadD)") (class "Default")
      (node (ref "Q77") (pin "D") (pinfunction "D_D") (pintype "passive"))
      (node (ref "R93") (pin "2") (pinfunction "2_2") (pintype "passive"))
    )
    (net (code "243") (name "Net-(Q78-PadD)") (class "Default")
      (node (ref "Q78") (pin "D") (pinfunction "D_D") (pintype "passive"))
      (node (ref "R109") (pin "2") (pinfunction "2_2") (pintype "passive"))
      (node (ref "R112") (pin "2") (pinfunction "2_2") (pintype "passive"))
      (node (ref "R91") (pin "2") (pinfunction "2_2") (pintype "passive"))
      (node (ref "R92") (pin "2") (pinfunction "2_2") (pintype "passive"))
    )
    (net (code "244") (name "ONE_EN_0") (class "Default")
      (node (ref "J1") (pin "2") (pinfunction "2_2") (pintype "passive"))
      (node (ref "Q1") (pin "G") (pinfunction "G_G") (pintype "passive"))
    )
    (net (code "245") (name "ONE_EN_1") (class "Default")
      (node (ref "J4") (pin "2") (pinfunction "2_2") (pintype "passive"))
      (node (ref "Q6") (pin "G") (pinfunction "G_G") (pintype "passive"))
    )
    (net (code "246") (name "ONE_EN_2") (class "Default")
      (node (ref "J7") (pin "2") (pinfunction "2_2") (pintype "passive"))
      (node (ref "Q11") (pin "G") (pinfunction "G_G") (pintype "passive"))
    )
    (net (code "247") (name "ONE_EN_3") (class "Default")
      (node (ref "J10") (pin "2") (pinfunction "2_2") (pintype "passive"))
      (node (ref "Q16") (pin "G") (pinfunction "G_G") (pintype "passive"))
    )
    (net (code "248") (name "ONE_EN_4") (class "Default")
      (node (ref "J13") (pin "2") (pinfunction "2_2") (pintype "passive"))
      (node (ref "Q21") (pin "G") (pinfunction "G_G") (pintype "passive"))
    )
    (net (code "249") (name "ONE_EN_5") (class "Default")
      (node (ref "J16") (pin "2") (pinfunction "2_2") (pintype "passive"))
      (node (ref "Q26") (pin "G") (pinfunction "G_G") (pintype "passive"))
    )
    (net (code "250") (name "ONE_EN_6") (class "Default")
      (node (ref "J19") (pin "2") (pinfunction "2_2") (pintype "passive"))
      (node (ref "Q31") (pin "G") (pinfunction "G_G") (pintype "passive"))
    )
    (net (code "251") (name "ONE_EN_7") (class "Default")
      (node (ref "J22") (pin "2") (pinfunction "2_2") (pintype "passive"))
      (node (ref "Q36") (pin "G") (pinfunction "G_G") (pintype "passive"))
    )
    (net (code "252") (name "ONE_EN_8") (class "Default")
      (node (ref "J25") (pin "2") (pinfunction "2_2") (pintype "passive"))
      (node (ref "Q41") (pin "G") (pinfunction "G_G") (pintype "passive"))
    )
    (net (code "253") (name "ONE_EN_9") (class "Default")
      (node (ref "J28") (pin "2") (pinfunction "2_2") (pintype "passive"))
      (node (ref "Q46") (pin "G") (pinfunction "G_G") (pintype "passive"))
    )
    (net (code "254") (name "ONE_EN_10") (class "Default")
      (node (ref "J31") (pin "2") (pinfunction "2_2") (pintype "passive"))
      (node (ref "Q51") (pin "G") (pinfunction "G_G") (pintype "passive"))
    )
    (net (code "255") (name "ONE_EN_11") (class "Default")
      (node (ref "J34") (pin "2") (pinfunction "2_2") (pintype "passive"))
      (node (ref "Q56") (pin "G") (pinfunction "G_G") (pintype "passive"))
    )
    (net (code "256") (name "ONE_EN_12") (class "Default")
      (node (ref "J37") (pin "2") (pinfunction "2_2") (pintype "passive"))
      (node (ref "Q61") (pin "G") (pinfunction "G_G") (pintype "passive"))
    )
    (net (code "257") (name "ONE_EN_13") (class "Default")
      (node (ref "J40") (pin "2") (pinfunction "2_2") (pintype "passive"))
      (node (ref "Q66") (pin "G") (pinfunction "G_G") (pintype "passive"))
    )
    (net (code "258") (name "ONE_EN_14") (class "Default")
      (node (ref "J43") (pin "2") (pinfunction "2_2") (pintype "passive"))
      (node (ref "Q71") (pin "G") (pinfunction "G_G") (pintype "passive"))
    )
    (net (code "259") (name "ONE_EN_15") (class "Default")
      (node (ref "J46") (pin "2") (pinfunction "2_2") (pintype "passive"))
      (node (ref "Q76") (pin "G") (pinfunction "G_G") (pintype "passive"))
    )
    (net (code "260") (name "ZERO_EN_0") (class "Default")
      (node (ref "J3") (pin "2") (pinfunction "2_2") (pintype "passive"))
      (node (ref "Q3") (pin "G") (pinfunction "G_G") (pintype "passive"))
    )
    (net (code "261") (name "ZERO_EN_1") (class "Default")
      (node (ref "J6") (pin "2") (pinfunction "2_2") (pintype "passive"))
      (node (ref "Q8") (pin "G") (pinfunction "G_G") (pintype "passive"))
    )
    (net (code "262") (name "ZERO_EN_2") (class "Default")
      (node (ref "J9") (pin "2") (pinfunction "2_2") (pintype "passive"))
      (node (ref "Q13") (pin "G") (pinfunction "G_G") (pintype "passive"))
    )
    (net (code "263") (name "ZERO_EN_3") (class "Default")
      (node (ref "J12") (pin "2") (pinfunction "2_2") (pintype "passive"))
      (node (ref "Q18") (pin "G") (pinfunction "G_G") (pintype "passive"))
    )
    (net (code "264") (name "ZERO_EN_4") (class "Default")
      (node (ref "J15") (pin "2") (pinfunction "2_2") (pintype "passive"))
      (node (ref "Q23") (pin "G") (pinfunction "G_G") (pintype "passive"))
    )
    (net (code "265") (name "ZERO_EN_5") (class "Default")
      (node (ref "J18") (pin "2") (pinfunction "2_2") (pintype "passive"))
      (node (ref "Q28") (pin "G") (pinfunction "G_G") (pintype "passive"))
    )
    (net (code "266") (name "ZERO_EN_6") (class "Default")
      (node (ref "J21") (pin "2") (pinfunction "2_2") (pintype "passive"))
      (node (ref "Q33") (pin "G") (pinfunction "G_G") (pintype "passive"))
    )
    (net (code "267") (name "ZERO_EN_7") (class "Default")
      (node (ref "J24") (pin "2") (pinfunction "2_2") (pintype "passive"))
      (node (ref "Q38") (pin "G") (pinfunction "G_G") (pintype "passive"))
    )
    (net (code "268") (name "ZERO_EN_8") (class "Default")
      (node (ref "J27") (pin "2") (pinfunction "2_2") (pintype "passive"))
      (node (ref "Q43") (pin "G") (pinfunction "G_G") (pintype "passive"))
    )
    (net (code "269") (name "ZERO_EN_9") (class "Default")
      (node (ref "J30") (pin "2") (pinfunction "2_2") (pintype "passive"))
      (node (ref "Q48") (pin "G") (pinfunction "G_G") (pintype "passive"))
    )
    (net (code "270") (name "ZERO_EN_10") (class "Default")
      (node (ref "J33") (pin "2") (pinfunction "2_2") (pintype "passive"))
      (node (ref "Q53") (pin "G") (pinfunction "G_G") (pintype "passive"))
    )
    (net (code "271") (name "ZERO_EN_11") (class "Default")
      (node (ref "J36") (pin "2") (pinfunction "2_2") (pintype "passive"))
      (node (ref "Q58") (pin "G") (pinfunction "G_G") (pintype "passive"))
    )
    (net (code "272") (name "ZERO_EN_12") (class "Default")
      (node (ref "J39") (pin "2") (pinfunction "2_2") (pintype "passive"))
      (node (ref "Q63") (pin "G") (pinfunction "G_G") (pintype "passive"))
    )
    (net (code "273") (name "ZERO_EN_13") (class "Default")
      (node (ref "J42") (pin "2") (pinfunction "2_2") (pintype "passive"))
      (node (ref "Q68") (pin "G") (pinfunction "G_G") (pintype "passive"))
    )
    (net (code "274") (name "ZERO_EN_14") (class "Default")
      (node (ref "J45") (pin "2") (pinfunction "2_2") (pintype "passive"))
      (node (ref "Q73") (pin "G") (pinfunction "G_G") (pintype "passive"))
    )
    (net (code "275") (name "ZERO_EN_15") (class "Default")
      (node (ref "J48") (pin "2") (pinfunction "2_2") (pintype "passive"))
      (node (ref "Q78") (pin "G") (pinfunction "G_G") (pintype "passive"))
    )
    (net (code "276") (name "unconnected-(D1-DP-Pad5)") (class "Default")
      (node (ref "D1") (pin "5") (pinfunction "DP_5") (pintype "passive"))
    )
    (net (code "277") (name "unconnected-(D2-DP-Pad5)") (class "Default")
      (node (ref "D2") (pin "5") (pinfunction "DP_5") (pintype "passive"))
    )
    (net (code "278") (name "unconnected-(D3-DP-Pad5)") (class "Default")
      (node (ref "D3") (pin "5") (pinfunction "DP_5") (pintype "passive"))
    )
    (net (code "279") (name "unconnected-(D4-DP-Pad5)") (class "Default")
      (node (ref "D4") (pin "5") (pinfunction "DP_5") (pintype "passive"))
    )
    (net (code "280") (name "unconnected-(D5-DP-Pad5)") (class "Default")
      (node (ref "D5") (pin "5") (pinfunction "DP_5") (pintype "passive"))
    )
    (net (code "281") (name "unconnected-(D6-DP-Pad5)") (class "Default")
      (node (ref "D6") (pin "5") (pinfunction "DP_5") (pintype "passive"))
    )
    (net (code "282") (name "unconnected-(D7-DP-Pad5)") (class "Default")
      (node (ref "D7") (pin "5") (pinfunction "DP_5") (pintype "passive"))
    )
    (net (code "283") (name "unconnected-(D8-DP-Pad5)") (class "Default")
      (node (ref "D8") (pin "5") (pinfunction "DP_5") (pintype "passive"))
    )
    (net (code "284") (name "unconnected-(D9-DP-Pad5)") (class "Default")
      (node (ref "D9") (pin "5") (pinfunction "DP_5") (pintype "passive"))
    )
    (net (code "285") (name "unconnected-(D10-DP-Pad5)") (class "Default")
      (node (ref "D10") (pin "5") (pinfunction "DP_5") (pintype "passive"))
    )
    (net (code "286") (name "unconnected-(D11-DP-Pad5)") (class "Default")
      (node (ref "D11") (pin "5") (pinfunction "DP_5") (pintype "passive"))
    )
    (net (code "287") (name "unconnected-(D12-DP-Pad5)") (class "Default")
      (node (ref "D12") (pin "5") (pinfunction "DP_5") (pintype "passive"))
    )
    (net (code "288") (name "unconnected-(D13-DP-Pad5)") (class "Default")
      (node (ref "D13") (pin "5") (pinfunction "DP_5") (pintype "passive"))
    )
    (net (code "289") (name "unconnected-(D14-DP-Pad5)") (class "Default")
      (node (ref "D14") (pin "5") (pinfunction "DP_5") (pintype "passive"))
    )
    (net (code "290") (name "unconnected-(D15-DP-Pad5)") (class "Default")
      (node (ref "D15") (pin "5") (pinfunction "DP_5") (pintype "passive"))
    )
    (net (code "291") (name "unconnected-(D16-DP-Pad5)") (class "Default")
      (node (ref "D16") (pin "5") (pinfunction "DP_5") (pintype "passive"))
    )
    (net (code "292") (name "unconnected-(J49-Pad22)") (class "Default")
      (node (ref "J49") (pin "22") (pinfunction "22_22") (pintype "bidirectional"))
    )
    (net (code "293") (name "unconnected-(J49-Pad23)") (class "Default")
      (node (ref "J49") (pin "23") (pinfunction "23_23") (pintype "bidirectional"))
    )
    (net (code "294") (name "unconnected-(J49-Pad24)") (class "Default")
      (node (ref "J49") (pin "24") (pinfunction "24_24") (pintype "bidirectional"))
    )
    (net (code "295") (name "unconnected-(J49-Pad25)") (class "Default")
      (node (ref "J49") (pin "25") (pinfunction "25_25") (pintype "bidirectional"))
    )
    (net (code "296") (name "unconnected-(J49-Pad26)") (class "Default")
      (node (ref "J49") (pin "26") (pinfunction "26_26") (pintype "bidirectional"))
    )
    (net (code "297") (name "unconnected-(J49-Pad27)") (class "Default")
      (node (ref "J49") (pin "27") (pinfunction "27_27") (pintype "bidirectional"))
    )
    (net (code "298") (name "unconnected-(J49-Pad28)") (class "Default")
      (node (ref "J49") (pin "28") (pinfunction "28_28") (pintype "bidirectional"))
    )
    (net (code "299") (name "unconnected-(J49-Pad29)") (class "Default")
      (node (ref "J49") (pin "29") (pinfunction "29_29") (pintype "bidirectional"))
    )
  )
)
